# Replicape_B3A.net
KiCad netlist of a schematic drawn in EAGLE
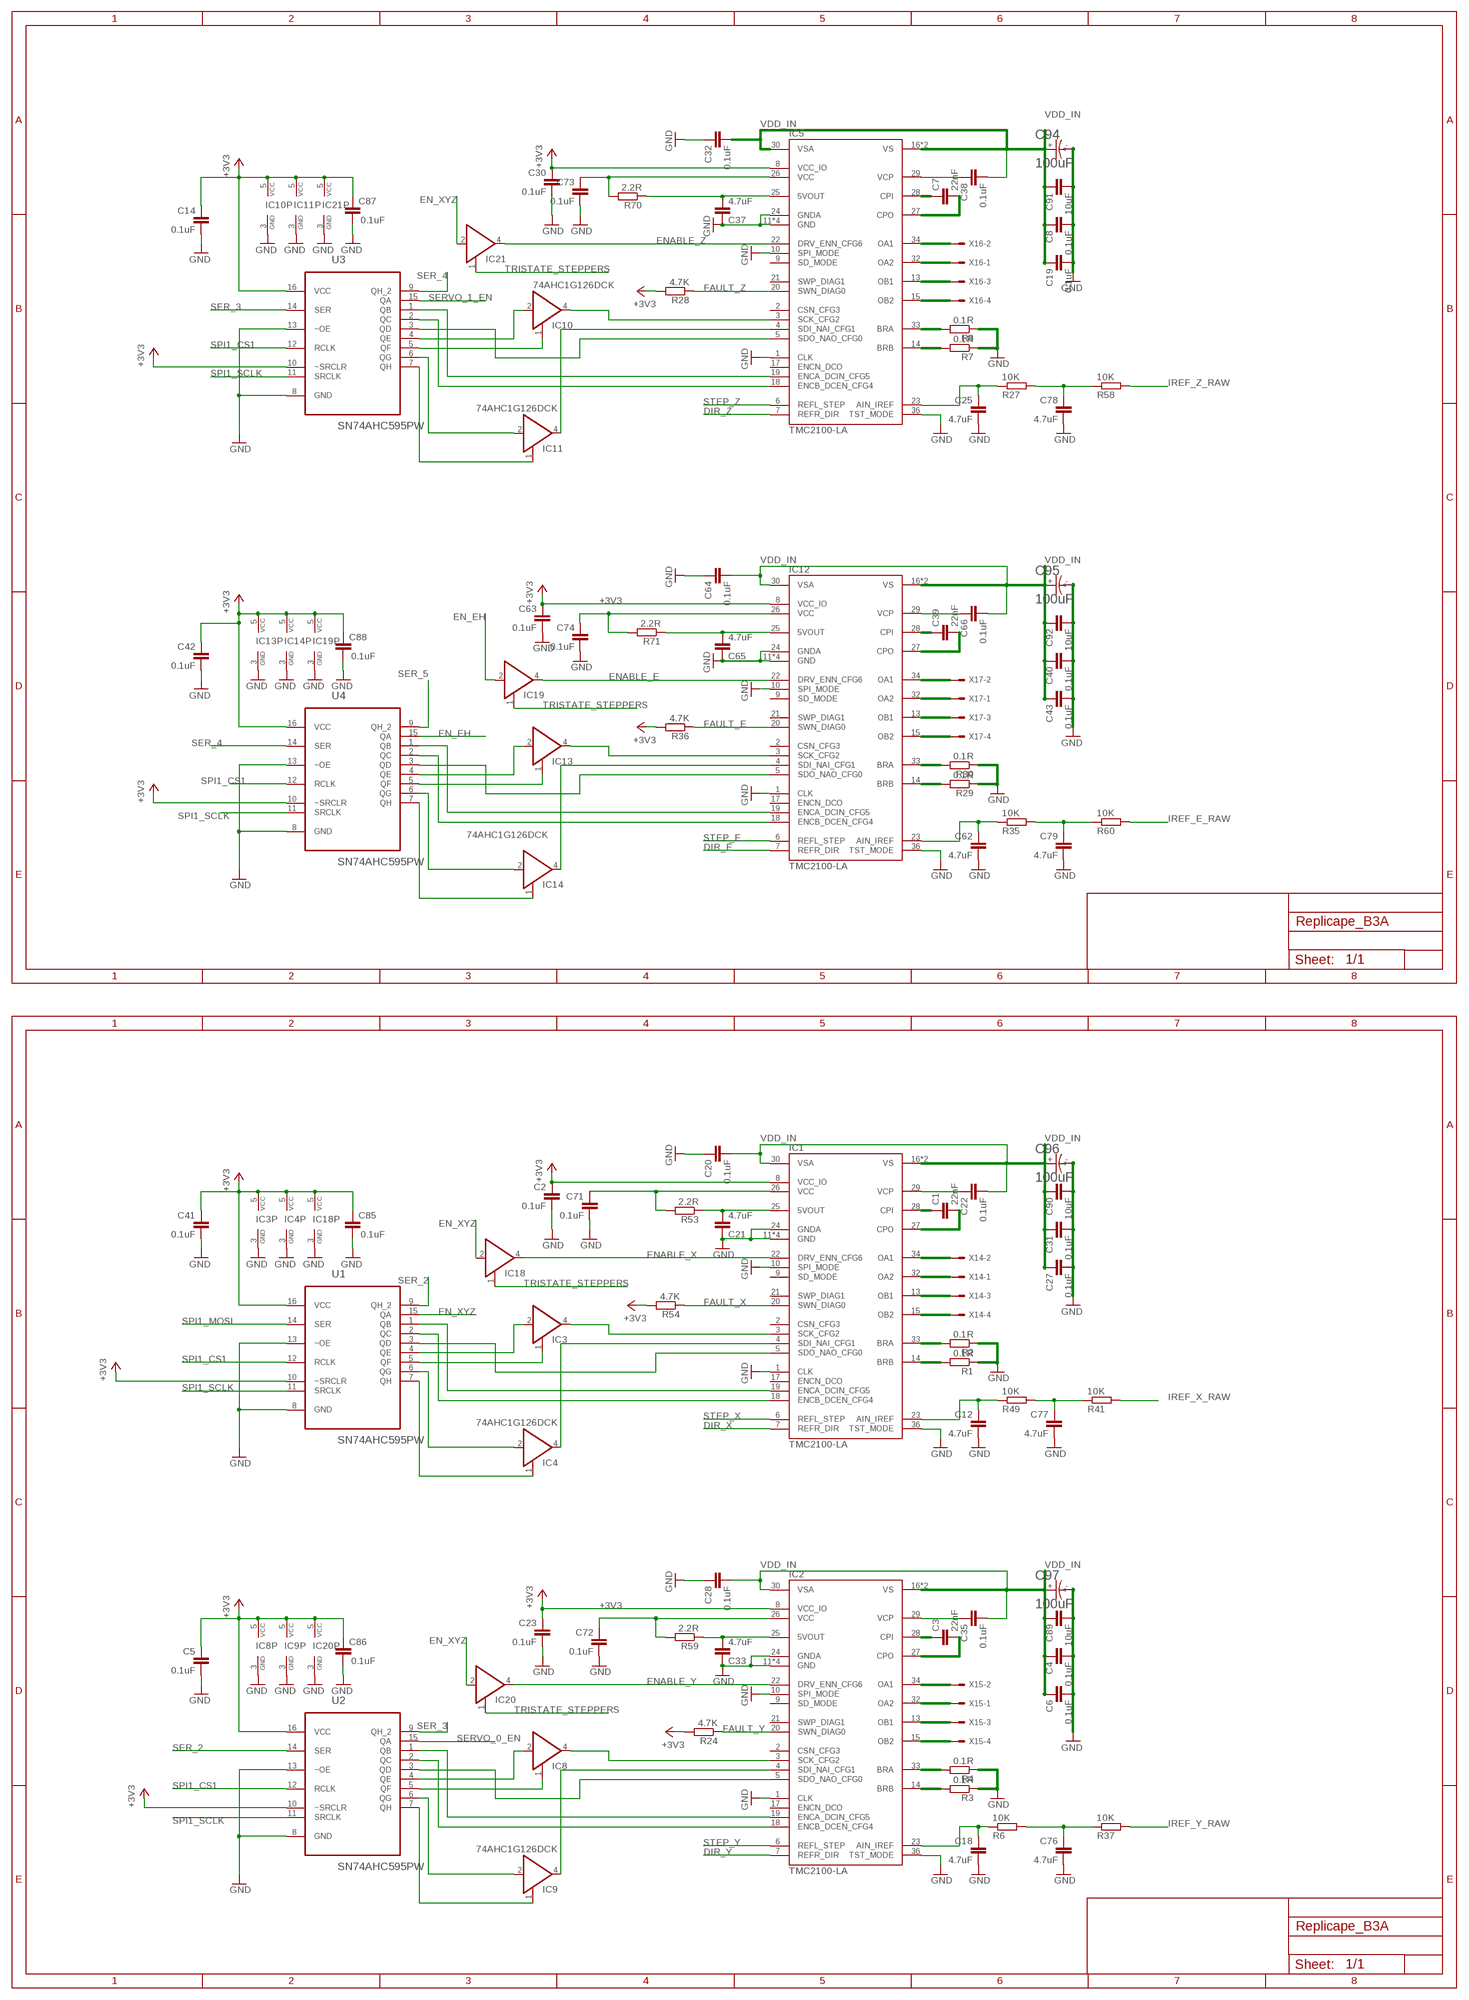
[diagram p0: schematic, sheet 1, part 1 of 3]
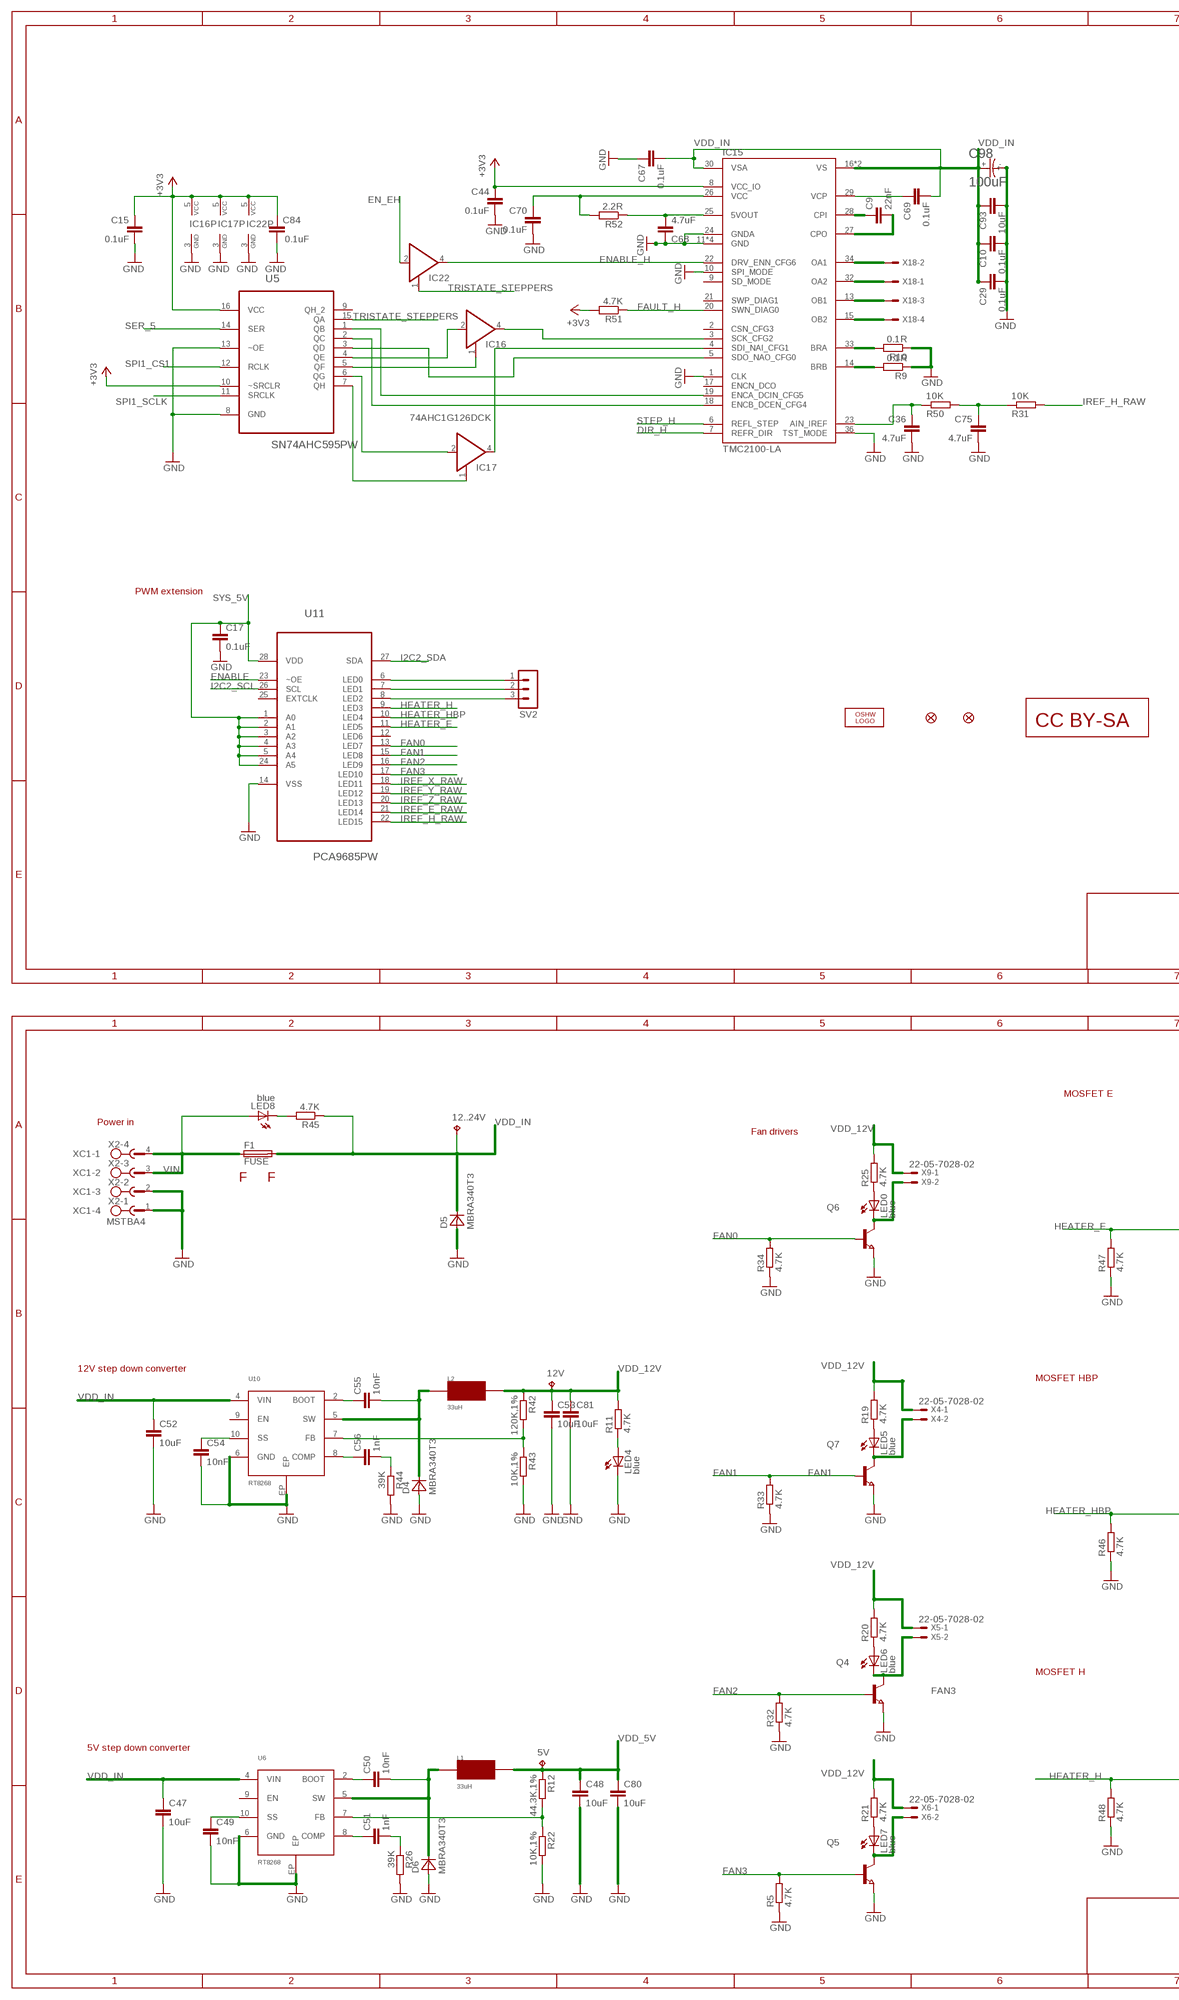
[diagram p1: schematic, sheet 1, part 2 of 3]
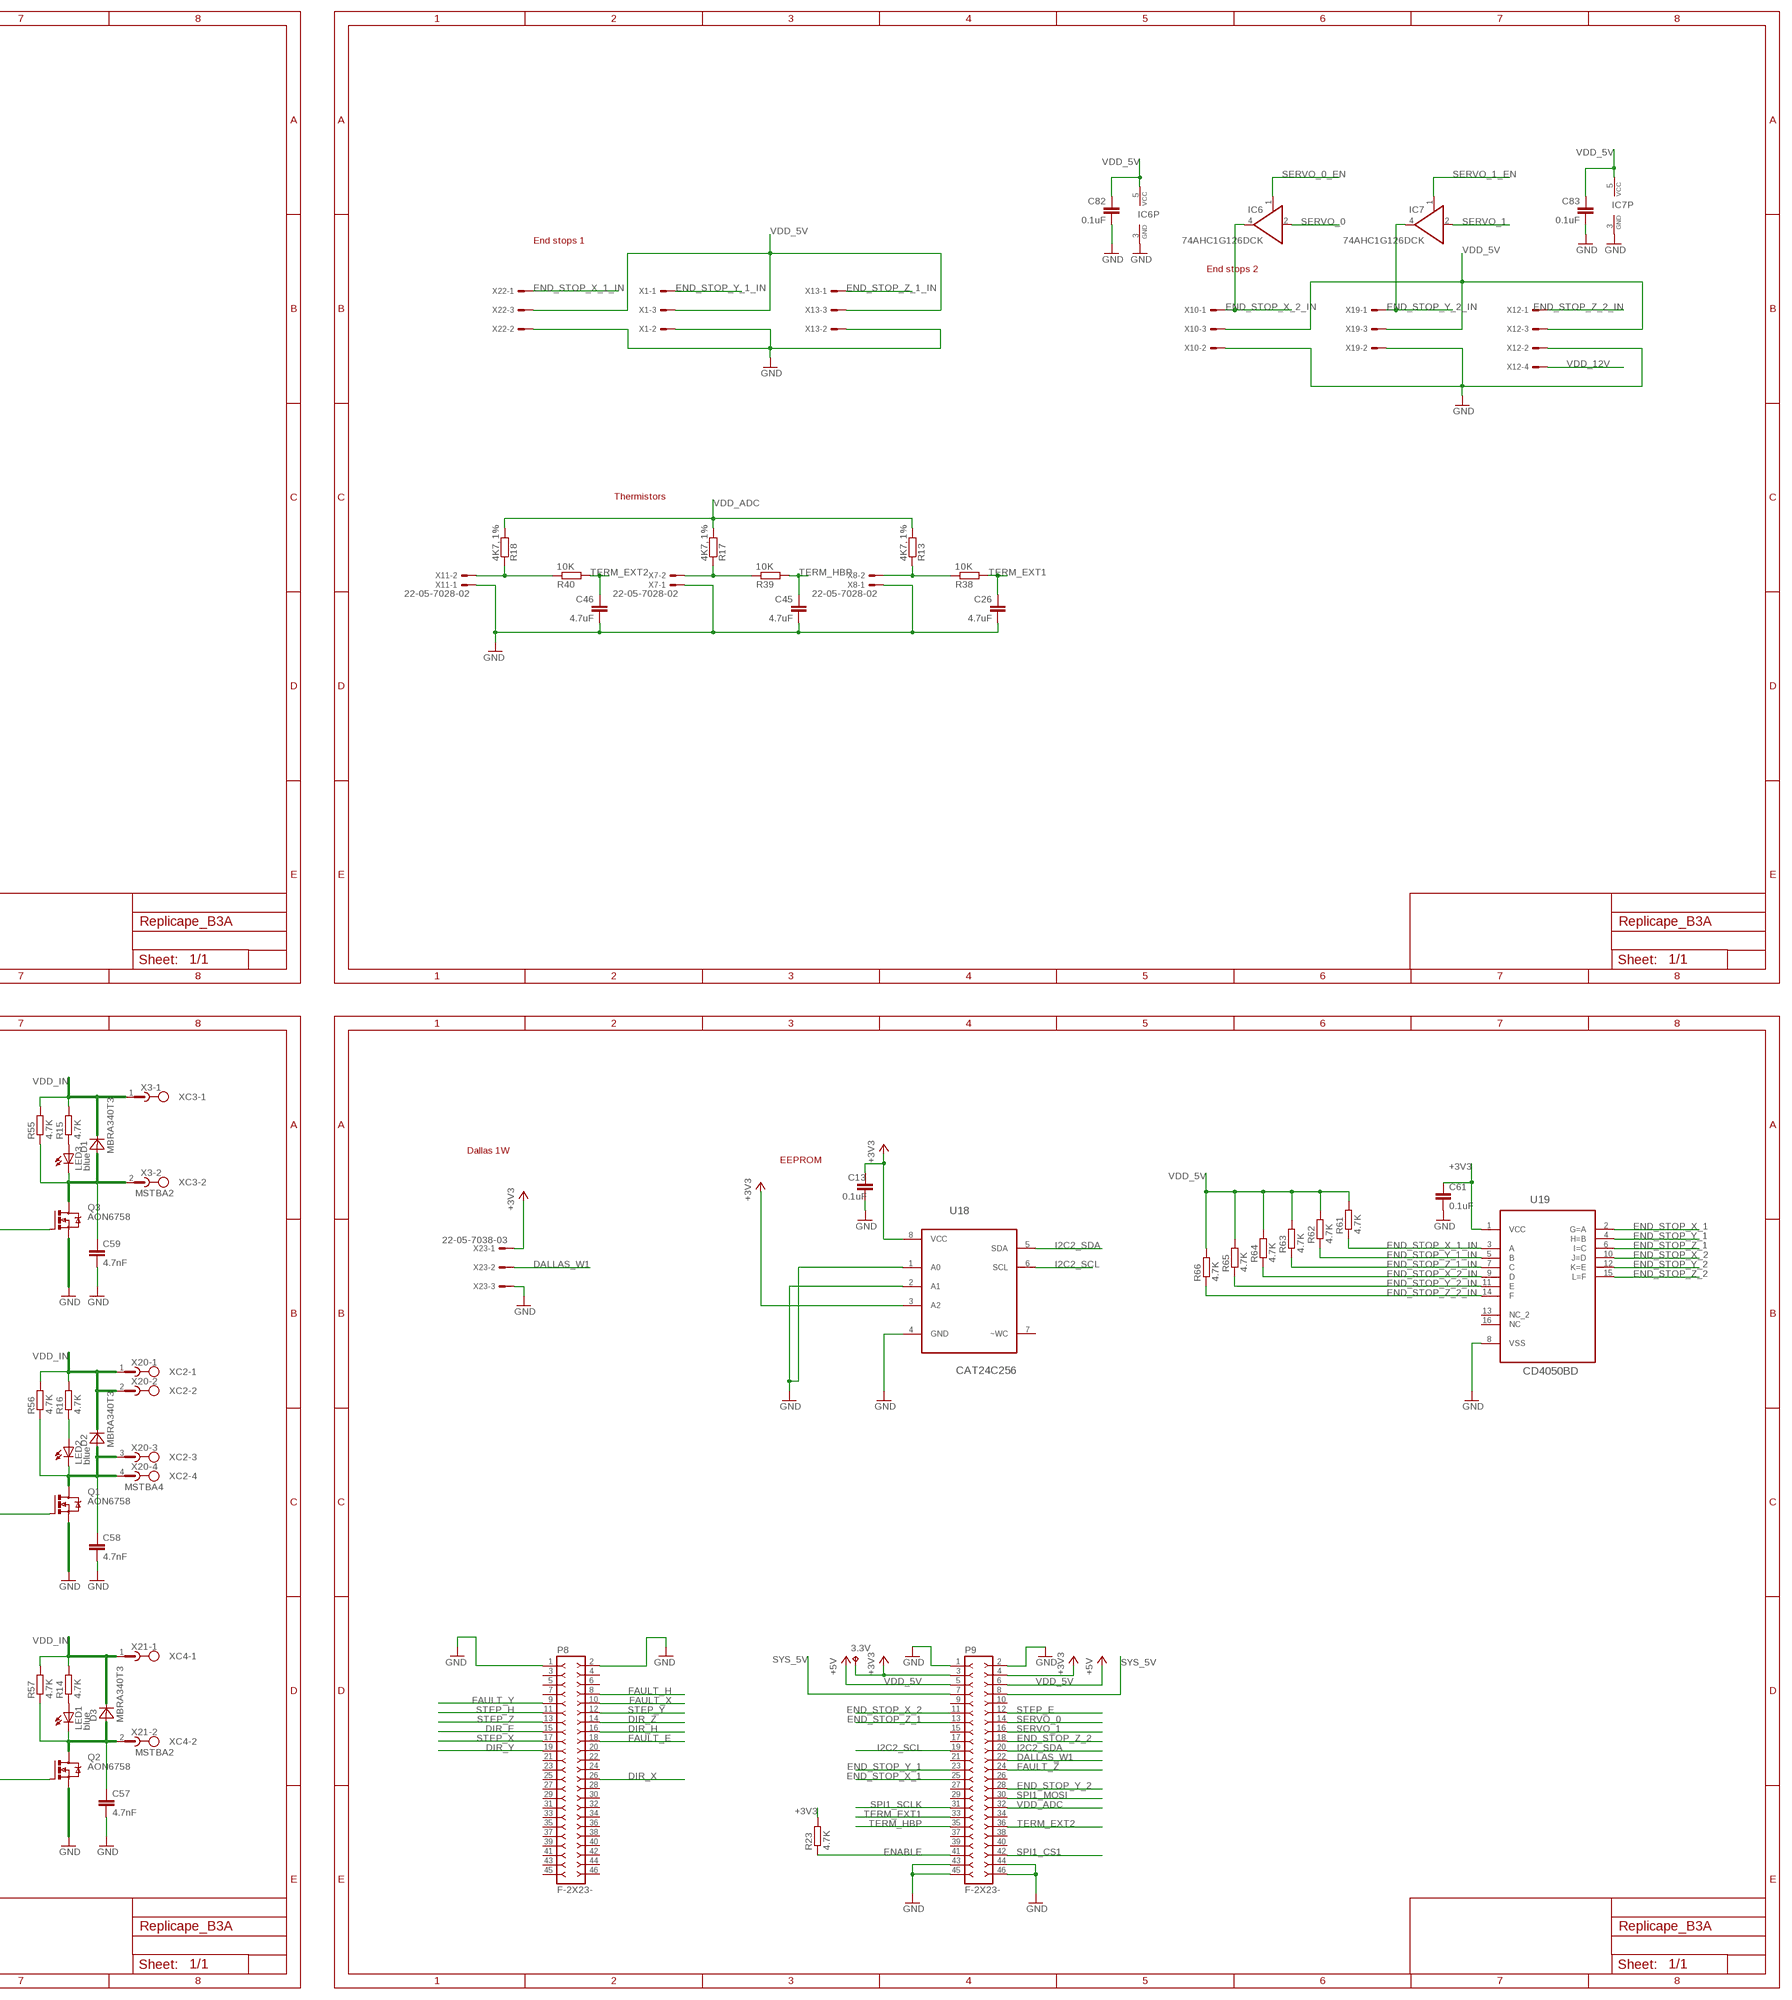
[diagram p2: schematic, sheet 1, part 3 of 3]

(export (version "E")
  (design (tool "Eeschema 10.0.6"))
  (components
    (comp (ref "3.3V")
      (value "TPB1,27")
      (footprint "eagle-import:B1,27")
      (libsource (lib "eagle-import") (part "TPB1,27"))
    )
    (comp (ref "5V")
      (value "TPB1,27")
      (footprint "eagle-import:B1,27")
      (libsource (lib "eagle-import") (part "TPB1,27"))
    )
    (comp (ref "12..24V")
      (value "TPB1,27")
      (footprint "eagle-import:B1,27")
      (libsource (lib "eagle-import") (part "TPB1,27"))
    )
    (comp (ref "12V")
      (value "TPB1,27")
      (footprint "eagle-import:B1,27")
      (libsource (lib "eagle-import") (part "TPB1,27"))
    )
    (comp (ref "C1")
      (value "22nF")
      (footprint "eagle-import:C0402")
      (fields (field (name "MPN") "C1005X7R1E223K050BB"))
      (libsource (lib "eagle-import") (part "C-EUC0402"))
    )
    (comp (ref "C2")
      (value "0.1uF")
      (footprint "eagle-import:C0402")
      (fields (field (name "MPN") "CL10B104KB8NNND"))
      (libsource (lib "eagle-import") (part "C-EUC0402"))
    )
    (comp (ref "C3")
      (value "22nF")
      (footprint "eagle-import:C0402")
      (fields (field (name "MPN") "C1005X7R1E223K050BB"))
      (libsource (lib "eagle-import") (part "C-EUC0402"))
    )
    (comp (ref "C4")
      (value "0.1uF")
      (footprint "eagle-import:C0402")
      (fields (field (name "MPN") "CL10B104KB8NNND"))
      (libsource (lib "eagle-import") (part "C-EUC0402"))
    )
    (comp (ref "C5")
      (value "0.1uF")
      (footprint "eagle-import:C0402")
      (fields (field (name "MPN") "CL10B104KB8NNND"))
      (libsource (lib "eagle-import") (part "C-EUC0402"))
    )
    (comp (ref "C6")
      (value "0.1uF")
      (footprint "eagle-import:C0402")
      (fields (field (name "MPN") "CL10B104KB8NNND"))
      (libsource (lib "eagle-import") (part "C-EUC0402"))
    )
    (comp (ref "C7")
      (value "22nF")
      (footprint "eagle-import:C0402")
      (fields (field (name "MPN") "C1005X7R1E223K050BB"))
      (libsource (lib "eagle-import") (part "C-EUC0402"))
    )
    (comp (ref "C8")
      (value "0.1uF")
      (footprint "eagle-import:C0402")
      (fields (field (name "MPN") "CL10B104KB8NNND"))
      (libsource (lib "eagle-import") (part "C-EUC0402"))
    )
    (comp (ref "C9")
      (value "22nF")
      (footprint "eagle-import:C0402")
      (fields (field (name "MPN") "C1005X7R1E223K050BB"))
      (libsource (lib "eagle-import") (part "C-EUC0402"))
    )
    (comp (ref "C10")
      (value "0.1uF")
      (footprint "eagle-import:C0402")
      (fields (field (name "MPN") "CL10B104KB8NNND"))
      (libsource (lib "eagle-import") (part "C-EUC0402"))
    )
    (comp (ref "C12")
      (value "4.7uF")
      (footprint "eagle-import:C0402")
      (fields (field (name "MPN") "GRM155R60J475ME47D"))
      (libsource (lib "eagle-import") (part "C-EUC0402"))
    )
    (comp (ref "C13")
      (value "0.1uF")
      (footprint "eagle-import:C0402")
      (fields (field (name "MPN") "CL10B104KB8NNND"))
      (libsource (lib "eagle-import") (part "C-EUC0402"))
    )
    (comp (ref "C14")
      (value "0.1uF")
      (footprint "eagle-import:C0402")
      (fields (field (name "MPN") "CL10B104KB8NNND"))
      (libsource (lib "eagle-import") (part "C-EUC0402"))
    )
    (comp (ref "C15")
      (value "0.1uF")
      (footprint "eagle-import:C0402")
      (fields (field (name "MPN") "CL10B104KB8NNND"))
      (libsource (lib "eagle-import") (part "C-EUC0402"))
    )
    (comp (ref "C17")
      (value "0.1uF")
      (footprint "eagle-import:C0402")
      (fields (field (name "MPN") "CL10B104KB8NNND"))
      (libsource (lib "eagle-import") (part "C-EUC0402"))
    )
    (comp (ref "C18")
      (value "4.7uF")
      (footprint "eagle-import:C0402")
      (fields (field (name "MPN") "GRM155R60J475ME47D"))
      (libsource (lib "eagle-import") (part "C-EUC0402"))
    )
    (comp (ref "C19")
      (value "0.1uF")
      (footprint "eagle-import:C0402")
      (fields (field (name "MPN") "CL10B104KB8NNND"))
      (libsource (lib "eagle-import") (part "C-EUC0402"))
    )
    (comp (ref "C20")
      (value "0.1uF")
      (footprint "eagle-import:C0402")
      (fields (field (name "MPN") "CL10B104KB8NNND"))
      (libsource (lib "eagle-import") (part "C-EUC0402"))
    )
    (comp (ref "C21")
      (value "4.7uF")
      (footprint "eagle-import:C0402")
      (fields (field (name "MPN") "GRM155R60J475ME47D"))
      (libsource (lib "eagle-import") (part "C-EUC0402"))
    )
    (comp (ref "C22")
      (value "0.1uF")
      (footprint "eagle-import:C0402")
      (fields (field (name "MPN") "CL10B104KB8NNND"))
      (libsource (lib "eagle-import") (part "C-EUC0402"))
    )
    (comp (ref "C23")
      (value "0.1uF")
      (footprint "eagle-import:C0402")
      (fields (field (name "MPN") "CL10B104KB8NNND"))
      (libsource (lib "eagle-import") (part "C-EUC0402"))
    )
    (comp (ref "C25")
      (value "4.7uF")
      (footprint "eagle-import:C0402")
      (fields (field (name "MPN") "GRM155R60J475ME47D"))
      (libsource (lib "eagle-import") (part "C-EUC0402"))
    )
    (comp (ref "C26")
      (value "4.7uF")
      (footprint "eagle-import:C0402")
      (fields (field (name "MPN") "GRM155R60J475ME47D"))
      (libsource (lib "eagle-import") (part "C-EUC0402"))
    )
    (comp (ref "C27")
      (value "0.1uF")
      (footprint "eagle-import:C0402")
      (fields (field (name "MPN") "CL10B104KB8NNND"))
      (libsource (lib "eagle-import") (part "C-EUC0402"))
    )
    (comp (ref "C28")
      (value "0.1uF")
      (footprint "eagle-import:C0402")
      (fields (field (name "MPN") "CL10B104KB8NNND"))
      (libsource (lib "eagle-import") (part "C-EUC0402"))
    )
    (comp (ref "C29")
      (value "0.1uF")
      (footprint "eagle-import:C0402")
      (fields (field (name "MPN") "CL10B104KB8NNND"))
      (libsource (lib "eagle-import") (part "C-EUC0402"))
    )
    (comp (ref "C30")
      (value "0.1uF")
      (footprint "eagle-import:C0402")
      (fields (field (name "MPN") "CL10B104KB8NNND"))
      (libsource (lib "eagle-import") (part "C-EUC0402"))
    )
    (comp (ref "C31")
      (value "0.1uF")
      (footprint "eagle-import:C0402")
      (fields (field (name "MPN") "CL10B104KB8NNND"))
      (libsource (lib "eagle-import") (part "C-EUC0402"))
    )
    (comp (ref "C32")
      (value "0.1uF")
      (footprint "eagle-import:C0402")
      (fields (field (name "MPN") "CL10B104KB8NNND"))
      (libsource (lib "eagle-import") (part "C-EUC0402"))
    )
    (comp (ref "C33")
      (value "4.7uF")
      (footprint "eagle-import:C0402")
      (fields (field (name "MPN") "GRM155R60J475ME47D"))
      (libsource (lib "eagle-import") (part "C-EUC0402"))
    )
    (comp (ref "C35")
      (value "0.1uF")
      (footprint "eagle-import:C0402")
      (fields (field (name "MPN") "CL10B104KB8NNND"))
      (libsource (lib "eagle-import") (part "C-EUC0402"))
    )
    (comp (ref "C36")
      (value "4.7uF")
      (footprint "eagle-import:C0402")
      (fields (field (name "MPN") "GRM155R60J475ME47D"))
      (libsource (lib "eagle-import") (part "C-EUC0402"))
    )
    (comp (ref "C37")
      (value "4.7uF")
      (footprint "eagle-import:C0402")
      (fields (field (name "MPN") "GRM155R60J475ME47D"))
      (libsource (lib "eagle-import") (part "C-EUC0402"))
    )
    (comp (ref "C38")
      (value "0.1uF")
      (footprint "eagle-import:C0402")
      (fields (field (name "MPN") "CL10B104KB8NNND"))
      (libsource (lib "eagle-import") (part "C-EUC0402"))
    )
    (comp (ref "C39")
      (value "22nF")
      (footprint "eagle-import:C0402")
      (fields (field (name "MPN") "C1005X7R1E223K050BB"))
      (libsource (lib "eagle-import") (part "C-EUC0402"))
    )
    (comp (ref "C40")
      (value "0.1uF")
      (footprint "eagle-import:C0402")
      (fields (field (name "MPN") "CL10B104KB8NNND"))
      (libsource (lib "eagle-import") (part "C-EUC0402"))
    )
    (comp (ref "C41")
      (value "0.1uF")
      (footprint "eagle-import:C0402")
      (fields (field (name "MPN") "CL10B104KB8NNND"))
      (libsource (lib "eagle-import") (part "C-EUC0402"))
    )
    (comp (ref "C42")
      (value "0.1uF")
      (footprint "eagle-import:C0402")
      (fields (field (name "MPN") "CL10B104KB8NNND"))
      (libsource (lib "eagle-import") (part "C-EUC0402"))
    )
    (comp (ref "C43")
      (value "0.1uF")
      (footprint "eagle-import:C0402")
      (fields (field (name "MPN") "CL10B104KB8NNND"))
      (libsource (lib "eagle-import") (part "C-EUC0402"))
    )
    (comp (ref "C44")
      (value "0.1uF")
      (footprint "eagle-import:C0402")
      (fields (field (name "MPN") "CL10B104KB8NNND"))
      (libsource (lib "eagle-import") (part "C-EUC0402"))
    )
    (comp (ref "C45")
      (value "4.7uF")
      (footprint "eagle-import:C0402")
      (fields (field (name "MPN") "GRM155R60J475ME47D"))
      (libsource (lib "eagle-import") (part "C-EUC0402"))
    )
    (comp (ref "C46")
      (value "4.7uF")
      (footprint "eagle-import:C0402")
      (fields (field (name "MPN") "GRM155R60J475ME47D"))
      (libsource (lib "eagle-import") (part "C-EUC0402"))
    )
    (comp (ref "C47")
      (value "10uF")
      (footprint "eagle-import:C1206")
      (fields (field (name "MPN") "CL31B106KAHNNNE"))
      (libsource (lib "eagle-import") (part "C-EUC1206"))
    )
    (comp (ref "C48")
      (value "10uF")
      (footprint "eagle-import:C1206")
      (fields (field (name "MPN") "CL31B106KAHNNNE"))
      (libsource (lib "eagle-import") (part "C-EUC1206"))
    )
    (comp (ref "C49")
      (value "10nF")
      (footprint "eagle-import:C0402")
      (fields (field (name "MPN") "CL05B103KB5NNNC"))
      (libsource (lib "eagle-import") (part "C-EUC0402"))
    )
    (comp (ref "C50")
      (value "10nF")
      (footprint "eagle-import:C0402")
      (fields (field (name "MPN") "CL05B103KB5NNNC"))
      (libsource (lib "eagle-import") (part "C-EUC0402"))
    )
    (comp (ref "C51")
      (value "1nF")
      (footprint "eagle-import:C0402")
      (fields (field (name "MPN") "C1005X7R1H102K050BA"))
      (libsource (lib "eagle-import") (part "C-EUC0402"))
    )
    (comp (ref "C52")
      (value "10uF")
      (footprint "eagle-import:C1206")
      (fields (field (name "MPN") "CL31B106KAHNNNE"))
      (libsource (lib "eagle-import") (part "C-EUC1206"))
    )
    (comp (ref "C53")
      (value "10uF")
      (footprint "eagle-import:C1206")
      (fields (field (name "MPN") "CL31B106KAHNNNE"))
      (libsource (lib "eagle-import") (part "C-EUC1206"))
    )
    (comp (ref "C54")
      (value "10nF")
      (footprint "eagle-import:C0402")
      (fields (field (name "MPN") "CL05B103KB5NNNC"))
      (libsource (lib "eagle-import") (part "C-EUC0402"))
    )
    (comp (ref "C55")
      (value "10nF")
      (footprint "eagle-import:C0402")
      (fields (field (name "MPN") "CL05B103KB5NNNC"))
      (libsource (lib "eagle-import") (part "C-EUC0402"))
    )
    (comp (ref "C56")
      (value "1nF")
      (footprint "eagle-import:C0402")
      (fields (field (name "MPN") "C1005X7R1H102K050BA"))
      (libsource (lib "eagle-import") (part "C-EUC0402"))
    )
    (comp (ref "C57")
      (value "4.7nF")
      (footprint "eagle-import:C0402")
      (fields (field (name "MPN") "CL05B472KA5NNNC"))
      (libsource (lib "eagle-import") (part "C-EUC0402"))
    )
    (comp (ref "C58")
      (value "4.7nF")
      (footprint "eagle-import:C0402")
      (fields (field (name "MPN") "CL05B472KA5NNNC"))
      (libsource (lib "eagle-import") (part "C-EUC0402"))
    )
    (comp (ref "C59")
      (value "4.7nF")
      (footprint "eagle-import:C0402")
      (fields (field (name "MPN") "CL05B472KA5NNNC"))
      (libsource (lib "eagle-import") (part "C-EUC0402"))
    )
    (comp (ref "C61")
      (value "0.1uF")
      (footprint "eagle-import:C0402")
      (fields (field (name "MPN") "CL10B104KB8NNND"))
      (libsource (lib "eagle-import") (part "C-EUC0402"))
    )
    (comp (ref "C62")
      (value "4.7uF")
      (footprint "eagle-import:C0402")
      (fields (field (name "MPN") "GRM155R60J475ME47D"))
      (libsource (lib "eagle-import") (part "C-EUC0402"))
    )
    (comp (ref "C63")
      (value "0.1uF")
      (footprint "eagle-import:C0402")
      (fields (field (name "MPN") "CL10B104KB8NNND"))
      (libsource (lib "eagle-import") (part "C-EUC0402"))
    )
    (comp (ref "C64")
      (value "0.1uF")
      (footprint "eagle-import:C0402")
      (fields (field (name "MPN") "CL10B104KB8NNND"))
      (libsource (lib "eagle-import") (part "C-EUC0402"))
    )
    (comp (ref "C65")
      (value "4.7uF")
      (footprint "eagle-import:C0402")
      (fields (field (name "MPN") "GRM155R60J475ME47D"))
      (libsource (lib "eagle-import") (part "C-EUC0402"))
    )
    (comp (ref "C66")
      (value "0.1uF")
      (footprint "eagle-import:C0402")
      (fields (field (name "MPN") "CL10B104KB8NNND"))
      (libsource (lib "eagle-import") (part "C-EUC0402"))
    )
    (comp (ref "C67")
      (value "0.1uF")
      (footprint "eagle-import:C0402")
      (fields (field (name "MPN") "CL10B104KB8NNND"))
      (libsource (lib "eagle-import") (part "C-EUC0402"))
    )
    (comp (ref "C68")
      (value "4.7uF")
      (footprint "eagle-import:C0402")
      (fields (field (name "MPN") "GRM155R60J475ME47D"))
      (libsource (lib "eagle-import") (part "C-EUC0402"))
    )
    (comp (ref "C69")
      (value "0.1uF")
      (footprint "eagle-import:C0402")
      (fields (field (name "MPN") "CL10B104KB8NNND"))
      (libsource (lib "eagle-import") (part "C-EUC0402"))
    )
    (comp (ref "C70")
      (value "0.1uF")
      (footprint "eagle-import:C0402")
      (fields (field (name "MPN") "CL10B104KB8NNND"))
      (libsource (lib "eagle-import") (part "C-EUC0402"))
    )
    (comp (ref "C71")
      (value "0.1uF")
      (footprint "eagle-import:C0402")
      (fields (field (name "MPN") "CL10B104KB8NNND"))
      (libsource (lib "eagle-import") (part "C-EUC0402"))
    )
    (comp (ref "C72")
      (value "0.1uF")
      (footprint "eagle-import:C0402")
      (fields (field (name "MPN") "CL10B104KB8NNND"))
      (libsource (lib "eagle-import") (part "C-EUC0402"))
    )
    (comp (ref "C73")
      (value "0.1uF")
      (footprint "eagle-import:C0402")
      (fields (field (name "MPN") "CL10B104KB8NNND"))
      (libsource (lib "eagle-import") (part "C-EUC0402"))
    )
    (comp (ref "C74")
      (value "0.1uF")
      (footprint "eagle-import:C0402")
      (fields (field (name "MPN") "CL10B104KB8NNND"))
      (libsource (lib "eagle-import") (part "C-EUC0402"))
    )
    (comp (ref "C75")
      (value "4.7uF")
      (footprint "eagle-import:C0402")
      (fields (field (name "MPN") "GRM155R60J475ME47D"))
      (libsource (lib "eagle-import") (part "C-EUC0402"))
    )
    (comp (ref "C76")
      (value "4.7uF")
      (footprint "eagle-import:C0402")
      (fields (field (name "MPN") "GRM155R60J475ME47D"))
      (libsource (lib "eagle-import") (part "C-EUC0402"))
    )
    (comp (ref "C77")
      (value "4.7uF")
      (footprint "eagle-import:C0402")
      (fields (field (name "MPN") "GRM155R60J475ME47D"))
      (libsource (lib "eagle-import") (part "C-EUC0402"))
    )
    (comp (ref "C78")
      (value "4.7uF")
      (footprint "eagle-import:C0402")
      (fields (field (name "MPN") "GRM155R60J475ME47D"))
      (libsource (lib "eagle-import") (part "C-EUC0402"))
    )
    (comp (ref "C79")
      (value "4.7uF")
      (footprint "eagle-import:C0402")
      (fields (field (name "MPN") "GRM155R60J475ME47D"))
      (libsource (lib "eagle-import") (part "C-EUC0402"))
    )
    (comp (ref "C80")
      (value "10uF")
      (footprint "eagle-import:C1206")
      (fields (field (name "MPN") "CL31B106KAHNNNE"))
      (libsource (lib "eagle-import") (part "C-EUC1206"))
    )
    (comp (ref "C81")
      (value "10uF")
      (footprint "eagle-import:C1206")
      (fields (field (name "MPN") "CL31B106KAHNNNE"))
      (libsource (lib "eagle-import") (part "C-EUC1206"))
    )
    (comp (ref "C82")
      (value "0.1uF")
      (footprint "eagle-import:C0402")
      (fields (field (name "MPN") "CL10B104KB8NNND"))
      (libsource (lib "eagle-import") (part "C-EUC0402"))
    )
    (comp (ref "C83")
      (value "0.1uF")
      (footprint "eagle-import:C0402")
      (fields (field (name "MPN") "CL10B104KB8NNND"))
      (libsource (lib "eagle-import") (part "C-EUC0402"))
    )
    (comp (ref "C84")
      (value "0.1uF")
      (footprint "eagle-import:C0402")
      (fields (field (name "MPN") "CL10B104KB8NNND"))
      (libsource (lib "eagle-import") (part "C-EUC0402"))
    )
    (comp (ref "C85")
      (value "0.1uF")
      (footprint "eagle-import:C0402")
      (fields (field (name "MPN") "CL10B104KB8NNND"))
      (libsource (lib "eagle-import") (part "C-EUC0402"))
    )
    (comp (ref "C86")
      (value "0.1uF")
      (footprint "eagle-import:C0402")
      (fields (field (name "MPN") "CL10B104KB8NNND"))
      (libsource (lib "eagle-import") (part "C-EUC0402"))
    )
    (comp (ref "C87")
      (value "0.1uF")
      (footprint "eagle-import:C0402")
      (fields (field (name "MPN") "CL10B104KB8NNND"))
      (libsource (lib "eagle-import") (part "C-EUC0402"))
    )
    (comp (ref "C88")
      (value "0.1uF")
      (footprint "eagle-import:C0402")
      (fields (field (name "MPN") "CL10B104KB8NNND"))
      (libsource (lib "eagle-import") (part "C-EUC0402"))
    )
    (comp (ref "C89")
      (value "10uF")
      (footprint "eagle-import:C0805")
      (fields (field (name "MPN") "C2012X5R1V106M085AC"))
      (libsource (lib "eagle-import") (part "C-EUC0805"))
    )
    (comp (ref "C90")
      (value "10uF")
      (footprint "eagle-import:C0805")
      (fields (field (name "MPN") "C2012X5R1V106M085AC"))
      (libsource (lib "eagle-import") (part "C-EUC0805"))
    )
    (comp (ref "C91")
      (value "10uF")
      (footprint "eagle-import:C0805")
      (fields (field (name "MPN") "C2012X5R1V106M085AC"))
      (libsource (lib "eagle-import") (part "C-EUC0805"))
    )
    (comp (ref "C92")
      (value "10uF")
      (footprint "eagle-import:C0805")
      (fields (field (name "MPN") "C2012X5R1V106M085AC"))
      (libsource (lib "eagle-import") (part "C-EUC0805"))
    )
    (comp (ref "C93")
      (value "10uF")
      (footprint "eagle-import:C0805")
      (fields (field (name "MPN") "C2012X5R1V106M085AC"))
      (libsource (lib "eagle-import") (part "C-EUC0805"))
    )
    (comp (ref "C94")
      (value "100uF")
      (footprint "eagle-import:RHS1V10MCN1GS")
      (fields (field (name "MPN") "RHS1V101MCN1GS"))
      (libsource (lib "eagle-import") (part "C"))
    )
    (comp (ref "C95")
      (value "100uF")
      (footprint "eagle-import:RHS1V10MCN1GS")
      (fields (field (name "MPN") "RHS1V101MCN1GS"))
      (libsource (lib "eagle-import") (part "C"))
    )
    (comp (ref "C96")
      (value "100uF")
      (footprint "eagle-import:RHS1V10MCN1GS")
      (fields (field (name "MPN") "RHS1V101MCN1GS"))
      (libsource (lib "eagle-import") (part "C"))
    )
    (comp (ref "C97")
      (value "100uF")
      (footprint "eagle-import:RHS1V10MCN1GS")
      (fields (field (name "MPN") "RHS1V101MCN1GS"))
      (libsource (lib "eagle-import") (part "C"))
    )
    (comp (ref "C98")
      (value "100uF")
      (footprint "eagle-import:RHS1V10MCN1GS")
      (fields (field (name "MPN") "RHS1V101MCN1GS"))
      (libsource (lib "eagle-import") (part "C"))
    )
    (comp (ref "D1")
      (value "MBRA340T3")
      (footprint "eagle-import:SMA")
      (fields (field (name "MPN") "MBRA340T3G"))
      (libsource (lib "eagle-import") (part "MBRA340T3"))
    )
    (comp (ref "D2")
      (value "MBRA340T3")
      (footprint "eagle-import:SMA")
      (fields (field (name "MPN") "MBRA340T3G"))
      (libsource (lib "eagle-import") (part "MBRA340T3"))
    )
    (comp (ref "D3")
      (value "MBRA340T3")
      (footprint "eagle-import:SMA")
      (fields (field (name "MPN") "MBRA340T3G"))
      (libsource (lib "eagle-import") (part "MBRA340T3"))
    )
    (comp (ref "D4")
      (value "MBRA340T3")
      (footprint "eagle-import:SMA")
      (fields (field (name "MPN") "MBRA340T3G"))
      (libsource (lib "eagle-import") (part "MBRA340T3"))
    )
    (comp (ref "D5")
      (value "MBRA340T3")
      (footprint "eagle-import:SMA")
      (fields (field (name "MPN") "MBRA340T3G"))
      (libsource (lib "eagle-import") (part "MBRA340T3"))
    )
    (comp (ref "D6")
      (value "MBRA340T3")
      (footprint "eagle-import:SMA")
      (fields (field (name "MPN") "MBRA340T3G"))
      (libsource (lib "eagle-import") (part "MBRA340T3"))
    )
    (comp (ref "F1")
      (value "FUSE")
      (footprint "eagle-import:3557")
      (fields (field (name "MPN") "0891020.NXS"))
      (libsource (lib "eagle-import") (part "FUSE"))
    )
    (comp (ref "FH1")
      (value "FUSE-HOLDER")
      (footprint "eagle-import:FUSE-HOLDER")
      (fields (field (name "MPN") "3557"))
      (libsource (lib "eagle-import") (part "FUSE-HOLDER"))
    )
    (comp (ref "FH2")
      (value "FUSE-HOLDER")
      (footprint "eagle-import:FUSE-HOLDER")
      (fields (field (name "MPN") "3557"))
      (libsource (lib "eagle-import") (part "FUSE-HOLDER"))
    )
    (comp (ref "IC1")
      (value "TMC2100-LA")
      (footprint "eagle-import:QFN36-PAD")
      (fields (field (name "MPN") "TMC2100-LA-T"))
      (libsource (lib "eagle-import") (part "TMC2100-LA"))
    )
    (comp (ref "IC2")
      (value "TMC2100-LA")
      (footprint "eagle-import:QFN36-PAD")
      (fields (field (name "MPN") "TMC2100-LA-T"))
      (libsource (lib "eagle-import") (part "TMC2100-LA"))
    )
    (comp (ref "IC3")
      (value "74AHC1G126DCK")
      (footprint "eagle-import:SC70-5")
      (fields (field (name "MPN") "M74VHC1GT126DF1G"))
      (libsource (lib "eagle-import") (part "741G126DCKAHC"))
    )
    (comp (ref "IC4")
      (value "74AHC1G126DCK")
      (footprint "eagle-import:SC70-5")
      (fields (field (name "MPN") "M74VHC1GT126DF1G"))
      (libsource (lib "eagle-import") (part "741G126DCKAHC"))
    )
    (comp (ref "IC5")
      (value "TMC2100-LA")
      (footprint "eagle-import:QFN36-PAD")
      (fields (field (name "MPN") "TMC2100-LA-T"))
      (libsource (lib "eagle-import") (part "TMC2100-LA"))
    )
    (comp (ref "IC6")
      (value "74AHC1G126DCK")
      (footprint "eagle-import:SC70-5")
      (fields (field (name "MPN") "M74VHC1GT126DF1G"))
      (libsource (lib "eagle-import") (part "741G126DCKAHC"))
    )
    (comp (ref "IC7")
      (value "74AHC1G126DCK")
      (footprint "eagle-import:SC70-5")
      (fields (field (name "MPN") "M74VHC1GT126DF1G"))
      (libsource (lib "eagle-import") (part "741G126DCKAHC"))
    )
    (comp (ref "IC8")
      (value "74AHC1G126DCK")
      (footprint "eagle-import:SC70-5")
      (fields (field (name "MPN") "M74VHC1GT126DF1G"))
      (libsource (lib "eagle-import") (part "741G126DCKAHC"))
    )
    (comp (ref "IC9")
      (value "74AHC1G126DCK")
      (footprint "eagle-import:SC70-5")
      (fields (field (name "MPN") "M74VHC1GT126DF1G"))
      (libsource (lib "eagle-import") (part "741G126DCKAHC"))
    )
    (comp (ref "IC10")
      (value "74AHC1G126DCK")
      (footprint "eagle-import:SC70-5")
      (fields (field (name "MPN") "M74VHC1GT126DF1G"))
      (libsource (lib "eagle-import") (part "741G126DCKAHC"))
    )
    (comp (ref "IC11")
      (value "74AHC1G126DCK")
      (footprint "eagle-import:SC70-5")
      (fields (field (name "MPN") "M74VHC1GT126DF1G"))
      (libsource (lib "eagle-import") (part "741G126DCKAHC"))
    )
    (comp (ref "IC12")
      (value "TMC2100-LA")
      (footprint "eagle-import:QFN36-PAD")
      (fields (field (name "MPN") "TMC2100-LA-T"))
      (libsource (lib "eagle-import") (part "TMC2100-LA"))
    )
    (comp (ref "IC13")
      (value "74AHC1G126DCK")
      (footprint "eagle-import:SC70-5")
      (fields (field (name "MPN") "M74VHC1GT126DF1G"))
      (libsource (lib "eagle-import") (part "741G126DCKAHC"))
    )
    (comp (ref "IC14")
      (value "74AHC1G126DCK")
      (footprint "eagle-import:SC70-5")
      (fields (field (name "MPN") "M74VHC1GT126DF1G"))
      (libsource (lib "eagle-import") (part "741G126DCKAHC"))
    )
    (comp (ref "IC15")
      (value "TMC2100-LA")
      (footprint "eagle-import:QFN36-PAD")
      (fields (field (name "MPN") "TMC2100-LA-T"))
      (libsource (lib "eagle-import") (part "TMC2100-LA"))
    )
    (comp (ref "IC16")
      (value "74AHC1G126DCK")
      (footprint "eagle-import:SC70-5")
      (fields (field (name "MPN") "M74VHC1GT126DF1G"))
      (libsource (lib "eagle-import") (part "741G126DCKAHC"))
    )
    (comp (ref "IC17")
      (value "74AHC1G126DCK")
      (footprint "eagle-import:SC70-5")
      (fields (field (name "MPN") "M74VHC1GT126DF1G"))
      (libsource (lib "eagle-import") (part "741G126DCKAHC"))
    )
    (comp (ref "IC18")
      (value "74AHC1G126DCK")
      (footprint "eagle-import:SC70-5")
      (fields (field (name "MPN") "M74VHC1GT126DF1G"))
      (libsource (lib "eagle-import") (part "741G126DCKAHC"))
    )
    (comp (ref "IC19")
      (value "74AHC1G126DCK")
      (footprint "eagle-import:SC70-5")
      (fields (field (name "MPN") "M74VHC1GT126DF1G"))
      (libsource (lib "eagle-import") (part "741G126DCKAHC"))
    )
    (comp (ref "IC20")
      (value "74AHC1G126DCK")
      (footprint "eagle-import:SC70-5")
      (fields (field (name "MPN") "M74VHC1GT126DF1G"))
      (libsource (lib "eagle-import") (part "741G126DCKAHC"))
    )
    (comp (ref "IC21")
      (value "74AHC1G126DCK")
      (footprint "eagle-import:SC70-5")
      (fields (field (name "MPN") "M74VHC1GT126DF1G"))
      (libsource (lib "eagle-import") (part "741G126DCKAHC"))
    )
    (comp (ref "IC22")
      (value "74AHC1G126DCK")
      (footprint "eagle-import:SC70-5")
      (fields (field (name "MPN") "M74VHC1GT126DF1G"))
      (libsource (lib "eagle-import") (part "741G126DCKAHC"))
    )
    (comp (ref "JP1")
      (value "FIDUCIAL1X2.5")
      (footprint "eagle-import:FIDUCIAL-1X2.5")
      (libsource (lib "eagle-import") (part "FIDUCIAL1X2.5"))
    )
    (comp (ref "JP2")
      (value "FIDUCIAL1X2.5")
      (footprint "eagle-import:FIDUCIAL-1X2.5")
      (libsource (lib "eagle-import") (part "FIDUCIAL1X2.5"))
    )
    (comp (ref "L1")
      (value "33uH")
      (footprint "eagle-import:NR8040T330")
      (fields (field (name "MPN") "NR8040T330M"))
      (libsource (lib "eagle-import") (part "RT8040T330"))
    )
    (comp (ref "L2")
      (value "33uH")
      (footprint "eagle-import:NR8040T330")
      (fields (field (name "MPN") "NR8040T330M"))
      (libsource (lib "eagle-import") (part "RT8040T330"))
    )
    (comp (ref "LED0")
      (value "blue")
      (footprint "eagle-import:CHIP-LED0603")
      (fields (field (name "MPN") "Q65110A7211"))
      (libsource (lib "eagle-import") (part "LEDCHIP-LED0603"))
    )
    (comp (ref "LED1")
      (value "blue")
      (footprint "eagle-import:CHIP-LED0603")
      (fields (field (name "MPN") "Q65110A7211"))
      (libsource (lib "eagle-import") (part "LEDCHIP-LED0603"))
    )
    (comp (ref "LED2")
      (value "blue")
      (footprint "eagle-import:CHIP-LED0603")
      (fields (field (name "MPN") "Q65110A7211"))
      (libsource (lib "eagle-import") (part "LEDCHIP-LED0603"))
    )
    (comp (ref "LED3")
      (value "blue")
      (footprint "eagle-import:CHIP-LED0603")
      (fields (field (name "MPN") "Q65110A7211"))
      (libsource (lib "eagle-import") (part "LEDCHIP-LED0603"))
    )
    (comp (ref "LED4")
      (value "blue")
      (footprint "eagle-import:CHIP-LED0603")
      (fields (field (name "MPN") "Q65110A7211"))
      (libsource (lib "eagle-import") (part "LEDCHIP-LED0603"))
    )
    (comp (ref "LED5")
      (value "blue")
      (footprint "eagle-import:CHIP-LED0603")
      (fields (field (name "MPN") "Q65110A7211"))
      (libsource (lib "eagle-import") (part "LEDCHIP-LED0603"))
    )
    (comp (ref "LED6")
      (value "blue")
      (footprint "eagle-import:CHIP-LED0603")
      (fields (field (name "MPN") "Q65110A7211"))
      (libsource (lib "eagle-import") (part "LEDCHIP-LED0603"))
    )
    (comp (ref "LED7")
      (value "blue")
      (footprint "eagle-import:CHIP-LED0603")
      (fields (field (name "MPN") "Q65110A7211"))
      (libsource (lib "eagle-import") (part "LEDCHIP-LED0603"))
    )
    (comp (ref "LED8")
      (value "blue")
      (footprint "eagle-import:CHIP-LED0603")
      (fields (field (name "MPN") "Q65110A7211"))
      (libsource (lib "eagle-import") (part "LEDCHIP-LED0603"))
    )
    (comp (ref "LOGO1")
      (value "OSHW_LOGO_FILLX0200-NT")
      (footprint "eagle-import:OSHW_FILLX200_NOTEXT")
      (libsource (lib "eagle-import") (part "OSHW_LOGO_FILLX0200-NT"))
    )
    (comp (ref "P8")
      (value "F-2X23-")
      (footprint "eagle-import:DIL-100-2X23")
      (fields (field (name "MPN") "SSHQ-123-D-08-F-LF"))
      (libsource (lib "eagle-import") (part "F-2X23-"))
    )
    (comp (ref "P9")
      (value "F-2X23-")
      (footprint "eagle-import:DIL-100-2X23")
      (fields (field (name "MPN") "SSHQ-123-D-08-F-LF"))
      (libsource (lib "eagle-import") (part "F-2X23-"))
    )
    (comp (ref "Q1")
      (value "AON6758")
      (footprint "eagle-import:8-DFN-EP-(5X6)")
      (fields (field (name "MPN") "SIRA34DP-T1-GE3"))
      (libsource (lib "eagle-import") (part "AON6758"))
    )
    (comp (ref "Q2")
      (value "AON6758")
      (footprint "eagle-import:8-DFN-EP-(5X6)")
      (fields (field (name "MPN") "SIRA34DP-T1-GE3"))
      (libsource (lib "eagle-import") (part "AON6758"))
    )
    (comp (ref "Q3")
      (value "AON6758")
      (footprint "eagle-import:8-DFN-EP-(5X6)")
      (fields (field (name "MPN") "SIRA34DP-T1-GE3"))
      (libsource (lib "eagle-import") (part "AON6758"))
    )
    (comp (ref "Q4")
      (value "NPN-TRANSISTOR_SOT23")
      (footprint "eagle-import:SOT23")
      (fields (field (name "MPN") "AO7400"))
      (libsource (lib "eagle-import") (part "NPN-TRANSISTOR_SOT23"))
    )
    (comp (ref "Q5")
      (value "NPN-TRANSISTOR_SOT23")
      (footprint "eagle-import:SOT23")
      (fields (field (name "MPN") "AO7400"))
      (libsource (lib "eagle-import") (part "NPN-TRANSISTOR_SOT23"))
    )
    (comp (ref "Q6")
      (value "NPN-TRANSISTOR_SOT23")
      (footprint "eagle-import:SOT23")
      (fields (field (name "MPN") "AO7400"))
      (libsource (lib "eagle-import") (part "NPN-TRANSISTOR_SOT23"))
    )
    (comp (ref "Q7")
      (value "NPN-TRANSISTOR_SOT23")
      (footprint "eagle-import:SOT23")
      (fields (field (name "MPN") "AO7400"))
      (libsource (lib "eagle-import") (part "NPN-TRANSISTOR_SOT23"))
    )
    (comp (ref "R1")
      (value "0.1R")
      (footprint "eagle-import:R0805")
      (fields (field (name "MPN") "RL1220S-R10-F"))
      (libsource (lib "eagle-import") (part "R-EU_R0805"))
    )
    (comp (ref "R2")
      (value "0.1R")
      (footprint "eagle-import:R0805")
      (fields (field (name "MPN") "RL1220S-R10-F"))
      (libsource (lib "eagle-import") (part "R-EU_R0805"))
    )
    (comp (ref "R3")
      (value "0.1R")
      (footprint "eagle-import:R0805")
      (fields (field (name "MPN") "RL1220S-R10-F"))
      (libsource (lib "eagle-import") (part "R-EU_R0805"))
    )
    (comp (ref "R4")
      (value "0.1R")
      (footprint "eagle-import:R0805")
      (fields (field (name "MPN") "RL1220S-R10-F"))
      (libsource (lib "eagle-import") (part "R-EU_R0805"))
    )
    (comp (ref "R5")
      (value "4.7K")
      (footprint "eagle-import:R0402")
      (fields (field (name "MPN") "RC0402JR-074K7L"))
      (libsource (lib "eagle-import") (part "R-EU_R0402"))
    )
    (comp (ref "R6")
      (value "10K")
      (footprint "eagle-import:R0402")
      (fields (field (name "MPN") "RC0402FR-0710KL"))
      (libsource (lib "eagle-import") (part "R-EU_R0402"))
    )
    (comp (ref "R7")
      (value "0.1R")
      (footprint "eagle-import:R0805")
      (fields (field (name "MPN") "RL1220S-R10-F"))
      (libsource (lib "eagle-import") (part "R-EU_R0805"))
    )
    (comp (ref "R8")
      (value "0.1R")
      (footprint "eagle-import:R0805")
      (fields (field (name "MPN") "RL1220S-R10-F"))
      (libsource (lib "eagle-import") (part "R-EU_R0805"))
    )
    (comp (ref "R9")
      (value "0.1R")
      (footprint "eagle-import:R0805")
      (fields (field (name "MPN") "RL1220S-R10-F"))
      (libsource (lib "eagle-import") (part "R-EU_R0805"))
    )
    (comp (ref "R10")
      (value "0.1R")
      (footprint "eagle-import:R0805")
      (fields (field (name "MPN") "RL1220S-R10-F"))
      (libsource (lib "eagle-import") (part "R-EU_R0805"))
    )
    (comp (ref "R11")
      (value "4.7K")
      (footprint "eagle-import:R0402")
      (fields (field (name "MPN") "RC0402JR-074K7L"))
      (libsource (lib "eagle-import") (part "R-EU_R0402"))
    )
    (comp (ref "R12")
      (value "44.3K,1%")
      (footprint "eagle-import:R0402")
      (fields (field (name "MPN") "RC1005F4422CS"))
      (libsource (lib "eagle-import") (part "R-EU_R0402"))
    )
    (comp (ref "R13")
      (value "4K7, 1%")
      (footprint "eagle-import:R0402")
      (fields (field (name "MPN") "RC0402FR-074K7L"))
      (libsource (lib "eagle-import") (part "R-EU_R0402"))
    )
    (comp (ref "R14")
      (value "4.7K")
      (footprint "eagle-import:R0402")
      (fields (field (name "MPN") "RC0402JR-074K7L"))
      (libsource (lib "eagle-import") (part "R-EU_R0402"))
    )
    (comp (ref "R15")
      (value "4.7K")
      (footprint "eagle-import:R0402")
      (fields (field (name "MPN") "RC0402JR-074K7L"))
      (libsource (lib "eagle-import") (part "R-EU_R0402"))
    )
    (comp (ref "R16")
      (value "4.7K")
      (footprint "eagle-import:R0402")
      (fields (field (name "MPN") "RC0402JR-074K7L"))
      (libsource (lib "eagle-import") (part "R-EU_R0402"))
    )
    (comp (ref "R17")
      (value "4K7, 1%")
      (footprint "eagle-import:R0402")
      (fields (field (name "MPN") "RC0402FR-074K7L"))
      (libsource (lib "eagle-import") (part "R-EU_R0402"))
    )
    (comp (ref "R18")
      (value "4K7, 1%")
      (footprint "eagle-import:R0402")
      (fields (field (name "MPN") "RC0402FR-074K7L"))
      (libsource (lib "eagle-import") (part "R-EU_R0402"))
    )
    (comp (ref "R19")
      (value "4.7K")
      (footprint "eagle-import:R0402")
      (fields (field (name "MPN") "RC0402JR-074K7L"))
      (libsource (lib "eagle-import") (part "R-EU_R0402"))
    )
    (comp (ref "R20")
      (value "4.7K")
      (footprint "eagle-import:R0402")
      (fields (field (name "MPN") "RC0402JR-074K7L"))
      (libsource (lib "eagle-import") (part "R-EU_R0402"))
    )
    (comp (ref "R21")
      (value "4.7K")
      (footprint "eagle-import:R0402")
      (fields (field (name "MPN") "RC0402JR-074K7L"))
      (libsource (lib "eagle-import") (part "R-EU_R0402"))
    )
    (comp (ref "R22")
      (value "10K,1%")
      (footprint "eagle-import:R0402")
      (fields (field (name "MPN") "RC0402FR-0710KL"))
      (libsource (lib "eagle-import") (part "R-EU_R0402"))
    )
    (comp (ref "R23")
      (value "4.7K")
      (footprint "eagle-import:R0402")
      (fields (field (name "MPN") "RC0402JR-074K7L"))
      (libsource (lib "eagle-import") (part "R-EU_R0402"))
    )
    (comp (ref "R24")
      (value "4.7K")
      (footprint "eagle-import:R0402")
      (fields (field (name "MPN") "RC0402JR-074K7L"))
      (libsource (lib "eagle-import") (part "R-EU_R0402"))
    )
    (comp (ref "R25")
      (value "4.7K")
      (footprint "eagle-import:R0402")
      (fields (field (name "MPN") "RC0402JR-074K7L"))
      (libsource (lib "eagle-import") (part "R-EU_R0402"))
    )
    (comp (ref "R26")
      (value "39K")
      (footprint "eagle-import:R0402")
      (fields (field (name "MPN") "RC1005J393CS"))
      (libsource (lib "eagle-import") (part "R-EU_R0402"))
    )
    (comp (ref "R27")
      (value "10K")
      (footprint "eagle-import:R0402")
      (fields (field (name "MPN") "RC0402FR-0710KL"))
      (libsource (lib "eagle-import") (part "R-EU_R0402"))
    )
    (comp (ref "R28")
      (value "4.7K")
      (footprint "eagle-import:R0402")
      (fields (field (name "MPN") "RC0402JR-074K7L"))
      (libsource (lib "eagle-import") (part "R-EU_R0402"))
    )
    (comp (ref "R29")
      (value "0.1R")
      (footprint "eagle-import:R0805")
      (fields (field (name "MPN") "RL1220S-R10-F"))
      (libsource (lib "eagle-import") (part "R-EU_R0805"))
    )
    (comp (ref "R30")
      (value "0.1R")
      (footprint "eagle-import:R0805")
      (fields (field (name "MPN") "RL1220S-R10-F"))
      (libsource (lib "eagle-import") (part "R-EU_R0805"))
    )
    (comp (ref "R31")
      (value "10K")
      (footprint "eagle-import:R0402")
      (fields (field (name "MPN") "RC0402FR-0710KL"))
      (libsource (lib "eagle-import") (part "R-EU_R0402"))
    )
    (comp (ref "R32")
      (value "4.7K")
      (footprint "eagle-import:R0402")
      (fields (field (name "MPN") "RC0402JR-074K7L"))
      (libsource (lib "eagle-import") (part "R-EU_R0402"))
    )
    (comp (ref "R33")
      (value "4.7K")
      (footprint "eagle-import:R0402")
      (fields (field (name "MPN") "RC0402JR-074K7L"))
      (libsource (lib "eagle-import") (part "R-EU_R0402"))
    )
    (comp (ref "R34")
      (value "4.7K")
      (footprint "eagle-import:R0402")
      (fields (field (name "MPN") "RC0402JR-074K7L"))
      (libsource (lib "eagle-import") (part "R-EU_R0402"))
    )
    (comp (ref "R35")
      (value "10K")
      (footprint "eagle-import:R0402")
      (fields (field (name "MPN") "RC0402FR-0710KL"))
      (libsource (lib "eagle-import") (part "R-EU_R0402"))
    )
    (comp (ref "R36")
      (value "4.7K")
      (footprint "eagle-import:R0402")
      (fields (field (name "MPN") "RC0402JR-074K7L"))
      (libsource (lib "eagle-import") (part "R-EU_R0402"))
    )
    (comp (ref "R37")
      (value "10K")
      (footprint "eagle-import:R0402")
      (fields (field (name "MPN") "RC0402FR-0710KL"))
      (libsource (lib "eagle-import") (part "R-EU_R0402"))
    )
    (comp (ref "R38")
      (value "10K")
      (footprint "eagle-import:R0402")
      (fields (field (name "MPN") "RC0402FR-0710KL"))
      (libsource (lib "eagle-import") (part "R-EU_R0402"))
    )
    (comp (ref "R39")
      (value "10K")
      (footprint "eagle-import:R0402")
      (fields (field (name "MPN") "RC0402FR-0710KL"))
      (libsource (lib "eagle-import") (part "R-EU_R0402"))
    )
    (comp (ref "R40")
      (value "10K")
      (footprint "eagle-import:R0402")
      (fields (field (name "MPN") "RC0402FR-0710KL"))
      (libsource (lib "eagle-import") (part "R-EU_R0402"))
    )
    (comp (ref "R41")
      (value "10K")
      (footprint "eagle-import:R0402")
      (fields (field (name "MPN") "RC0402FR-0710KL"))
      (libsource (lib "eagle-import") (part "R-EU_R0402"))
    )
    (comp (ref "R42")
      (value "120K,1%")
      (footprint "eagle-import:R0402")
      (fields (field (name "MPN") "RMCF0402FT120K"))
      (libsource (lib "eagle-import") (part "R-EU_R0402"))
    )
    (comp (ref "R43")
      (value "10K,1%")
      (footprint "eagle-import:R0402")
      (fields (field (name "MPN") "RC0402FR-0710KL"))
      (libsource (lib "eagle-import") (part "R-EU_R0402"))
    )
    (comp (ref "R44")
      (value "39K")
      (footprint "eagle-import:R0402")
      (fields (field (name "MPN") "RC1005J393CS"))
      (libsource (lib "eagle-import") (part "R-EU_R0402"))
    )
    (comp (ref "R45")
      (value "4.7K")
      (footprint "eagle-import:R0402")
      (fields (field (name "MPN") "RC0402JR-074K7L"))
      (libsource (lib "eagle-import") (part "R-EU_R0402"))
    )
    (comp (ref "R46")
      (value "4.7K")
      (footprint "eagle-import:R0402")
      (fields (field (name "MPN") "RC0402JR-074K7L"))
      (libsource (lib "eagle-import") (part "R-EU_R0402"))
    )
    (comp (ref "R47")
      (value "4.7K")
      (footprint "eagle-import:R0402")
      (fields (field (name "MPN") "RC0402JR-074K7L"))
      (libsource (lib "eagle-import") (part "R-EU_R0402"))
    )
    (comp (ref "R48")
      (value "4.7K")
      (footprint "eagle-import:R0402")
      (fields (field (name "MPN") "RC0402JR-074K7L"))
      (libsource (lib "eagle-import") (part "R-EU_R0402"))
    )
    (comp (ref "R49")
      (value "10K")
      (footprint "eagle-import:R0402")
      (fields (field (name "MPN") "RC0402FR-0710KL"))
      (libsource (lib "eagle-import") (part "R-EU_R0402"))
    )
    (comp (ref "R50")
      (value "10K")
      (footprint "eagle-import:R0402")
      (fields (field (name "MPN") "RC0402FR-0710KL"))
      (libsource (lib "eagle-import") (part "R-EU_R0402"))
    )
    (comp (ref "R51")
      (value "4.7K")
      (footprint "eagle-import:R0402")
      (fields (field (name "MPN") "RC0402JR-074K7L"))
      (libsource (lib "eagle-import") (part "R-EU_R0402"))
    )
    (comp (ref "R52")
      (value "2.2R")
      (footprint "eagle-import:R0402")
      (fields (field (name "MPN") "RC1005J2R2CS"))
      (libsource (lib "eagle-import") (part "R-EU_R0402"))
    )
    (comp (ref "R53")
      (value "2.2R")
      (footprint "eagle-import:R0402")
      (fields (field (name "MPN") "RC1005J2R2CS"))
      (libsource (lib "eagle-import") (part "R-EU_R0402"))
    )
    (comp (ref "R54")
      (value "4.7K")
      (footprint "eagle-import:R0402")
      (fields (field (name "MPN") "RC0402JR-074K7L"))
      (libsource (lib "eagle-import") (part "R-EU_R0402"))
    )
    (comp (ref "R55")
      (value "4.7K")
      (footprint "eagle-import:R0402")
      (fields (field (name "MPN") "RC0402JR-074K7L"))
      (libsource (lib "eagle-import") (part "R-EU_R0402"))
    )
    (comp (ref "R56")
      (value "4.7K")
      (footprint "eagle-import:R0402")
      (fields (field (name "MPN") "RC0402JR-074K7L"))
      (libsource (lib "eagle-import") (part "R-EU_R0402"))
    )
    (comp (ref "R57")
      (value "4.7K")
      (footprint "eagle-import:R0402")
      (fields (field (name "MPN") "RC0402JR-074K7L"))
      (libsource (lib "eagle-import") (part "R-EU_R0402"))
    )
    (comp (ref "R58")
      (value "10K")
      (footprint "eagle-import:R0402")
      (fields (field (name "MPN") "RC0402FR-0710KL"))
      (libsource (lib "eagle-import") (part "R-EU_R0402"))
    )
    (comp (ref "R59")
      (value "2.2R")
      (footprint "eagle-import:R0402")
      (fields (field (name "MPN") "RC1005J2R2CS"))
      (libsource (lib "eagle-import") (part "R-EU_R0402"))
    )
    (comp (ref "R60")
      (value "10K")
      (footprint "eagle-import:R0402")
      (fields (field (name "MPN") "RC0402FR-0710KL"))
      (libsource (lib "eagle-import") (part "R-EU_R0402"))
    )
    (comp (ref "R61")
      (value "4.7K")
      (footprint "eagle-import:R0402")
      (fields (field (name "MPN") "RC0402JR-074K7L"))
      (libsource (lib "eagle-import") (part "R-EU_R0402"))
    )
    (comp (ref "R62")
      (value "4.7K")
      (footprint "eagle-import:R0402")
      (fields (field (name "MPN") "RC0402JR-074K7L"))
      (libsource (lib "eagle-import") (part "R-EU_R0402"))
    )
    (comp (ref "R63")
      (value "4.7K")
      (footprint "eagle-import:R0402")
      (fields (field (name "MPN") "RC0402JR-074K7L"))
      (libsource (lib "eagle-import") (part "R-EU_R0402"))
    )
    (comp (ref "R64")
      (value "4.7K")
      (footprint "eagle-import:R0402")
      (fields (field (name "MPN") "RC0402JR-074K7L"))
      (libsource (lib "eagle-import") (part "R-EU_R0402"))
    )
    (comp (ref "R65")
      (value "4.7K")
      (footprint "eagle-import:R0402")
      (fields (field (name "MPN") "RC0402JR-074K7L"))
      (libsource (lib "eagle-import") (part "R-EU_R0402"))
    )
    (comp (ref "R66")
      (value "4.7K")
      (footprint "eagle-import:R0402")
      (fields (field (name "MPN") "RC0402JR-074K7L"))
      (libsource (lib "eagle-import") (part "R-EU_R0402"))
    )
    (comp (ref "R70")
      (value "2.2R")
      (footprint "eagle-import:R0402")
      (fields (field (name "MPN") "RC1005J2R2CS"))
      (libsource (lib "eagle-import") (part "R-EU_R0402"))
    )
    (comp (ref "R71")
      (value "2.2R")
      (footprint "eagle-import:R0402")
      (fields (field (name "MPN") "RC1005J2R2CS"))
      (libsource (lib "eagle-import") (part "R-EU_R0402"))
    )
    (comp (ref "SV2")
      (value "MA03-1")
      (footprint "eagle-import:MA03-1")
      (libsource (lib "eagle-import") (part "MA03-1"))
    )
    (comp (ref "U$4")
      (value "CC-BY-SA")
      (footprint "eagle-import:CC-BY-SA")
      (libsource (lib "eagle-import") (part "CC-BY-SA"))
    )
    (comp (ref "U1")
      (value "SN74AHC595PW")
      (footprint "eagle-import:SOP65P640X120-16N")
      (fields (field (name "MPN") "MC74HC595ADTR2G"))
      (libsource (lib "eagle-import") (part "SN74AHC595PW"))
    )
    (comp (ref "U2")
      (value "SN74AHC595PW")
      (footprint "eagle-import:SOP65P640X120-16N")
      (fields (field (name "MPN") "MC74HC595ADTR2G"))
      (libsource (lib "eagle-import") (part "SN74AHC595PW"))
    )
    (comp (ref "U3")
      (value "SN74AHC595PW")
      (footprint "eagle-import:SOP65P640X120-16N")
      (fields (field (name "MPN") "MC74HC595ADTR2G"))
      (libsource (lib "eagle-import") (part "SN74AHC595PW"))
    )
    (comp (ref "U4")
      (value "SN74AHC595PW")
      (footprint "eagle-import:SOP65P640X120-16N")
      (fields (field (name "MPN") "MC74HC595ADTR2G"))
      (libsource (lib "eagle-import") (part "SN74AHC595PW"))
    )
    (comp (ref "U5")
      (value "SN74AHC595PW")
      (footprint "eagle-import:SOP65P640X120-16N")
      (fields (field (name "MPN") "MC74HC595ADTR2G"))
      (libsource (lib "eagle-import") (part "SN74AHC595PW"))
    )
    (comp (ref "U6")
      (value "RT8268")
      (footprint "eagle-import:MSOP10")
      (fields (field (name "MPN") "RT8268GFP"))
      (libsource (lib "eagle-import") (part "RT8268"))
    )
    (comp (ref "U10")
      (value "RT8268")
      (footprint "eagle-import:MSOP10")
      (fields (field (name "MPN") "RT8268GFP"))
      (libsource (lib "eagle-import") (part "RT8268"))
    )
    (comp (ref "U11")
      (value "PCA9685PW")
      (footprint "eagle-import:SOP65P640X110-28N")
      (fields (field (name "MPN") "PCA9685PW,112"))
      (libsource (lib "eagle-import") (part "PCA9685PW"))
    )
    (comp (ref "U18")
      (value "CAT24C256")
      (footprint "eagle-import:SOIC127P600X175-8N")
      (fields (field (name "MPN") "CAT24C256WI-GT3"))
      (libsource (lib "eagle-import") (part "CAT24C256"))
    )
    (comp (ref "U19")
      (value "CD4050BD")
      (footprint "eagle-import:SOIC127P600X175-16N")
      (fields (field (name "MPN") "CD4050BDR"))
      (libsource (lib "eagle-import") (part "CD4050BD"))
    )
    (comp (ref "X1")
      (value "22-05-7038-03")
      (footprint "eagle-import:7395-03")
      (fields (field (name "MPN") "640455-3"))
      (libsource (lib "eagle-import") (part "22-?-0305-7038"))
    )
    (comp (ref "X2")
      (value "MSTBA4")
      (footprint "eagle-import:MSTBA4")
      (fields
        (field (name "MF") "FARNELL")
        (field (name "MPN") "1757268")
        (field (name "MPN_1") "39532-1004")
      )
      (libsource (lib "eagle-import") (part "MSTBA4"))
    )
    (comp (ref "X3")
      (value "MSTBA2")
      (footprint "eagle-import:MSTBA2")
      (fields
        (field (name "MF") "FARNELL")
        (field (name "MPN") "1757242")
        (field (name "MPN_1") "39532-1002")
      )
      (libsource (lib "eagle-import") (part "MSTBA2"))
    )
    (comp (ref "X4")
      (value "22-05-7028-02")
      (footprint "eagle-import:7395-02")
      (fields (field (name "MPN") "640455-2"))
      (libsource (lib "eagle-import") (part "22-?-0205-7028"))
    )
    (comp (ref "X5")
      (value "22-05-7028-02")
      (footprint "eagle-import:7395-02")
      (fields (field (name "MPN") "640455-2"))
      (libsource (lib "eagle-import") (part "22-?-0205-7028"))
    )
    (comp (ref "X6")
      (value "22-05-7028-02")
      (footprint "eagle-import:7395-02")
      (fields (field (name "MPN") "640455-2"))
      (libsource (lib "eagle-import") (part "22-?-0205-7028"))
    )
    (comp (ref "X7")
      (value "22-05-7028-02")
      (footprint "eagle-import:7395-02")
      (fields (field (name "MPN") "640455-2"))
      (libsource (lib "eagle-import") (part "22-?-0205-7028"))
    )
    (comp (ref "X8")
      (value "22-05-7028-02")
      (footprint "eagle-import:7395-02")
      (fields (field (name "MPN") "640455-2"))
      (libsource (lib "eagle-import") (part "22-?-0205-7028"))
    )
    (comp (ref "X9")
      (value "22-05-7028-02")
      (footprint "eagle-import:7395-02")
      (fields (field (name "MPN") "640455-2"))
      (libsource (lib "eagle-import") (part "22-?-0205-7028"))
    )
    (comp (ref "X10")
      (value "22-05-7038-03")
      (footprint "eagle-import:7395-03")
      (fields (field (name "MPN") "640455-3"))
      (libsource (lib "eagle-import") (part "22-?-0305-7038"))
    )
    (comp (ref "X11")
      (value "22-05-7028-02")
      (footprint "eagle-import:7395-02")
      (fields (field (name "MPN") "640455-2"))
      (libsource (lib "eagle-import") (part "22-?-0205-7028"))
    )
    (comp (ref "X12")
      (value "22-05-7048-04")
      (footprint "eagle-import:7395-04")
      (fields (field (name "MPN") "640455-4"))
      (libsource (lib "eagle-import") (part "22-?-0405-7048"))
    )
    (comp (ref "X13")
      (value "22-05-7038-03")
      (footprint "eagle-import:7395-03")
      (fields (field (name "MPN") "640455-3"))
      (libsource (lib "eagle-import") (part "22-?-0305-7038"))
    )
    (comp (ref "X14")
      (value "22-05-7048-04")
      (footprint "eagle-import:7395-04")
      (fields (field (name "MPN") "640455-4"))
      (libsource (lib "eagle-import") (part "22-?-0405-7048"))
    )
    (comp (ref "X15")
      (value "22-05-7048-04")
      (footprint "eagle-import:7395-04")
      (fields (field (name "MPN") "640455-4"))
      (libsource (lib "eagle-import") (part "22-?-0405-7048"))
    )
    (comp (ref "X16")
      (value "22-05-7048-04")
      (footprint "eagle-import:7395-04")
      (fields (field (name "MPN") "640455-4"))
      (libsource (lib "eagle-import") (part "22-?-0405-7048"))
    )
    (comp (ref "X17")
      (value "22-05-7048-04")
      (footprint "eagle-import:7395-04")
      (fields (field (name "MPN") "640455-4"))
      (libsource (lib "eagle-import") (part "22-?-0405-7048"))
    )
    (comp (ref "X18")
      (value "22-05-7048-04")
      (footprint "eagle-import:7395-04")
      (fields (field (name "MPN") "640455-4"))
      (libsource (lib "eagle-import") (part "22-?-0405-7048"))
    )
    (comp (ref "X19")
      (value "22-05-7038-03")
      (footprint "eagle-import:7395-03")
      (fields (field (name "MPN") "640455-3"))
      (libsource (lib "eagle-import") (part "22-?-0305-7038"))
    )
    (comp (ref "X20")
      (value "MSTBA4")
      (footprint "eagle-import:MSTBA4")
      (fields
        (field (name "MF") "FARNELL")
        (field (name "MPN") "1757268")
        (field (name "MPN_1") "39532-1004")
      )
      (libsource (lib "eagle-import") (part "MSTBA4"))
    )
    (comp (ref "X21")
      (value "MSTBA2")
      (footprint "eagle-import:MSTBA2")
      (fields
        (field (name "MF") "FARNELL")
        (field (name "MPN") "1757242")
        (field (name "MPN_1") "39532-1002")
      )
      (libsource (lib "eagle-import") (part "MSTBA2"))
    )
    (comp (ref "X22")
      (value "22-05-7038-03")
      (footprint "eagle-import:7395-03")
      (fields (field (name "MPN") "640455-3"))
      (libsource (lib "eagle-import") (part "22-?-0305-7038"))
    )
    (comp (ref "X23")
      (value "22-05-7038-03")
      (footprint "eagle-import:7395-03")
      (fields (field (name "MPN") "640455-3"))
      (libsource (lib "eagle-import") (part "22-?-0305-7038"))
    )
    (comp (ref "XC1")
      (value "MSTBA4-CONNECTOR")
      (footprint "eagle-import:MSTBA4-CONNECTOR")
      (fields (field (name "MPN") "39530-0004"))
      (libsource (lib "eagle-import") (part "MSTBA4-CONNECTOR"))
    )
    (comp (ref "XC2")
      (value "MSTBA4-CONNECTOR")
      (footprint "eagle-import:MSTBA4-CONNECTOR")
      (fields (field (name "MPN") "39530-0004"))
      (libsource (lib "eagle-import") (part "MSTBA4-CONNECTOR"))
    )
    (comp (ref "XC3")
      (value "MSTBV2-CONNECTOR")
      (footprint "eagle-import:MSTBA2-CONNECTOR")
      (fields (field (name "MPN") "39530-0002"))
      (libsource (lib "eagle-import") (part "MSTBV2-CONNECTOR"))
    )
    (comp (ref "XC4")
      (value "MSTBV2-CONNECTOR")
      (footprint "eagle-import:MSTBA2-CONNECTOR")
      (fields (field (name "MPN") "39530-0002"))
      (libsource (lib "eagle-import") (part "MSTBV2-CONNECTOR"))
    )
  )
  (nets
    (net (code "1") (name "+3V3") (class "Default")
      (node (ref "3.3V") (pin "TP") (pinfunction "TP_TP") (pintype "input"))
      (node (ref "C13") (pin "1") (pinfunction "1_1") (pintype "passive"))
      (node (ref "C14") (pin "1") (pinfunction "1_1") (pintype "passive"))
      (node (ref "C15") (pin "1") (pinfunction "1_1") (pintype "passive"))
      (node (ref "C2") (pin "1") (pinfunction "1_1") (pintype "passive"))
      (node (ref "C23") (pin "1") (pinfunction "1_1") (pintype "passive"))
      (node (ref "C30") (pin "1") (pinfunction "1_1") (pintype "passive"))
      (node (ref "C41") (pin "1") (pinfunction "1_1") (pintype "passive"))
      (node (ref "C42") (pin "1") (pinfunction "1_1") (pintype "passive"))
      (node (ref "C44") (pin "1") (pinfunction "1_1") (pintype "passive"))
      (node (ref "C5") (pin "1") (pinfunction "1_1") (pintype "passive"))
      (node (ref "C61") (pin "1") (pinfunction "1_1") (pintype "passive"))
      (node (ref "C63") (pin "1") (pinfunction "1_1") (pintype "passive"))
      (node (ref "C84") (pin "1") (pinfunction "1_1") (pintype "passive"))
      (node (ref "C85") (pin "1") (pinfunction "1_1") (pintype "passive"))
      (node (ref "C86") (pin "1") (pinfunction "1_1") (pintype "passive"))
      (node (ref "C87") (pin "1") (pinfunction "1_1") (pintype "passive"))
      (node (ref "C88") (pin "1") (pinfunction "1_1") (pintype "passive"))
      (node (ref "IC1") (pin "8") (pinfunction "VCC_IO_8") (pintype "bidirectional"))
      (node (ref "IC10") (pin "5") (pinfunction "VCC_5") (pintype "power_in"))
      (node (ref "IC11") (pin "5") (pinfunction "VCC_5") (pintype "power_in"))
      (node (ref "IC12") (pin "8") (pinfunction "VCC_IO_8") (pintype "bidirectional"))
      (node (ref "IC13") (pin "5") (pinfunction "VCC_5") (pintype "power_in"))
      (node (ref "IC14") (pin "5") (pinfunction "VCC_5") (pintype "power_in"))
      (node (ref "IC15") (pin "8") (pinfunction "VCC_IO_8") (pintype "bidirectional"))
      (node (ref "IC16") (pin "5") (pinfunction "VCC_5") (pintype "power_in"))
      (node (ref "IC17") (pin "5") (pinfunction "VCC_5") (pintype "power_in"))
      (node (ref "IC18") (pin "5") (pinfunction "VCC_5") (pintype "power_in"))
      (node (ref "IC19") (pin "5") (pinfunction "VCC_5") (pintype "power_in"))
      (node (ref "IC2") (pin "8") (pinfunction "VCC_IO_8") (pintype "bidirectional"))
      (node (ref "IC20") (pin "5") (pinfunction "VCC_5") (pintype "power_in"))
      (node (ref "IC21") (pin "5") (pinfunction "VCC_5") (pintype "power_in"))
      (node (ref "IC22") (pin "5") (pinfunction "VCC_5") (pintype "power_in"))
      (node (ref "IC3") (pin "5") (pinfunction "VCC_5") (pintype "power_in"))
      (node (ref "IC4") (pin "5") (pinfunction "VCC_5") (pintype "power_in"))
      (node (ref "IC5") (pin "8") (pinfunction "VCC_IO_8") (pintype "bidirectional"))
      (node (ref "IC8") (pin "5") (pinfunction "VCC_5") (pintype "power_in"))
      (node (ref "IC9") (pin "5") (pinfunction "VCC_5") (pintype "power_in"))
      (node (ref "P9") (pin "3") (pinfunction "3_3") (pintype "passive"))
      (node (ref "P9") (pin "4") (pinfunction "4_4") (pintype "passive"))
      (node (ref "R23") (pin "2") (pinfunction "2_2") (pintype "passive"))
      (node (ref "R24") (pin "2") (pinfunction "2_2") (pintype "passive"))
      (node (ref "R28") (pin "2") (pinfunction "2_2") (pintype "passive"))
      (node (ref "R36") (pin "2") (pinfunction "2_2") (pintype "passive"))
      (node (ref "R51") (pin "2") (pinfunction "2_2") (pintype "passive"))
      (node (ref "R54") (pin "2") (pinfunction "2_2") (pintype "passive"))
      (node (ref "U1") (pin "10") (pinfunction "~{SRCLR}_10") (pintype "input"))
      (node (ref "U1") (pin "16") (pinfunction "VCC_16") (pintype "power_in"))
      (node (ref "U18") (pin "3") (pinfunction "A2_3") (pintype "input"))
      (node (ref "U18") (pin "8") (pinfunction "VCC_8") (pintype "power_in"))
      (node (ref "U19") (pin "1") (pinfunction "VCC_1") (pintype "power_in"))
      (node (ref "U2") (pin "10") (pinfunction "~{SRCLR}_10") (pintype "input"))
      (node (ref "U2") (pin "16") (pinfunction "VCC_16") (pintype "power_in"))
      (node (ref "U3") (pin "10") (pinfunction "~{SRCLR}_10") (pintype "input"))
      (node (ref "U3") (pin "16") (pinfunction "VCC_16") (pintype "power_in"))
      (node (ref "U4") (pin "10") (pinfunction "~{SRCLR}_10") (pintype "input"))
      (node (ref "U4") (pin "16") (pinfunction "VCC_16") (pintype "power_in"))
      (node (ref "U5") (pin "10") (pinfunction "~{SRCLR}_10") (pintype "input"))
      (node (ref "U5") (pin "16") (pinfunction "VCC_16") (pintype "power_in"))
      (node (ref "X23") (pin "1") (pinfunction "S_1") (pintype "passive"))
    )
    (net (code "2") (name "+5V") (class "Default")
      (node (ref "5V") (pin "TP") (pinfunction "TP_TP") (pintype "input"))
      (node (ref "C48") (pin "1") (pinfunction "1_1") (pintype "passive"))
      (node (ref "C80") (pin "1") (pinfunction "1_1") (pintype "passive"))
      (node (ref "C82") (pin "1") (pinfunction "1_1") (pintype "passive"))
      (node (ref "C83") (pin "1") (pinfunction "1_1") (pintype "passive"))
      (node (ref "IC6") (pin "5") (pinfunction "VCC_5") (pintype "power_in"))
      (node (ref "IC7") (pin "5") (pinfunction "VCC_5") (pintype "power_in"))
      (node (ref "L1") (pin "P$1") (pinfunction "P$1_P$1") (pintype "passive"))
      (node (ref "P9") (pin "5") (pinfunction "5_5") (pintype "passive"))
      (node (ref "P9") (pin "6") (pinfunction "6_6") (pintype "passive"))
      (node (ref "R12") (pin "1") (pinfunction "1_1") (pintype "passive"))
      (node (ref "R61") (pin "2") (pinfunction "2_2") (pintype "passive"))
      (node (ref "R62") (pin "2") (pinfunction "2_2") (pintype "passive"))
      (node (ref "R63") (pin "2") (pinfunction "2_2") (pintype "passive"))
      (node (ref "R64") (pin "2") (pinfunction "2_2") (pintype "passive"))
      (node (ref "R65") (pin "2") (pinfunction "2_2") (pintype "passive"))
      (node (ref "R66") (pin "2") (pinfunction "2_2") (pintype "passive"))
      (node (ref "X1") (pin "3") (pinfunction "S_3") (pintype "passive"))
      (node (ref "X10") (pin "3") (pinfunction "S_3") (pintype "passive"))
      (node (ref "X12") (pin "3") (pinfunction "S_3") (pintype "passive"))
      (node (ref "X13") (pin "3") (pinfunction "S_3") (pintype "passive"))
      (node (ref "X19") (pin "3") (pinfunction "S_3") (pintype "passive"))
      (node (ref "X22") (pin "3") (pinfunction "S_3") (pintype "passive"))
    )
    (net (code "3") (name "/DALLAS_W1") (class "Default")
      (node (ref "P9") (pin "22") (pinfunction "22_22") (pintype "passive"))
      (node (ref "X23") (pin "2") (pinfunction "S_2") (pintype "passive"))
    )
    (net (code "4") (name "/DIR_E") (class "Default")
      (node (ref "IC12") (pin "7") (pinfunction "REFR_DIR_7") (pintype "bidirectional"))
      (node (ref "P8") (pin "15") (pinfunction "15_15") (pintype "passive"))
    )
    (net (code "5") (name "/DIR_H") (class "Default")
      (node (ref "IC15") (pin "7") (pinfunction "REFR_DIR_7") (pintype "bidirectional"))
      (node (ref "P8") (pin "16") (pinfunction "16_16") (pintype "passive"))
    )
    (net (code "6") (name "/DIR_X") (class "Default")
      (node (ref "IC1") (pin "7") (pinfunction "REFR_DIR_7") (pintype "bidirectional"))
      (node (ref "P8") (pin "26") (pinfunction "26_26") (pintype "passive"))
    )
    (net (code "7") (name "/DIR_Y") (class "Default")
      (node (ref "IC2") (pin "7") (pinfunction "REFR_DIR_7") (pintype "bidirectional"))
      (node (ref "P8") (pin "19") (pinfunction "19_19") (pintype "passive"))
    )
    (net (code "8") (name "/DIR_Z") (class "Default")
      (node (ref "IC5") (pin "7") (pinfunction "REFR_DIR_7") (pintype "bidirectional"))
      (node (ref "P8") (pin "14") (pinfunction "14_14") (pintype "passive"))
    )
    (net (code "9") (name "/ENABLE") (class "Default")
      (node (ref "P9") (pin "41") (pinfunction "41_41") (pintype "passive"))
      (node (ref "R23") (pin "1") (pinfunction "1_1") (pintype "passive"))
      (node (ref "U11") (pin "23") (pinfunction "~{OE}_23") (pintype "input"))
    )
    (net (code "10") (name "/ENABLE_E") (class "Default")
      (node (ref "IC12") (pin "22") (pinfunction "DRV_ENN_CFG6_22") (pintype "bidirectional"))
      (node (ref "IC19") (pin "4") (pinfunction "O_4") (pintype "output"))
    )
    (net (code "11") (name "/ENABLE_H") (class "Default")
      (node (ref "IC15") (pin "22") (pinfunction "DRV_ENN_CFG6_22") (pintype "bidirectional"))
      (node (ref "IC22") (pin "4") (pinfunction "O_4") (pintype "output"))
    )
    (net (code "12") (name "/ENABLE_X") (class "Default")
      (node (ref "IC1") (pin "22") (pinfunction "DRV_ENN_CFG6_22") (pintype "bidirectional"))
      (node (ref "IC18") (pin "4") (pinfunction "O_4") (pintype "output"))
    )
    (net (code "13") (name "/ENABLE_Y") (class "Default")
      (node (ref "IC2") (pin "22") (pinfunction "DRV_ENN_CFG6_22") (pintype "bidirectional"))
      (node (ref "IC20") (pin "4") (pinfunction "O_4") (pintype "output"))
    )
    (net (code "14") (name "/ENABLE_Z") (class "Default")
      (node (ref "IC21") (pin "4") (pinfunction "O_4") (pintype "output"))
      (node (ref "IC5") (pin "22") (pinfunction "DRV_ENN_CFG6_22") (pintype "bidirectional"))
    )
    (net (code "15") (name "/END_STOP_X_1") (class "Default")
      (node (ref "P9") (pin "25") (pinfunction "25_25") (pintype "passive"))
      (node (ref "U19") (pin "2") (pinfunction "G=A_2") (pintype "output"))
    )
    (net (code "16") (name "/END_STOP_X_1_IN") (class "Default")
      (node (ref "R61") (pin "1") (pinfunction "1_1") (pintype "passive"))
      (node (ref "U19") (pin "3") (pinfunction "A_3") (pintype "input"))
      (node (ref "X22") (pin "1") (pinfunction "S_1") (pintype "passive"))
    )
    (net (code "17") (name "/END_STOP_X_2") (class "Default")
      (node (ref "P9") (pin "11") (pinfunction "11_11") (pintype "passive"))
      (node (ref "U19") (pin "10") (pinfunction "J=D_10") (pintype "output"))
    )
    (net (code "18") (name "/END_STOP_X_2_IN") (class "Default")
      (node (ref "IC6") (pin "4") (pinfunction "O_4") (pintype "output"))
      (node (ref "R64") (pin "1") (pinfunction "1_1") (pintype "passive"))
      (node (ref "U19") (pin "9") (pinfunction "D_9") (pintype "input"))
      (node (ref "X10") (pin "1") (pinfunction "S_1") (pintype "passive"))
    )
    (net (code "19") (name "/END_STOP_Y_1") (class "Default")
      (node (ref "P9") (pin "23") (pinfunction "23_23") (pintype "passive"))
      (node (ref "U19") (pin "4") (pinfunction "H=B_4") (pintype "output"))
    )
    (net (code "20") (name "/END_STOP_Y_1_IN") (class "Default")
      (node (ref "R62") (pin "1") (pinfunction "1_1") (pintype "passive"))
      (node (ref "U19") (pin "5") (pinfunction "B_5") (pintype "input"))
      (node (ref "X1") (pin "1") (pinfunction "S_1") (pintype "passive"))
    )
    (net (code "21") (name "/END_STOP_Y_2") (class "Default")
      (node (ref "P9") (pin "28") (pinfunction "28_28") (pintype "passive"))
      (node (ref "U19") (pin "12") (pinfunction "K=E_12") (pintype "output"))
    )
    (net (code "22") (name "/END_STOP_Y_2_IN") (class "Default")
      (node (ref "IC7") (pin "4") (pinfunction "O_4") (pintype "output"))
      (node (ref "R65") (pin "1") (pinfunction "1_1") (pintype "passive"))
      (node (ref "U19") (pin "11") (pinfunction "E_11") (pintype "input"))
      (node (ref "X19") (pin "1") (pinfunction "S_1") (pintype "passive"))
    )
    (net (code "23") (name "/END_STOP_Z_1") (class "Default")
      (node (ref "P9") (pin "13") (pinfunction "13_13") (pintype "passive"))
      (node (ref "U19") (pin "6") (pinfunction "I=C_6") (pintype "output"))
    )
    (net (code "24") (name "/END_STOP_Z_1_IN") (class "Default")
      (node (ref "R63") (pin "1") (pinfunction "1_1") (pintype "passive"))
      (node (ref "U19") (pin "7") (pinfunction "C_7") (pintype "input"))
      (node (ref "X13") (pin "1") (pinfunction "S_1") (pintype "passive"))
    )
    (net (code "25") (name "/END_STOP_Z_2") (class "Default")
      (node (ref "P9") (pin "18") (pinfunction "18_18") (pintype "passive"))
      (node (ref "U19") (pin "15") (pinfunction "L=F_15") (pintype "output"))
    )
    (net (code "26") (name "/END_STOP_Z_2_IN") (class "Default")
      (node (ref "R66") (pin "1") (pinfunction "1_1") (pintype "passive"))
      (node (ref "U19") (pin "14") (pinfunction "F_14") (pintype "input"))
      (node (ref "X12") (pin "1") (pinfunction "S_1") (pintype "passive"))
    )
    (net (code "27") (name "/EN_EH") (class "Default")
      (node (ref "IC19") (pin "2") (pinfunction "I_2") (pintype "input"))
      (node (ref "IC22") (pin "2") (pinfunction "I_2") (pintype "input"))
      (node (ref "U4") (pin "15") (pinfunction "QA_15") (pintype "output"))
    )
    (net (code "28") (name "/EN_XYZ") (class "Default")
      (node (ref "IC18") (pin "2") (pinfunction "I_2") (pintype "input"))
      (node (ref "IC20") (pin "2") (pinfunction "I_2") (pintype "input"))
      (node (ref "IC21") (pin "2") (pinfunction "I_2") (pintype "input"))
      (node (ref "U1") (pin "15") (pinfunction "QA_15") (pintype "output"))
    )
    (net (code "29") (name "/FAN0") (class "Default")
      (node (ref "Q6") (pin "1") (pinfunction "B_1") (pintype "passive"))
      (node (ref "R34") (pin "2") (pinfunction "2_2") (pintype "passive"))
      (node (ref "U11") (pin "13") (pinfunction "LED7_13") (pintype "output"))
    )
    (net (code "30") (name "/FAN1") (class "Default")
      (node (ref "Q7") (pin "1") (pinfunction "B_1") (pintype "passive"))
      (node (ref "R33") (pin "2") (pinfunction "2_2") (pintype "passive"))
      (node (ref "U11") (pin "15") (pinfunction "LED8_15") (pintype "output"))
    )
    (net (code "31") (name "/FAN2") (class "Default")
      (node (ref "Q4") (pin "1") (pinfunction "B_1") (pintype "passive"))
      (node (ref "R32") (pin "2") (pinfunction "2_2") (pintype "passive"))
      (node (ref "U11") (pin "16") (pinfunction "LED9_16") (pintype "output"))
    )
    (net (code "32") (name "/FAN3") (class "Default")
      (node (ref "Q5") (pin "1") (pinfunction "B_1") (pintype "passive"))
      (node (ref "R5") (pin "2") (pinfunction "2_2") (pintype "passive"))
      (node (ref "U11") (pin "17") (pinfunction "LED10_17") (pintype "output"))
    )
    (net (code "33") (name "/FAULT_E") (class "Default")
      (node (ref "IC12") (pin "20") (pinfunction "SWN_DIAG0_20") (pintype "bidirectional"))
      (node (ref "P8") (pin "18") (pinfunction "18_18") (pintype "passive"))
      (node (ref "R36") (pin "1") (pinfunction "1_1") (pintype "passive"))
    )
    (net (code "34") (name "/FAULT_H") (class "Default")
      (node (ref "IC15") (pin "20") (pinfunction "SWN_DIAG0_20") (pintype "bidirectional"))
      (node (ref "P8") (pin "8") (pinfunction "8_8") (pintype "passive"))
      (node (ref "R51") (pin "1") (pinfunction "1_1") (pintype "passive"))
    )
    (net (code "35") (name "/FAULT_X") (class "Default")
      (node (ref "IC1") (pin "20") (pinfunction "SWN_DIAG0_20") (pintype "bidirectional"))
      (node (ref "P8") (pin "10") (pinfunction "10_10") (pintype "passive"))
      (node (ref "R54") (pin "1") (pinfunction "1_1") (pintype "passive"))
    )
    (net (code "36") (name "/FAULT_Y") (class "Default")
      (node (ref "IC2") (pin "20") (pinfunction "SWN_DIAG0_20") (pintype "bidirectional"))
      (node (ref "P8") (pin "9") (pinfunction "9_9") (pintype "passive"))
      (node (ref "R24") (pin "1") (pinfunction "1_1") (pintype "passive"))
    )
    (net (code "37") (name "/FAULT_Z") (class "Default")
      (node (ref "IC5") (pin "20") (pinfunction "SWN_DIAG0_20") (pintype "bidirectional"))
      (node (ref "P9") (pin "24") (pinfunction "24_24") (pintype "passive"))
      (node (ref "R28") (pin "1") (pinfunction "1_1") (pintype "passive"))
    )
    (net (code "38") (name "/HEATER_E") (class "Default")
      (node (ref "Q3") (pin "4") (pinfunction "G_4") (pintype "passive"))
      (node (ref "R47") (pin "2") (pinfunction "2_2") (pintype "passive"))
      (node (ref "U11") (pin "11") (pinfunction "LED5_11") (pintype "output"))
    )
    (net (code "39") (name "/HEATER_H") (class "Default")
      (node (ref "Q2") (pin "4") (pinfunction "G_4") (pintype "passive"))
      (node (ref "R48") (pin "2") (pinfunction "2_2") (pintype "passive"))
      (node (ref "U11") (pin "9") (pinfunction "LED3_9") (pintype "output"))
    )
    (net (code "40") (name "/HEATER_HBP") (class "Default")
      (node (ref "Q1") (pin "4") (pinfunction "G_4") (pintype "passive"))
      (node (ref "R46") (pin "2") (pinfunction "2_2") (pintype "passive"))
      (node (ref "U11") (pin "10") (pinfunction "LED4_10") (pintype "output"))
    )
    (net (code "41") (name "/I2C2_SCL") (class "Default")
      (node (ref "P9") (pin "19") (pinfunction "19_19") (pintype "passive"))
      (node (ref "U11") (pin "26") (pinfunction "SCL_26") (pintype "input"))
      (node (ref "U18") (pin "6") (pinfunction "SCL_6") (pintype "input"))
    )
    (net (code "42") (name "/I2C2_SDA") (class "Default")
      (node (ref "P9") (pin "20") (pinfunction "20_20") (pintype "passive"))
      (node (ref "U11") (pin "27") (pinfunction "SDA_27") (pintype "bidirectional"))
      (node (ref "U18") (pin "5") (pinfunction "SDA_5") (pintype "bidirectional"))
    )
    (net (code "43") (name "/IREF_E_RAW") (class "Default")
      (node (ref "R60") (pin "2") (pinfunction "2_2") (pintype "passive"))
      (node (ref "U11") (pin "21") (pinfunction "LED14_21") (pintype "output"))
    )
    (net (code "44") (name "/IREF_H_RAW") (class "Default")
      (node (ref "R31") (pin "2") (pinfunction "2_2") (pintype "passive"))
      (node (ref "U11") (pin "22") (pinfunction "LED15_22") (pintype "output"))
    )
    (net (code "45") (name "/IREF_X_RAW") (class "Default")
      (node (ref "R41") (pin "2") (pinfunction "2_2") (pintype "passive"))
      (node (ref "U11") (pin "18") (pinfunction "LED11_18") (pintype "output"))
    )
    (net (code "46") (name "/IREF_Y_RAW") (class "Default")
      (node (ref "R37") (pin "2") (pinfunction "2_2") (pintype "passive"))
      (node (ref "U11") (pin "19") (pinfunction "LED12_19") (pintype "output"))
    )
    (net (code "47") (name "/IREF_Z_RAW") (class "Default")
      (node (ref "R58") (pin "2") (pinfunction "2_2") (pintype "passive"))
      (node (ref "U11") (pin "20") (pinfunction "LED13_20") (pintype "output"))
    )
    (net (code "48") (name "/SERVO_0") (class "Default")
      (node (ref "IC6") (pin "2") (pinfunction "I_2") (pintype "input"))
      (node (ref "P9") (pin "14") (pinfunction "14_14") (pintype "passive"))
    )
    (net (code "49") (name "/SERVO_0_EN") (class "Default")
      (node (ref "IC6") (pin "1") (pinfunction "OE_1") (pintype "input"))
      (node (ref "U2") (pin "15") (pinfunction "QA_15") (pintype "output"))
    )
    (net (code "50") (name "/SERVO_1") (class "Default")
      (node (ref "IC7") (pin "2") (pinfunction "I_2") (pintype "input"))
      (node (ref "P9") (pin "16") (pinfunction "16_16") (pintype "passive"))
    )
    (net (code "51") (name "/SERVO_1_EN") (class "Default")
      (node (ref "IC7") (pin "1") (pinfunction "OE_1") (pintype "input"))
      (node (ref "U3") (pin "15") (pinfunction "QA_15") (pintype "output"))
    )
    (net (code "52") (name "/SER_2") (class "Default")
      (node (ref "U1") (pin "9") (pinfunction "QH_2_9") (pintype "output"))
      (node (ref "U2") (pin "14") (pinfunction "SER_14") (pintype "input"))
    )
    (net (code "53") (name "/SER_3") (class "Default")
      (node (ref "U2") (pin "9") (pinfunction "QH_2_9") (pintype "output"))
      (node (ref "U3") (pin "14") (pinfunction "SER_14") (pintype "input"))
    )
    (net (code "54") (name "/SER_4") (class "Default")
      (node (ref "U3") (pin "9") (pinfunction "QH_2_9") (pintype "output"))
      (node (ref "U4") (pin "14") (pinfunction "SER_14") (pintype "input"))
    )
    (net (code "55") (name "/SER_5") (class "Default")
      (node (ref "U4") (pin "9") (pinfunction "QH_2_9") (pintype "output"))
      (node (ref "U5") (pin "14") (pinfunction "SER_14") (pintype "input"))
    )
    (net (code "56") (name "/SPI1_CS1") (class "Default")
      (node (ref "P9") (pin "42") (pinfunction "42_42") (pintype "passive"))
      (node (ref "U1") (pin "12") (pinfunction "RCLK_12") (pintype "input"))
      (node (ref "U2") (pin "12") (pinfunction "RCLK_12") (pintype "input"))
      (node (ref "U3") (pin "12") (pinfunction "RCLK_12") (pintype "input"))
      (node (ref "U4") (pin "12") (pinfunction "RCLK_12") (pintype "input"))
      (node (ref "U5") (pin "12") (pinfunction "RCLK_12") (pintype "input"))
    )
    (net (code "57") (name "/SPI1_MOSI") (class "Default")
      (node (ref "P9") (pin "30") (pinfunction "30_30") (pintype "passive"))
      (node (ref "U1") (pin "14") (pinfunction "SER_14") (pintype "input"))
    )
    (net (code "58") (name "/SPI1_SCLK") (class "Default")
      (node (ref "P9") (pin "31") (pinfunction "31_31") (pintype "passive"))
      (node (ref "U1") (pin "11") (pinfunction "SRCLK_11") (pintype "input"))
      (node (ref "U2") (pin "11") (pinfunction "SRCLK_11") (pintype "input"))
      (node (ref "U3") (pin "11") (pinfunction "SRCLK_11") (pintype "input"))
      (node (ref "U4") (pin "11") (pinfunction "SRCLK_11") (pintype "input"))
      (node (ref "U5") (pin "11") (pinfunction "SRCLK_11") (pintype "input"))
    )
    (net (code "59") (name "/STEP_E") (class "Default")
      (node (ref "IC12") (pin "6") (pinfunction "REFL_STEP_6") (pintype "bidirectional"))
      (node (ref "P9") (pin "12") (pinfunction "12_12") (pintype "passive"))
    )
    (net (code "60") (name "/STEP_H") (class "Default")
      (node (ref "IC15") (pin "6") (pinfunction "REFL_STEP_6") (pintype "bidirectional"))
      (node (ref "P8") (pin "11") (pinfunction "11_11") (pintype "passive"))
    )
    (net (code "61") (name "/STEP_X") (class "Default")
      (node (ref "IC1") (pin "6") (pinfunction "REFL_STEP_6") (pintype "bidirectional"))
      (node (ref "P8") (pin "17") (pinfunction "17_17") (pintype "passive"))
    )
    (net (code "62") (name "/STEP_Y") (class "Default")
      (node (ref "IC2") (pin "6") (pinfunction "REFL_STEP_6") (pintype "bidirectional"))
      (node (ref "P8") (pin "12") (pinfunction "12_12") (pintype "passive"))
    )
    (net (code "63") (name "/STEP_Z") (class "Default")
      (node (ref "IC5") (pin "6") (pinfunction "REFL_STEP_6") (pintype "bidirectional"))
      (node (ref "P8") (pin "13") (pinfunction "13_13") (pintype "passive"))
    )
    (net (code "64") (name "/SYS_5V") (class "Default")
      (node (ref "C17") (pin "1") (pinfunction "1_1") (pintype "passive"))
      (node (ref "P9") (pin "7") (pinfunction "7_7") (pintype "passive"))
      (node (ref "P9") (pin "8") (pinfunction "8_8") (pintype "passive"))
      (node (ref "U11") (pin "1") (pinfunction "A0_1") (pintype "input"))
      (node (ref "U11") (pin "2") (pinfunction "A1_2") (pintype "input"))
      (node (ref "U11") (pin "24") (pinfunction "A5_24") (pintype "input"))
      (node (ref "U11") (pin "28") (pinfunction "VDD_28") (pintype "power_in"))
      (node (ref "U11") (pin "3") (pinfunction "A2_3") (pintype "input"))
      (node (ref "U11") (pin "4") (pinfunction "A3_4") (pintype "input"))
      (node (ref "U11") (pin "5") (pinfunction "A4_5") (pintype "input"))
    )
    (net (code "65") (name "/TERM_EXT1") (class "Default")
      (node (ref "C26") (pin "1") (pinfunction "1_1") (pintype "passive"))
      (node (ref "P9") (pin "33") (pinfunction "33_33") (pintype "passive"))
      (node (ref "R38") (pin "2") (pinfunction "2_2") (pintype "passive"))
    )
    (net (code "66") (name "/TERM_EXT2") (class "Default")
      (node (ref "C46") (pin "1") (pinfunction "1_1") (pintype "passive"))
      (node (ref "P9") (pin "36") (pinfunction "36_36") (pintype "passive"))
      (node (ref "R40") (pin "2") (pinfunction "2_2") (pintype "passive"))
    )
    (net (code "67") (name "/TERM_HBP") (class "Default")
      (node (ref "C45") (pin "1") (pinfunction "1_1") (pintype "passive"))
      (node (ref "P9") (pin "35") (pinfunction "35_35") (pintype "passive"))
      (node (ref "R39") (pin "2") (pinfunction "2_2") (pintype "passive"))
    )
    (net (code "68") (name "/TRISTATE_STEPPERS") (class "Default")
      (node (ref "IC18") (pin "1") (pinfunction "OE_1") (pintype "input"))
      (node (ref "IC19") (pin "1") (pinfunction "OE_1") (pintype "input"))
      (node (ref "IC20") (pin "1") (pinfunction "OE_1") (pintype "input"))
      (node (ref "IC21") (pin "1") (pinfunction "OE_1") (pintype "input"))
      (node (ref "IC22") (pin "1") (pinfunction "OE_1") (pintype "input"))
      (node (ref "U5") (pin "15") (pinfunction "QA_15") (pintype "output"))
    )
    (net (code "69") (name "/VDD_12V") (class "Default")
      (node (ref "12V") (pin "TP") (pinfunction "TP_TP") (pintype "input"))
      (node (ref "C53") (pin "1") (pinfunction "1_1") (pintype "passive"))
      (node (ref "C81") (pin "1") (pinfunction "1_1") (pintype "passive"))
      (node (ref "L2") (pin "P$1") (pinfunction "P$1_P$1") (pintype "passive"))
      (node (ref "R11") (pin "2") (pinfunction "2_2") (pintype "passive"))
      (node (ref "R19") (pin "2") (pinfunction "2_2") (pintype "passive"))
      (node (ref "R20") (pin "2") (pinfunction "2_2") (pintype "passive"))
      (node (ref "R21") (pin "2") (pinfunction "2_2") (pintype "passive"))
      (node (ref "R25") (pin "2") (pinfunction "2_2") (pintype "passive"))
      (node (ref "R42") (pin "1") (pinfunction "1_1") (pintype "passive"))
      (node (ref "X12") (pin "4") (pinfunction "S_4") (pintype "passive"))
      (node (ref "X4") (pin "1") (pinfunction "S_1") (pintype "passive"))
      (node (ref "X5") (pin "1") (pinfunction "S_1") (pintype "passive"))
      (node (ref "X6") (pin "1") (pinfunction "S_1") (pintype "passive"))
      (node (ref "X9") (pin "1") (pinfunction "S_1") (pintype "passive"))
    )
    (net (code "70") (name "/VDD_ADC") (class "Default")
      (node (ref "P9") (pin "32") (pinfunction "32_32") (pintype "passive"))
      (node (ref "R13") (pin "2") (pinfunction "2_2") (pintype "passive"))
      (node (ref "R17") (pin "2") (pinfunction "2_2") (pintype "passive"))
      (node (ref "R18") (pin "2") (pinfunction "2_2") (pintype "passive"))
    )
    (net (code "71") (name "/VDD_IN") (class "Default")
      (node (ref "12..24V") (pin "TP") (pinfunction "TP_TP") (pintype "input"))
      (node (ref "C10") (pin "1") (pinfunction "1_1") (pintype "passive"))
      (node (ref "C19") (pin "1") (pinfunction "1_1") (pintype "passive"))
      (node (ref "C20") (pin "2") (pinfunction "2_2") (pintype "passive"))
      (node (ref "C22") (pin "2") (pinfunction "2_2") (pintype "passive"))
      (node (ref "C27") (pin "1") (pinfunction "1_1") (pintype "passive"))
      (node (ref "C28") (pin "2") (pinfunction "2_2") (pintype "passive"))
      (node (ref "C29") (pin "1") (pinfunction "1_1") (pintype "passive"))
      (node (ref "C31") (pin "1") (pinfunction "1_1") (pintype "passive"))
      (node (ref "C32") (pin "2") (pinfunction "2_2") (pintype "passive"))
      (node (ref "C35") (pin "2") (pinfunction "2_2") (pintype "passive"))
      (node (ref "C38") (pin "2") (pinfunction "2_2") (pintype "passive"))
      (node (ref "C4") (pin "1") (pinfunction "1_1") (pintype "passive"))
      (node (ref "C40") (pin "1") (pinfunction "1_1") (pintype "passive"))
      (node (ref "C43") (pin "1") (pinfunction "1_1") (pintype "passive"))
      (node (ref "C47") (pin "1") (pinfunction "1_1") (pintype "passive"))
      (node (ref "C52") (pin "1") (pinfunction "1_1") (pintype "passive"))
      (node (ref "C6") (pin "1") (pinfunction "1_1") (pintype "passive"))
      (node (ref "C64") (pin "2") (pinfunction "2_2") (pintype "passive"))
      (node (ref "C66") (pin "2") (pinfunction "2_2") (pintype "passive"))
      (node (ref "C67") (pin "2") (pinfunction "2_2") (pintype "passive"))
      (node (ref "C69") (pin "2") (pinfunction "2_2") (pintype "passive"))
      (node (ref "C8") (pin "1") (pinfunction "1_1") (pintype "passive"))
      (node (ref "C89") (pin "1") (pinfunction "1_1") (pintype "passive"))
      (node (ref "C90") (pin "1") (pinfunction "1_1") (pintype "passive"))
      (node (ref "C91") (pin "1") (pinfunction "1_1") (pintype "passive"))
      (node (ref "C92") (pin "1") (pinfunction "1_1") (pintype "passive"))
      (node (ref "C93") (pin "1") (pinfunction "1_1") (pintype "passive"))
      (node (ref "C94") (pin "+") (pinfunction "+_+") (pintype "passive"))
      (node (ref "C95") (pin "+") (pinfunction "+_+") (pintype "passive"))
      (node (ref "C96") (pin "+") (pinfunction "+_+") (pintype "passive"))
      (node (ref "C97") (pin "+") (pinfunction "+_+") (pintype "passive"))
      (node (ref "C98") (pin "+") (pinfunction "+_+") (pintype "passive"))
      (node (ref "D1") (pin "C") (pinfunction "C_C") (pintype "passive"))
      (node (ref "D2") (pin "C") (pinfunction "C_C") (pintype "passive"))
      (node (ref "D3") (pin "C") (pinfunction "C_C") (pintype "passive"))
      (node (ref "D5") (pin "C") (pinfunction "C_C") (pintype "passive"))
      (node (ref "F1") (pin "P$3") (pinfunction "2_P$3") (pintype "passive"))
      (node (ref "F1") (pin "P$4") (pinfunction "2_P$4") (pintype "passive"))
      (node (ref "IC1") (pin "16") (pinfunction "VS_16") (pintype "bidirectional"))
      (node (ref "IC1") (pin "30") (pinfunction "VSA_30") (pintype "bidirectional"))
      (node (ref "IC1") (pin "31") (pinfunction "VS_31") (pintype "bidirectional"))
      (node (ref "IC12") (pin "16") (pinfunction "VS_16") (pintype "bidirectional"))
      (node (ref "IC12") (pin "30") (pinfunction "VSA_30") (pintype "bidirectional"))
      (node (ref "IC12") (pin "31") (pinfunction "VS_31") (pintype "bidirectional"))
      (node (ref "IC15") (pin "16") (pinfunction "VS_16") (pintype "bidirectional"))
      (node (ref "IC15") (pin "30") (pinfunction "VSA_30") (pintype "bidirectional"))
      (node (ref "IC15") (pin "31") (pinfunction "VS_31") (pintype "bidirectional"))
      (node (ref "IC2") (pin "16") (pinfunction "VS_16") (pintype "bidirectional"))
      (node (ref "IC2") (pin "30") (pinfunction "VSA_30") (pintype "bidirectional"))
      (node (ref "IC2") (pin "31") (pinfunction "VS_31") (pintype "bidirectional"))
      (node (ref "IC5") (pin "16") (pinfunction "VS_16") (pintype "bidirectional"))
      (node (ref "IC5") (pin "30") (pinfunction "VSA_30") (pintype "bidirectional"))
      (node (ref "IC5") (pin "31") (pinfunction "VS_31") (pintype "bidirectional"))
      (node (ref "R14") (pin "2") (pinfunction "2_2") (pintype "passive"))
      (node (ref "R15") (pin "2") (pinfunction "2_2") (pintype "passive"))
      (node (ref "R16") (pin "2") (pinfunction "2_2") (pintype "passive"))
      (node (ref "R45") (pin "1") (pinfunction "1_1") (pintype "passive"))
      (node (ref "R55") (pin "2") (pinfunction "2_2") (pintype "passive"))
      (node (ref "R56") (pin "2") (pinfunction "2_2") (pintype "passive"))
      (node (ref "R57") (pin "2") (pinfunction "2_2") (pintype "passive"))
      (node (ref "U10") (pin "4") (pinfunction "VIN_4") (pintype "power_in"))
      (node (ref "U6") (pin "4") (pinfunction "VIN_4") (pintype "power_in"))
      (node (ref "X20") (pin "1") (pinfunction "1_1") (pintype "passive"))
      (node (ref "X20") (pin "2") (pinfunction "1_2") (pintype "passive"))
      (node (ref "X21") (pin "1") (pinfunction "1_1") (pintype "passive"))
      (node (ref "X3") (pin "1") (pinfunction "1_1") (pintype "passive"))
    )
    (net (code "72") (name "/VIN") (class "Default")
      (node (ref "F1") (pin "P$1") (pinfunction "1_P$1") (pintype "passive"))
      (node (ref "F1") (pin "P$2") (pinfunction "1_P$2") (pintype "passive"))
      (node (ref "LED8") (pin "A") (pinfunction "A_A") (pintype "passive"))
      (node (ref "X2") (pin "3") (pinfunction "1_3") (pintype "passive"))
      (node (ref "X2") (pin "4") (pinfunction "1_4") (pintype "passive"))
    )
    (net (code "73") (name "GND") (class "Default")
      (node (ref "C10") (pin "2") (pinfunction "2_2") (pintype "passive"))
      (node (ref "C12") (pin "2") (pinfunction "2_2") (pintype "passive"))
      (node (ref "C13") (pin "2") (pinfunction "2_2") (pintype "passive"))
      (node (ref "C14") (pin "2") (pinfunction "2_2") (pintype "passive"))
      (node (ref "C15") (pin "2") (pinfunction "2_2") (pintype "passive"))
      (node (ref "C17") (pin "2") (pinfunction "2_2") (pintype "passive"))
      (node (ref "C18") (pin "2") (pinfunction "2_2") (pintype "passive"))
      (node (ref "C19") (pin "2") (pinfunction "2_2") (pintype "passive"))
      (node (ref "C2") (pin "2") (pinfunction "2_2") (pintype "passive"))
      (node (ref "C20") (pin "1") (pinfunction "1_1") (pintype "passive"))
      (node (ref "C21") (pin "1") (pinfunction "1_1") (pintype "passive"))
      (node (ref "C23") (pin "2") (pinfunction "2_2") (pintype "passive"))
      (node (ref "C25") (pin "2") (pinfunction "2_2") (pintype "passive"))
      (node (ref "C26") (pin "2") (pinfunction "2_2") (pintype "passive"))
      (node (ref "C27") (pin "2") (pinfunction "2_2") (pintype "passive"))
      (node (ref "C28") (pin "1") (pinfunction "1_1") (pintype "passive"))
      (node (ref "C29") (pin "2") (pinfunction "2_2") (pintype "passive"))
      (node (ref "C30") (pin "2") (pinfunction "2_2") (pintype "passive"))
      (node (ref "C31") (pin "2") (pinfunction "2_2") (pintype "passive"))
      (node (ref "C32") (pin "1") (pinfunction "1_1") (pintype "passive"))
      (node (ref "C33") (pin "1") (pinfunction "1_1") (pintype "passive"))
      (node (ref "C36") (pin "2") (pinfunction "2_2") (pintype "passive"))
      (node (ref "C37") (pin "1") (pinfunction "1_1") (pintype "passive"))
      (node (ref "C4") (pin "2") (pinfunction "2_2") (pintype "passive"))
      (node (ref "C40") (pin "2") (pinfunction "2_2") (pintype "passive"))
      (node (ref "C41") (pin "2") (pinfunction "2_2") (pintype "passive"))
      (node (ref "C42") (pin "2") (pinfunction "2_2") (pintype "passive"))
      (node (ref "C43") (pin "2") (pinfunction "2_2") (pintype "passive"))
      (node (ref "C44") (pin "2") (pinfunction "2_2") (pintype "passive"))
      (node (ref "C45") (pin "2") (pinfunction "2_2") (pintype "passive"))
      (node (ref "C46") (pin "2") (pinfunction "2_2") (pintype "passive"))
      (node (ref "C47") (pin "2") (pinfunction "2_2") (pintype "passive"))
      (node (ref "C48") (pin "2") (pinfunction "2_2") (pintype "passive"))
      (node (ref "C49") (pin "2") (pinfunction "2_2") (pintype "passive"))
      (node (ref "C5") (pin "2") (pinfunction "2_2") (pintype "passive"))
      (node (ref "C52") (pin "2") (pinfunction "2_2") (pintype "passive"))
      (node (ref "C53") (pin "2") (pinfunction "2_2") (pintype "passive"))
      (node (ref "C54") (pin "2") (pinfunction "2_2") (pintype "passive"))
      (node (ref "C57") (pin "2") (pinfunction "2_2") (pintype "passive"))
      (node (ref "C58") (pin "2") (pinfunction "2_2") (pintype "passive"))
      (node (ref "C59") (pin "2") (pinfunction "2_2") (pintype "passive"))
      (node (ref "C6") (pin "2") (pinfunction "2_2") (pintype "passive"))
      (node (ref "C61") (pin "2") (pinfunction "2_2") (pintype "passive"))
      (node (ref "C62") (pin "2") (pinfunction "2_2") (pintype "passive"))
      (node (ref "C63") (pin "2") (pinfunction "2_2") (pintype "passive"))
      (node (ref "C64") (pin "1") (pinfunction "1_1") (pintype "passive"))
      (node (ref "C65") (pin "1") (pinfunction "1_1") (pintype "passive"))
      (node (ref "C67") (pin "1") (pinfunction "1_1") (pintype "passive"))
      (node (ref "C68") (pin "1") (pinfunction "1_1") (pintype "passive"))
      (node (ref "C70") (pin "2") (pinfunction "2_2") (pintype "passive"))
      (node (ref "C71") (pin "2") (pinfunction "2_2") (pintype "passive"))
      (node (ref "C72") (pin "2") (pinfunction "2_2") (pintype "passive"))
      (node (ref "C73") (pin "2") (pinfunction "2_2") (pintype "passive"))
      (node (ref "C74") (pin "2") (pinfunction "2_2") (pintype "passive"))
      (node (ref "C75") (pin "2") (pinfunction "2_2") (pintype "passive"))
      (node (ref "C76") (pin "2") (pinfunction "2_2") (pintype "passive"))
      (node (ref "C77") (pin "2") (pinfunction "2_2") (pintype "passive"))
      (node (ref "C78") (pin "2") (pinfunction "2_2") (pintype "passive"))
      (node (ref "C79") (pin "2") (pinfunction "2_2") (pintype "passive"))
      (node (ref "C8") (pin "2") (pinfunction "2_2") (pintype "passive"))
      (node (ref "C80") (pin "2") (pinfunction "2_2") (pintype "passive"))
      (node (ref "C81") (pin "2") (pinfunction "2_2") (pintype "passive"))
      (node (ref "C82") (pin "2") (pinfunction "2_2") (pintype "passive"))
      (node (ref "C83") (pin "2") (pinfunction "2_2") (pintype "passive"))
      (node (ref "C84") (pin "2") (pinfunction "2_2") (pintype "passive"))
      (node (ref "C85") (pin "2") (pinfunction "2_2") (pintype "passive"))
      (node (ref "C86") (pin "2") (pinfunction "2_2") (pintype "passive"))
      (node (ref "C87") (pin "2") (pinfunction "2_2") (pintype "passive"))
      (node (ref "C88") (pin "2") (pinfunction "2_2") (pintype "passive"))
      (node (ref "C89") (pin "2") (pinfunction "2_2") (pintype "passive"))
      (node (ref "C90") (pin "2") (pinfunction "2_2") (pintype "passive"))
      (node (ref "C91") (pin "2") (pinfunction "2_2") (pintype "passive"))
      (node (ref "C92") (pin "2") (pinfunction "2_2") (pintype "passive"))
      (node (ref "C93") (pin "2") (pinfunction "2_2") (pintype "passive"))
      (node (ref "C94") (pin "-") (pinfunction "-_-") (pintype "passive"))
      (node (ref "C95") (pin "-") (pinfunction "-_-") (pintype "passive"))
      (node (ref "C96") (pin "-") (pinfunction "-_-") (pintype "passive"))
      (node (ref "C97") (pin "-") (pinfunction "-_-") (pintype "passive"))
      (node (ref "C98") (pin "-") (pinfunction "-_-") (pintype "passive"))
      (node (ref "D4") (pin "A") (pinfunction "A_A") (pintype "passive"))
      (node (ref "D5") (pin "A") (pinfunction "A_A") (pintype "passive"))
      (node (ref "D6") (pin "A") (pinfunction "A_A") (pintype "passive"))
      (node (ref "IC1") (pin "1") (pinfunction "CLK_1") (pintype "bidirectional"))
      (node (ref "IC1") (pin "10") (pinfunction "SPI_MODE_10") (pintype "bidirectional"))
      (node (ref "IC1") (pin "11") (pinfunction "GND_11") (pintype "bidirectional"))
      (node (ref "IC1") (pin "12") (pinfunction "GND_12") (pintype "bidirectional"))
      (node (ref "IC1") (pin "24") (pinfunction "GNDA_24") (pintype "bidirectional"))
      (node (ref "IC1") (pin "35") (pinfunction "GND_35") (pintype "bidirectional"))
      (node (ref "IC1") (pin "36") (pinfunction "TST_MODE_36") (pintype "bidirectional"))
      (node (ref "IC1") (pin "TP") (pinfunction "GND_TP") (pintype "bidirectional"))
      (node (ref "IC10") (pin "3") (pinfunction "GND_3") (pintype "power_in"))
      (node (ref "IC11") (pin "3") (pinfunction "GND_3") (pintype "power_in"))
      (node (ref "IC12") (pin "1") (pinfunction "CLK_1") (pintype "bidirectional"))
      (node (ref "IC12") (pin "10") (pinfunction "SPI_MODE_10") (pintype "bidirectional"))
      (node (ref "IC12") (pin "11") (pinfunction "GND_11") (pintype "bidirectional"))
      (node (ref "IC12") (pin "12") (pinfunction "GND_12") (pintype "bidirectional"))
      (node (ref "IC12") (pin "24") (pinfunction "GNDA_24") (pintype "bidirectional"))
      (node (ref "IC12") (pin "35") (pinfunction "GND_35") (pintype "bidirectional"))
      (node (ref "IC12") (pin "36") (pinfunction "TST_MODE_36") (pintype "bidirectional"))
      (node (ref "IC12") (pin "TP") (pinfunction "GND_TP") (pintype "bidirectional"))
      (node (ref "IC13") (pin "3") (pinfunction "GND_3") (pintype "power_in"))
      (node (ref "IC14") (pin "3") (pinfunction "GND_3") (pintype "power_in"))
      (node (ref "IC15") (pin "1") (pinfunction "CLK_1") (pintype "bidirectional"))
      (node (ref "IC15") (pin "10") (pinfunction "SPI_MODE_10") (pintype "bidirectional"))
      (node (ref "IC15") (pin "11") (pinfunction "GND_11") (pintype "bidirectional"))
      (node (ref "IC15") (pin "12") (pinfunction "GND_12") (pintype "bidirectional"))
      (node (ref "IC15") (pin "24") (pinfunction "GNDA_24") (pintype "bidirectional"))
      (node (ref "IC15") (pin "35") (pinfunction "GND_35") (pintype "bidirectional"))
      (node (ref "IC15") (pin "36") (pinfunction "TST_MODE_36") (pintype "bidirectional"))
      (node (ref "IC15") (pin "TP") (pinfunction "GND_TP") (pintype "bidirectional"))
      (node (ref "IC16") (pin "3") (pinfunction "GND_3") (pintype "power_in"))
      (node (ref "IC17") (pin "3") (pinfunction "GND_3") (pintype "power_in"))
      (node (ref "IC18") (pin "3") (pinfunction "GND_3") (pintype "power_in"))
      (node (ref "IC19") (pin "3") (pinfunction "GND_3") (pintype "power_in"))
      (node (ref "IC2") (pin "1") (pinfunction "CLK_1") (pintype "bidirectional"))
      (node (ref "IC2") (pin "10") (pinfunction "SPI_MODE_10") (pintype "bidirectional"))
      (node (ref "IC2") (pin "11") (pinfunction "GND_11") (pintype "bidirectional"))
      (node (ref "IC2") (pin "12") (pinfunction "GND_12") (pintype "bidirectional"))
      (node (ref "IC2") (pin "24") (pinfunction "GNDA_24") (pintype "bidirectional"))
      (node (ref "IC2") (pin "35") (pinfunction "GND_35") (pintype "bidirectional"))
      (node (ref "IC2") (pin "36") (pinfunction "TST_MODE_36") (pintype "bidirectional"))
      (node (ref "IC2") (pin "TP") (pinfunction "GND_TP") (pintype "bidirectional"))
      (node (ref "IC20") (pin "3") (pinfunction "GND_3") (pintype "power_in"))
      (node (ref "IC21") (pin "3") (pinfunction "GND_3") (pintype "power_in"))
      (node (ref "IC22") (pin "3") (pinfunction "GND_3") (pintype "power_in"))
      (node (ref "IC3") (pin "3") (pinfunction "GND_3") (pintype "power_in"))
      (node (ref "IC4") (pin "3") (pinfunction "GND_3") (pintype "power_in"))
      (node (ref "IC5") (pin "1") (pinfunction "CLK_1") (pintype "bidirectional"))
      (node (ref "IC5") (pin "10") (pinfunction "SPI_MODE_10") (pintype "bidirectional"))
      (node (ref "IC5") (pin "11") (pinfunction "GND_11") (pintype "bidirectional"))
      (node (ref "IC5") (pin "12") (pinfunction "GND_12") (pintype "bidirectional"))
      (node (ref "IC5") (pin "24") (pinfunction "GNDA_24") (pintype "bidirectional"))
      (node (ref "IC5") (pin "35") (pinfunction "GND_35") (pintype "bidirectional"))
      (node (ref "IC5") (pin "36") (pinfunction "TST_MODE_36") (pintype "bidirectional"))
      (node (ref "IC5") (pin "TP") (pinfunction "GND_TP") (pintype "bidirectional"))
      (node (ref "IC6") (pin "3") (pinfunction "GND_3") (pintype "power_in"))
      (node (ref "IC7") (pin "3") (pinfunction "GND_3") (pintype "power_in"))
      (node (ref "IC8") (pin "3") (pinfunction "GND_3") (pintype "power_in"))
      (node (ref "IC9") (pin "3") (pinfunction "GND_3") (pintype "power_in"))
      (node (ref "LED4") (pin "C") (pinfunction "C_C") (pintype "passive"))
      (node (ref "P8") (pin "1") (pinfunction "1_1") (pintype "passive"))
      (node (ref "P8") (pin "2") (pinfunction "2_2") (pintype "passive"))
      (node (ref "P9") (pin "1") (pinfunction "1_1") (pintype "passive"))
      (node (ref "P9") (pin "2") (pinfunction "2_2") (pintype "passive"))
      (node (ref "P9") (pin "43") (pinfunction "43_43") (pintype "passive"))
      (node (ref "P9") (pin "44") (pinfunction "44_44") (pintype "passive"))
      (node (ref "P9") (pin "45") (pinfunction "45_45") (pintype "passive"))
      (node (ref "P9") (pin "46") (pinfunction "46_46") (pintype "passive"))
      (node (ref "Q1") (pin "1") (pinfunction "S_1") (pintype "passive"))
      (node (ref "Q1") (pin "2") (pinfunction "S_2") (pintype "passive"))
      (node (ref "Q1") (pin "3") (pinfunction "S_3") (pintype "passive"))
      (node (ref "Q2") (pin "1") (pinfunction "S_1") (pintype "passive"))
      (node (ref "Q2") (pin "2") (pinfunction "S_2") (pintype "passive"))
      (node (ref "Q2") (pin "3") (pinfunction "S_3") (pintype "passive"))
      (node (ref "Q3") (pin "1") (pinfunction "S_1") (pintype "passive"))
      (node (ref "Q3") (pin "2") (pinfunction "S_2") (pintype "passive"))
      (node (ref "Q3") (pin "3") (pinfunction "S_3") (pintype "passive"))
      (node (ref "Q4") (pin "2") (pinfunction "E_2") (pintype "passive"))
      (node (ref "Q5") (pin "2") (pinfunction "E_2") (pintype "passive"))
      (node (ref "Q6") (pin "2") (pinfunction "E_2") (pintype "passive"))
      (node (ref "Q7") (pin "2") (pinfunction "E_2") (pintype "passive"))
      (node (ref "R1") (pin "1") (pinfunction "1_1") (pintype "passive"))
      (node (ref "R10") (pin "1") (pinfunction "1_1") (pintype "passive"))
      (node (ref "R2") (pin "1") (pinfunction "1_1") (pintype "passive"))
      (node (ref "R22") (pin "2") (pinfunction "2_2") (pintype "passive"))
      (node (ref "R26") (pin "2") (pinfunction "2_2") (pintype "passive"))
      (node (ref "R29") (pin "1") (pinfunction "1_1") (pintype "passive"))
      (node (ref "R3") (pin "1") (pinfunction "1_1") (pintype "passive"))
      (node (ref "R30") (pin "1") (pinfunction "1_1") (pintype "passive"))
      (node (ref "R32") (pin "1") (pinfunction "1_1") (pintype "passive"))
      (node (ref "R33") (pin "1") (pinfunction "1_1") (pintype "passive"))
      (node (ref "R34") (pin "1") (pinfunction "1_1") (pintype "passive"))
      (node (ref "R4") (pin "1") (pinfunction "1_1") (pintype "passive"))
      (node (ref "R43") (pin "2") (pinfunction "2_2") (pintype "passive"))
      (node (ref "R44") (pin "2") (pinfunction "2_2") (pintype "passive"))
      (node (ref "R46") (pin "1") (pinfunction "1_1") (pintype "passive"))
      (node (ref "R47") (pin "1") (pinfunction "1_1") (pintype "passive"))
      (node (ref "R48") (pin "1") (pinfunction "1_1") (pintype "passive"))
      (node (ref "R5") (pin "1") (pinfunction "1_1") (pintype "passive"))
      (node (ref "R7") (pin "1") (pinfunction "1_1") (pintype "passive"))
      (node (ref "R8") (pin "1") (pinfunction "1_1") (pintype "passive"))
      (node (ref "R9") (pin "1") (pinfunction "1_1") (pintype "passive"))
      (node (ref "U1") (pin "13") (pinfunction "~{OE}_13") (pintype "input"))
      (node (ref "U1") (pin "8") (pinfunction "GND_8") (pintype "passive"))
      (node (ref "U10") (pin "6") (pinfunction "GND_6") (pintype "power_in"))
      (node (ref "U10") (pin "EP") (pinfunction "EP_EP") (pintype "power_in"))
      (node (ref "U11") (pin "14") (pinfunction "VSS_14") (pintype "passive"))
      (node (ref "U18") (pin "1") (pinfunction "A0_1") (pintype "input"))
      (node (ref "U18") (pin "2") (pinfunction "A1_2") (pintype "input"))
      (node (ref "U18") (pin "4") (pinfunction "GND_4") (pintype "power_in"))
      (node (ref "U19") (pin "8") (pinfunction "VSS_8") (pintype "power_in"))
      (node (ref "U2") (pin "13") (pinfunction "~{OE}_13") (pintype "input"))
      (node (ref "U2") (pin "8") (pinfunction "GND_8") (pintype "passive"))
      (node (ref "U3") (pin "13") (pinfunction "~{OE}_13") (pintype "input"))
      (node (ref "U3") (pin "8") (pinfunction "GND_8") (pintype "passive"))
      (node (ref "U4") (pin "13") (pinfunction "~{OE}_13") (pintype "input"))
      (node (ref "U4") (pin "8") (pinfunction "GND_8") (pintype "passive"))
      (node (ref "U5") (pin "13") (pinfunction "~{OE}_13") (pintype "input"))
      (node (ref "U5") (pin "8") (pinfunction "GND_8") (pintype "passive"))
      (node (ref "U6") (pin "6") (pinfunction "GND_6") (pintype "power_in"))
      (node (ref "U6") (pin "EP") (pinfunction "EP_EP") (pintype "power_in"))
      (node (ref "X1") (pin "2") (pinfunction "S_2") (pintype "passive"))
      (node (ref "X10") (pin "2") (pinfunction "S_2") (pintype "passive"))
      (node (ref "X11") (pin "1") (pinfunction "S_1") (pintype "passive"))
      (node (ref "X12") (pin "2") (pinfunction "S_2") (pintype "passive"))
      (node (ref "X13") (pin "2") (pinfunction "S_2") (pintype "passive"))
      (node (ref "X19") (pin "2") (pinfunction "S_2") (pintype "passive"))
      (node (ref "X2") (pin "1") (pinfunction "1_1") (pintype "passive"))
      (node (ref "X2") (pin "2") (pinfunction "1_2") (pintype "passive"))
      (node (ref "X22") (pin "2") (pinfunction "S_2") (pintype "passive"))
      (node (ref "X23") (pin "3") (pinfunction "S_3") (pintype "passive"))
      (node (ref "X7") (pin "1") (pinfunction "S_1") (pintype "passive"))
      (node (ref "X8") (pin "1") (pinfunction "S_1") (pintype "passive"))
    )
    (net (code "74") (name "Net-(C51-Pad2)") (class "Default")
      (node (ref "C51") (pin "2") (pinfunction "2_2") (pintype "passive"))
      (node (ref "R26") (pin "1") (pinfunction "1_1") (pintype "passive"))
    )
    (net (code "75") (name "Net-(C56-Pad2)") (class "Default")
      (node (ref "C56") (pin "2") (pinfunction "2_2") (pintype "passive"))
      (node (ref "R44") (pin "1") (pinfunction "1_1") (pintype "passive"))
    )
    (net (code "76") (name "Net-(C75-Pad1)") (class "Default")
      (node (ref "C75") (pin "1") (pinfunction "1_1") (pintype "passive"))
      (node (ref "R31") (pin "1") (pinfunction "1_1") (pintype "passive"))
      (node (ref "R50") (pin "2") (pinfunction "2_2") (pintype "passive"))
    )
    (net (code "77") (name "Net-(C76-Pad1)") (class "Default")
      (node (ref "C76") (pin "1") (pinfunction "1_1") (pintype "passive"))
      (node (ref "R37") (pin "1") (pinfunction "1_1") (pintype "passive"))
      (node (ref "R6") (pin "2") (pinfunction "2_2") (pintype "passive"))
    )
    (net (code "78") (name "Net-(C77-Pad1)") (class "Default")
      (node (ref "C77") (pin "1") (pinfunction "1_1") (pintype "passive"))
      (node (ref "R41") (pin "1") (pinfunction "1_1") (pintype "passive"))
      (node (ref "R49") (pin "2") (pinfunction "2_2") (pintype "passive"))
    )
    (net (code "79") (name "Net-(C78-Pad1)") (class "Default")
      (node (ref "C78") (pin "1") (pinfunction "1_1") (pintype "passive"))
      (node (ref "R27") (pin "2") (pinfunction "2_2") (pintype "passive"))
      (node (ref "R58") (pin "1") (pinfunction "1_1") (pintype "passive"))
    )
    (net (code "80") (name "Net-(C79-Pad1)") (class "Default")
      (node (ref "C79") (pin "1") (pinfunction "1_1") (pintype "passive"))
      (node (ref "R35") (pin "2") (pinfunction "2_2") (pintype "passive"))
      (node (ref "R60") (pin "1") (pinfunction "1_1") (pintype "passive"))
    )
    (net (code "81") (name "Net-(IC1-5VOUT)") (class "Default")
      (node (ref "C21") (pin "2") (pinfunction "2_2") (pintype "passive"))
      (node (ref "IC1") (pin "25") (pinfunction "5VOUT_25") (pintype "bidirectional"))
      (node (ref "R53") (pin "1") (pinfunction "1_1") (pintype "passive"))
    )
    (net (code "82") (name "Net-(IC1-AIN_IREF)") (class "Default")
      (node (ref "C12") (pin "1") (pinfunction "1_1") (pintype "passive"))
      (node (ref "IC1") (pin "23") (pinfunction "AIN_IREF_23") (pintype "bidirectional"))
      (node (ref "R49") (pin "1") (pinfunction "1_1") (pintype "passive"))
    )
    (net (code "83") (name "Net-(IC1-BRA)") (class "Default")
      (node (ref "IC1") (pin "33") (pinfunction "BRA_33") (pintype "bidirectional"))
      (node (ref "R2") (pin "2") (pinfunction "2_2") (pintype "passive"))
    )
    (net (code "84") (name "Net-(IC1-BRB)") (class "Default")
      (node (ref "IC1") (pin "14") (pinfunction "BRB_14") (pintype "bidirectional"))
      (node (ref "R1") (pin "2") (pinfunction "2_2") (pintype "passive"))
    )
    (net (code "85") (name "Net-(IC1-CPI)") (class "Default")
      (node (ref "C1") (pin "1") (pinfunction "1_1") (pintype "passive"))
      (node (ref "IC1") (pin "28") (pinfunction "CPI_28") (pintype "bidirectional"))
    )
    (net (code "86") (name "Net-(IC1-CPO)") (class "Default")
      (node (ref "C1") (pin "2") (pinfunction "2_2") (pintype "passive"))
      (node (ref "IC1") (pin "27") (pinfunction "CPO_27") (pintype "bidirectional"))
    )
    (net (code "87") (name "Net-(IC1-ENCA_DCIN_CFG5)") (class "Default")
      (node (ref "IC1") (pin "19") (pinfunction "ENCA_DCIN_CFG5_19") (pintype "bidirectional"))
      (node (ref "U1") (pin "1") (pinfunction "QB_1") (pintype "output"))
    )
    (net (code "88") (name "Net-(IC1-ENCB_DCEN_CFG4)") (class "Default")
      (node (ref "IC1") (pin "18") (pinfunction "ENCB_DCEN_CFG4_18") (pintype "bidirectional"))
      (node (ref "U1") (pin "2") (pinfunction "QC_2") (pintype "output"))
    )
    (net (code "89") (name "Net-(IC1-OA1)") (class "Default")
      (node (ref "IC1") (pin "34") (pinfunction "OA1_34") (pintype "bidirectional"))
      (node (ref "X14") (pin "2") (pinfunction "S_2") (pintype "passive"))
    )
    (net (code "90") (name "Net-(IC1-OA2)") (class "Default")
      (node (ref "IC1") (pin "32") (pinfunction "OA2_32") (pintype "bidirectional"))
      (node (ref "X14") (pin "1") (pinfunction "S_1") (pintype "passive"))
    )
    (net (code "91") (name "Net-(IC1-OB1)") (class "Default")
      (node (ref "IC1") (pin "13") (pinfunction "OB1_13") (pintype "bidirectional"))
      (node (ref "X14") (pin "3") (pinfunction "S_3") (pintype "passive"))
    )
    (net (code "92") (name "Net-(IC1-OB2)") (class "Default")
      (node (ref "IC1") (pin "15") (pinfunction "OB2_15") (pintype "bidirectional"))
      (node (ref "X14") (pin "4") (pinfunction "S_4") (pintype "passive"))
    )
    (net (code "93") (name "Net-(IC1-SCK_CFG2)") (class "Default")
      (node (ref "IC1") (pin "3") (pinfunction "SCK_CFG2_3") (pintype "bidirectional"))
      (node (ref "IC3") (pin "4") (pinfunction "O_4") (pintype "output"))
    )
    (net (code "94") (name "Net-(IC1-SDI_NAI_CFG1)") (class "Default")
      (node (ref "IC1") (pin "4") (pinfunction "SDI_NAI_CFG1_4") (pintype "bidirectional"))
      (node (ref "IC4") (pin "4") (pinfunction "O_4") (pintype "output"))
    )
    (net (code "95") (name "Net-(IC1-SDO_NAO_CFG0)") (class "Default")
      (node (ref "IC1") (pin "5") (pinfunction "SDO_NAO_CFG0_5") (pintype "bidirectional"))
      (node (ref "U1") (pin "3") (pinfunction "QD_3") (pintype "output"))
    )
    (net (code "96") (name "Net-(IC1-VCC)") (class "Default")
      (node (ref "C71") (pin "1") (pinfunction "1_1") (pintype "passive"))
      (node (ref "IC1") (pin "26") (pinfunction "VCC_26") (pintype "bidirectional"))
      (node (ref "R53") (pin "2") (pinfunction "2_2") (pintype "passive"))
    )
    (net (code "97") (name "Net-(IC1-VCP)") (class "Default")
      (node (ref "C22") (pin "1") (pinfunction "1_1") (pintype "passive"))
      (node (ref "IC1") (pin "29") (pinfunction "VCP_29") (pintype "bidirectional"))
    )
    (net (code "98") (name "Net-(IC2-5VOUT)") (class "Default")
      (node (ref "C33") (pin "2") (pinfunction "2_2") (pintype "passive"))
      (node (ref "IC2") (pin "25") (pinfunction "5VOUT_25") (pintype "bidirectional"))
      (node (ref "R59") (pin "1") (pinfunction "1_1") (pintype "passive"))
    )
    (net (code "99") (name "Net-(IC2-AIN_IREF)") (class "Default")
      (node (ref "C18") (pin "1") (pinfunction "1_1") (pintype "passive"))
      (node (ref "IC2") (pin "23") (pinfunction "AIN_IREF_23") (pintype "bidirectional"))
      (node (ref "R6") (pin "1") (pinfunction "1_1") (pintype "passive"))
    )
    (net (code "100") (name "Net-(IC2-BRA)") (class "Default")
      (node (ref "IC2") (pin "33") (pinfunction "BRA_33") (pintype "bidirectional"))
      (node (ref "R4") (pin "2") (pinfunction "2_2") (pintype "passive"))
    )
    (net (code "101") (name "Net-(IC2-BRB)") (class "Default")
      (node (ref "IC2") (pin "14") (pinfunction "BRB_14") (pintype "bidirectional"))
      (node (ref "R3") (pin "2") (pinfunction "2_2") (pintype "passive"))
    )
    (net (code "102") (name "Net-(IC2-CPI)") (class "Default")
      (node (ref "C3") (pin "1") (pinfunction "1_1") (pintype "passive"))
      (node (ref "IC2") (pin "28") (pinfunction "CPI_28") (pintype "bidirectional"))
    )
    (net (code "103") (name "Net-(IC2-CPO)") (class "Default")
      (node (ref "C3") (pin "2") (pinfunction "2_2") (pintype "passive"))
      (node (ref "IC2") (pin "27") (pinfunction "CPO_27") (pintype "bidirectional"))
    )
    (net (code "104") (name "Net-(IC2-ENCA_DCIN_CFG5)") (class "Default")
      (node (ref "IC2") (pin "19") (pinfunction "ENCA_DCIN_CFG5_19") (pintype "bidirectional"))
      (node (ref "U2") (pin "1") (pinfunction "QB_1") (pintype "output"))
    )
    (net (code "105") (name "Net-(IC2-ENCB_DCEN_CFG4)") (class "Default")
      (node (ref "IC2") (pin "18") (pinfunction "ENCB_DCEN_CFG4_18") (pintype "bidirectional"))
      (node (ref "U2") (pin "2") (pinfunction "QC_2") (pintype "output"))
    )
    (net (code "106") (name "Net-(IC2-OA1)") (class "Default")
      (node (ref "IC2") (pin "34") (pinfunction "OA1_34") (pintype "bidirectional"))
      (node (ref "X15") (pin "2") (pinfunction "S_2") (pintype "passive"))
    )
    (net (code "107") (name "Net-(IC2-OA2)") (class "Default")
      (node (ref "IC2") (pin "32") (pinfunction "OA2_32") (pintype "bidirectional"))
      (node (ref "X15") (pin "1") (pinfunction "S_1") (pintype "passive"))
    )
    (net (code "108") (name "Net-(IC2-OB1)") (class "Default")
      (node (ref "IC2") (pin "13") (pinfunction "OB1_13") (pintype "bidirectional"))
      (node (ref "X15") (pin "3") (pinfunction "S_3") (pintype "passive"))
    )
    (net (code "109") (name "Net-(IC2-OB2)") (class "Default")
      (node (ref "IC2") (pin "15") (pinfunction "OB2_15") (pintype "bidirectional"))
      (node (ref "X15") (pin "4") (pinfunction "S_4") (pintype "passive"))
    )
    (net (code "110") (name "Net-(IC2-SCK_CFG2)") (class "Default")
      (node (ref "IC2") (pin "3") (pinfunction "SCK_CFG2_3") (pintype "bidirectional"))
      (node (ref "IC8") (pin "4") (pinfunction "O_4") (pintype "output"))
    )
    (net (code "111") (name "Net-(IC2-SDI_NAI_CFG1)") (class "Default")
      (node (ref "IC2") (pin "4") (pinfunction "SDI_NAI_CFG1_4") (pintype "bidirectional"))
      (node (ref "IC9") (pin "4") (pinfunction "O_4") (pintype "output"))
    )
    (net (code "112") (name "Net-(IC2-SDO_NAO_CFG0)") (class "Default")
      (node (ref "IC2") (pin "5") (pinfunction "SDO_NAO_CFG0_5") (pintype "bidirectional"))
      (node (ref "U2") (pin "3") (pinfunction "QD_3") (pintype "output"))
    )
    (net (code "113") (name "Net-(IC2-VCC)") (class "Default")
      (node (ref "C72") (pin "1") (pinfunction "1_1") (pintype "passive"))
      (node (ref "IC2") (pin "26") (pinfunction "VCC_26") (pintype "bidirectional"))
      (node (ref "R59") (pin "2") (pinfunction "2_2") (pintype "passive"))
    )
    (net (code "114") (name "Net-(IC2-VCP)") (class "Default")
      (node (ref "C35") (pin "1") (pinfunction "1_1") (pintype "passive"))
      (node (ref "IC2") (pin "29") (pinfunction "VCP_29") (pintype "bidirectional"))
    )
    (net (code "115") (name "Net-(IC3A-I)") (class "Default")
      (node (ref "IC3") (pin "2") (pinfunction "I_2") (pintype "input"))
      (node (ref "U1") (pin "4") (pinfunction "QE_4") (pintype "output"))
    )
    (net (code "116") (name "Net-(IC3A-OE)") (class "Default")
      (node (ref "IC3") (pin "1") (pinfunction "OE_1") (pintype "input"))
      (node (ref "U1") (pin "5") (pinfunction "QF_5") (pintype "output"))
    )
    (net (code "117") (name "Net-(IC4A-I)") (class "Default")
      (node (ref "IC4") (pin "2") (pinfunction "I_2") (pintype "input"))
      (node (ref "U1") (pin "6") (pinfunction "QG_6") (pintype "output"))
    )
    (net (code "118") (name "Net-(IC4A-OE)") (class "Default")
      (node (ref "IC4") (pin "1") (pinfunction "OE_1") (pintype "input"))
      (node (ref "U1") (pin "7") (pinfunction "QH_7") (pintype "output"))
    )
    (net (code "119") (name "Net-(IC5-5VOUT)") (class "Default")
      (node (ref "C37") (pin "2") (pinfunction "2_2") (pintype "passive"))
      (node (ref "IC5") (pin "25") (pinfunction "5VOUT_25") (pintype "bidirectional"))
      (node (ref "R70") (pin "1") (pinfunction "1_1") (pintype "passive"))
    )
    (net (code "120") (name "Net-(IC5-AIN_IREF)") (class "Default")
      (node (ref "C25") (pin "1") (pinfunction "1_1") (pintype "passive"))
      (node (ref "IC5") (pin "23") (pinfunction "AIN_IREF_23") (pintype "bidirectional"))
      (node (ref "R27") (pin "1") (pinfunction "1_1") (pintype "passive"))
    )
    (net (code "121") (name "Net-(IC5-BRA)") (class "Default")
      (node (ref "IC5") (pin "33") (pinfunction "BRA_33") (pintype "bidirectional"))
      (node (ref "R8") (pin "2") (pinfunction "2_2") (pintype "passive"))
    )
    (net (code "122") (name "Net-(IC5-BRB)") (class "Default")
      (node (ref "IC5") (pin "14") (pinfunction "BRB_14") (pintype "bidirectional"))
      (node (ref "R7") (pin "2") (pinfunction "2_2") (pintype "passive"))
    )
    (net (code "123") (name "Net-(IC5-CPI)") (class "Default")
      (node (ref "C7") (pin "1") (pinfunction "1_1") (pintype "passive"))
      (node (ref "IC5") (pin "28") (pinfunction "CPI_28") (pintype "bidirectional"))
    )
    (net (code "124") (name "Net-(IC5-CPO)") (class "Default")
      (node (ref "C7") (pin "2") (pinfunction "2_2") (pintype "passive"))
      (node (ref "IC5") (pin "27") (pinfunction "CPO_27") (pintype "bidirectional"))
    )
    (net (code "125") (name "Net-(IC5-ENCA_DCIN_CFG5)") (class "Default")
      (node (ref "IC5") (pin "19") (pinfunction "ENCA_DCIN_CFG5_19") (pintype "bidirectional"))
      (node (ref "U3") (pin "1") (pinfunction "QB_1") (pintype "output"))
    )
    (net (code "126") (name "Net-(IC5-ENCB_DCEN_CFG4)") (class "Default")
      (node (ref "IC5") (pin "18") (pinfunction "ENCB_DCEN_CFG4_18") (pintype "bidirectional"))
      (node (ref "U3") (pin "2") (pinfunction "QC_2") (pintype "output"))
    )
    (net (code "127") (name "Net-(IC5-OA1)") (class "Default")
      (node (ref "IC5") (pin "34") (pinfunction "OA1_34") (pintype "bidirectional"))
      (node (ref "X16") (pin "2") (pinfunction "S_2") (pintype "passive"))
    )
    (net (code "128") (name "Net-(IC5-OA2)") (class "Default")
      (node (ref "IC5") (pin "32") (pinfunction "OA2_32") (pintype "bidirectional"))
      (node (ref "X16") (pin "1") (pinfunction "S_1") (pintype "passive"))
    )
    (net (code "129") (name "Net-(IC5-OB1)") (class "Default")
      (node (ref "IC5") (pin "13") (pinfunction "OB1_13") (pintype "bidirectional"))
      (node (ref "X16") (pin "3") (pinfunction "S_3") (pintype "passive"))
    )
    (net (code "130") (name "Net-(IC5-OB2)") (class "Default")
      (node (ref "IC5") (pin "15") (pinfunction "OB2_15") (pintype "bidirectional"))
      (node (ref "X16") (pin "4") (pinfunction "S_4") (pintype "passive"))
    )
    (net (code "131") (name "Net-(IC5-SDO_NAO_CFG0)") (class "Default")
      (node (ref "IC5") (pin "5") (pinfunction "SDO_NAO_CFG0_5") (pintype "bidirectional"))
      (node (ref "U3") (pin "3") (pinfunction "QD_3") (pintype "output"))
    )
    (net (code "132") (name "Net-(IC5-VCC)") (class "Default")
      (node (ref "C73") (pin "1") (pinfunction "1_1") (pintype "passive"))
      (node (ref "IC5") (pin "26") (pinfunction "VCC_26") (pintype "bidirectional"))
      (node (ref "R70") (pin "2") (pinfunction "2_2") (pintype "passive"))
    )
    (net (code "133") (name "Net-(IC5-VCP)") (class "Default")
      (node (ref "C38") (pin "1") (pinfunction "1_1") (pintype "passive"))
      (node (ref "IC5") (pin "29") (pinfunction "VCP_29") (pintype "bidirectional"))
    )
    (net (code "134") (name "Net-(IC8A-I)") (class "Default")
      (node (ref "IC8") (pin "2") (pinfunction "I_2") (pintype "input"))
      (node (ref "U2") (pin "4") (pinfunction "QE_4") (pintype "output"))
    )
    (net (code "135") (name "Net-(IC8A-OE)") (class "Default")
      (node (ref "IC8") (pin "1") (pinfunction "OE_1") (pintype "input"))
      (node (ref "U2") (pin "5") (pinfunction "QF_5") (pintype "output"))
    )
    (net (code "136") (name "Net-(IC9A-I)") (class "Default")
      (node (ref "IC9") (pin "2") (pinfunction "I_2") (pintype "input"))
      (node (ref "U2") (pin "6") (pinfunction "QG_6") (pintype "output"))
    )
    (net (code "137") (name "Net-(IC9A-OE)") (class "Default")
      (node (ref "IC9") (pin "1") (pinfunction "OE_1") (pintype "input"))
      (node (ref "U2") (pin "7") (pinfunction "QH_7") (pintype "output"))
    )
    (net (code "138") (name "Net-(IC10A-I)") (class "Default")
      (node (ref "IC10") (pin "2") (pinfunction "I_2") (pintype "input"))
      (node (ref "U3") (pin "4") (pinfunction "QE_4") (pintype "output"))
    )
    (net (code "139") (name "Net-(IC10A-O)") (class "Default")
      (node (ref "IC10") (pin "4") (pinfunction "O_4") (pintype "output"))
      (node (ref "IC5") (pin "3") (pinfunction "SCK_CFG2_3") (pintype "bidirectional"))
    )
    (net (code "140") (name "Net-(IC10A-OE)") (class "Default")
      (node (ref "IC10") (pin "1") (pinfunction "OE_1") (pintype "input"))
      (node (ref "U3") (pin "5") (pinfunction "QF_5") (pintype "output"))
    )
    (net (code "141") (name "Net-(IC11A-I)") (class "Default")
      (node (ref "IC11") (pin "2") (pinfunction "I_2") (pintype "input"))
      (node (ref "U3") (pin "6") (pinfunction "QG_6") (pintype "output"))
    )
    (net (code "142") (name "Net-(IC11A-O)") (class "Default")
      (node (ref "IC11") (pin "4") (pinfunction "O_4") (pintype "output"))
      (node (ref "IC5") (pin "4") (pinfunction "SDI_NAI_CFG1_4") (pintype "bidirectional"))
    )
    (net (code "143") (name "Net-(IC11A-OE)") (class "Default")
      (node (ref "IC11") (pin "1") (pinfunction "OE_1") (pintype "input"))
      (node (ref "U3") (pin "7") (pinfunction "QH_7") (pintype "output"))
    )
    (net (code "144") (name "Net-(IC12-5VOUT)") (class "Default")
      (node (ref "C65") (pin "2") (pinfunction "2_2") (pintype "passive"))
      (node (ref "IC12") (pin "25") (pinfunction "5VOUT_25") (pintype "bidirectional"))
      (node (ref "R71") (pin "1") (pinfunction "1_1") (pintype "passive"))
    )
    (net (code "145") (name "Net-(IC12-AIN_IREF)") (class "Default")
      (node (ref "C62") (pin "1") (pinfunction "1_1") (pintype "passive"))
      (node (ref "IC12") (pin "23") (pinfunction "AIN_IREF_23") (pintype "bidirectional"))
      (node (ref "R35") (pin "1") (pinfunction "1_1") (pintype "passive"))
    )
    (net (code "146") (name "Net-(IC12-BRA)") (class "Default")
      (node (ref "IC12") (pin "33") (pinfunction "BRA_33") (pintype "bidirectional"))
      (node (ref "R30") (pin "2") (pinfunction "2_2") (pintype "passive"))
    )
    (net (code "147") (name "Net-(IC12-BRB)") (class "Default")
      (node (ref "IC12") (pin "14") (pinfunction "BRB_14") (pintype "bidirectional"))
      (node (ref "R29") (pin "2") (pinfunction "2_2") (pintype "passive"))
    )
    (net (code "148") (name "Net-(IC12-CPI)") (class "Default")
      (node (ref "C39") (pin "1") (pinfunction "1_1") (pintype "passive"))
      (node (ref "IC12") (pin "28") (pinfunction "CPI_28") (pintype "bidirectional"))
    )
    (net (code "149") (name "Net-(IC12-CPO)") (class "Default")
      (node (ref "C39") (pin "2") (pinfunction "2_2") (pintype "passive"))
      (node (ref "IC12") (pin "27") (pinfunction "CPO_27") (pintype "bidirectional"))
    )
    (net (code "150") (name "Net-(IC12-ENCA_DCIN_CFG5)") (class "Default")
      (node (ref "IC12") (pin "19") (pinfunction "ENCA_DCIN_CFG5_19") (pintype "bidirectional"))
      (node (ref "U4") (pin "1") (pinfunction "QB_1") (pintype "output"))
    )
    (net (code "151") (name "Net-(IC12-ENCB_DCEN_CFG4)") (class "Default")
      (node (ref "IC12") (pin "18") (pinfunction "ENCB_DCEN_CFG4_18") (pintype "bidirectional"))
      (node (ref "U4") (pin "2") (pinfunction "QC_2") (pintype "output"))
    )
    (net (code "152") (name "Net-(IC12-OA1)") (class "Default")
      (node (ref "IC12") (pin "34") (pinfunction "OA1_34") (pintype "bidirectional"))
      (node (ref "X17") (pin "2") (pinfunction "S_2") (pintype "passive"))
    )
    (net (code "153") (name "Net-(IC12-OA2)") (class "Default")
      (node (ref "IC12") (pin "32") (pinfunction "OA2_32") (pintype "bidirectional"))
      (node (ref "X17") (pin "1") (pinfunction "S_1") (pintype "passive"))
    )
    (net (code "154") (name "Net-(IC12-OB1)") (class "Default")
      (node (ref "IC12") (pin "13") (pinfunction "OB1_13") (pintype "bidirectional"))
      (node (ref "X17") (pin "3") (pinfunction "S_3") (pintype "passive"))
    )
    (net (code "155") (name "Net-(IC12-OB2)") (class "Default")
      (node (ref "IC12") (pin "15") (pinfunction "OB2_15") (pintype "bidirectional"))
      (node (ref "X17") (pin "4") (pinfunction "S_4") (pintype "passive"))
    )
    (net (code "156") (name "Net-(IC12-SCK_CFG2)") (class "Default")
      (node (ref "IC12") (pin "3") (pinfunction "SCK_CFG2_3") (pintype "bidirectional"))
      (node (ref "IC13") (pin "4") (pinfunction "O_4") (pintype "output"))
    )
    (net (code "157") (name "Net-(IC12-SDI_NAI_CFG1)") (class "Default")
      (node (ref "IC12") (pin "4") (pinfunction "SDI_NAI_CFG1_4") (pintype "bidirectional"))
      (node (ref "IC14") (pin "4") (pinfunction "O_4") (pintype "output"))
    )
    (net (code "158") (name "Net-(IC12-SDO_NAO_CFG0)") (class "Default")
      (node (ref "IC12") (pin "5") (pinfunction "SDO_NAO_CFG0_5") (pintype "bidirectional"))
      (node (ref "U4") (pin "3") (pinfunction "QD_3") (pintype "output"))
    )
    (net (code "159") (name "Net-(IC12-VCC)") (class "Default")
      (node (ref "C74") (pin "1") (pinfunction "1_1") (pintype "passive"))
      (node (ref "IC12") (pin "26") (pinfunction "VCC_26") (pintype "bidirectional"))
      (node (ref "R71") (pin "2") (pinfunction "2_2") (pintype "passive"))
    )
    (net (code "160") (name "Net-(IC12-VCP)") (class "Default")
      (node (ref "C66") (pin "1") (pinfunction "1_1") (pintype "passive"))
      (node (ref "IC12") (pin "29") (pinfunction "VCP_29") (pintype "bidirectional"))
    )
    (net (code "161") (name "Net-(IC13A-I)") (class "Default")
      (node (ref "IC13") (pin "2") (pinfunction "I_2") (pintype "input"))
      (node (ref "U4") (pin "4") (pinfunction "QE_4") (pintype "output"))
    )
    (net (code "162") (name "Net-(IC13A-OE)") (class "Default")
      (node (ref "IC13") (pin "1") (pinfunction "OE_1") (pintype "input"))
      (node (ref "U4") (pin "5") (pinfunction "QF_5") (pintype "output"))
    )
    (net (code "163") (name "Net-(IC14A-I)") (class "Default")
      (node (ref "IC14") (pin "2") (pinfunction "I_2") (pintype "input"))
      (node (ref "U4") (pin "6") (pinfunction "QG_6") (pintype "output"))
    )
    (net (code "164") (name "Net-(IC14A-OE)") (class "Default")
      (node (ref "IC14") (pin "1") (pinfunction "OE_1") (pintype "input"))
      (node (ref "U4") (pin "7") (pinfunction "QH_7") (pintype "output"))
    )
    (net (code "165") (name "Net-(IC15-5VOUT)") (class "Default")
      (node (ref "C68") (pin "2") (pinfunction "2_2") (pintype "passive"))
      (node (ref "IC15") (pin "25") (pinfunction "5VOUT_25") (pintype "bidirectional"))
      (node (ref "R52") (pin "1") (pinfunction "1_1") (pintype "passive"))
    )
    (net (code "166") (name "Net-(IC15-AIN_IREF)") (class "Default")
      (node (ref "C36") (pin "1") (pinfunction "1_1") (pintype "passive"))
      (node (ref "IC15") (pin "23") (pinfunction "AIN_IREF_23") (pintype "bidirectional"))
      (node (ref "R50") (pin "1") (pinfunction "1_1") (pintype "passive"))
    )
    (net (code "167") (name "Net-(IC15-BRA)") (class "Default")
      (node (ref "IC15") (pin "33") (pinfunction "BRA_33") (pintype "bidirectional"))
      (node (ref "R10") (pin "2") (pinfunction "2_2") (pintype "passive"))
    )
    (net (code "168") (name "Net-(IC15-BRB)") (class "Default")
      (node (ref "IC15") (pin "14") (pinfunction "BRB_14") (pintype "bidirectional"))
      (node (ref "R9") (pin "2") (pinfunction "2_2") (pintype "passive"))
    )
    (net (code "169") (name "Net-(IC15-CPI)") (class "Default")
      (node (ref "C9") (pin "1") (pinfunction "1_1") (pintype "passive"))
      (node (ref "IC15") (pin "28") (pinfunction "CPI_28") (pintype "bidirectional"))
    )
    (net (code "170") (name "Net-(IC15-CPO)") (class "Default")
      (node (ref "C9") (pin "2") (pinfunction "2_2") (pintype "passive"))
      (node (ref "IC15") (pin "27") (pinfunction "CPO_27") (pintype "bidirectional"))
    )
    (net (code "171") (name "Net-(IC15-ENCA_DCIN_CFG5)") (class "Default")
      (node (ref "IC15") (pin "19") (pinfunction "ENCA_DCIN_CFG5_19") (pintype "bidirectional"))
      (node (ref "U5") (pin "1") (pinfunction "QB_1") (pintype "output"))
    )
    (net (code "172") (name "Net-(IC15-ENCB_DCEN_CFG4)") (class "Default")
      (node (ref "IC15") (pin "18") (pinfunction "ENCB_DCEN_CFG4_18") (pintype "bidirectional"))
      (node (ref "U5") (pin "2") (pinfunction "QC_2") (pintype "output"))
    )
    (net (code "173") (name "Net-(IC15-OA1)") (class "Default")
      (node (ref "IC15") (pin "34") (pinfunction "OA1_34") (pintype "bidirectional"))
      (node (ref "X18") (pin "2") (pinfunction "S_2") (pintype "passive"))
    )
    (net (code "174") (name "Net-(IC15-OA2)") (class "Default")
      (node (ref "IC15") (pin "32") (pinfunction "OA2_32") (pintype "bidirectional"))
      (node (ref "X18") (pin "1") (pinfunction "S_1") (pintype "passive"))
    )
    (net (code "175") (name "Net-(IC15-OB1)") (class "Default")
      (node (ref "IC15") (pin "13") (pinfunction "OB1_13") (pintype "bidirectional"))
      (node (ref "X18") (pin "3") (pinfunction "S_3") (pintype "passive"))
    )
    (net (code "176") (name "Net-(IC15-OB2)") (class "Default")
      (node (ref "IC15") (pin "15") (pinfunction "OB2_15") (pintype "bidirectional"))
      (node (ref "X18") (pin "4") (pinfunction "S_4") (pintype "passive"))
    )
    (net (code "177") (name "Net-(IC15-SCK_CFG2)") (class "Default")
      (node (ref "IC15") (pin "3") (pinfunction "SCK_CFG2_3") (pintype "bidirectional"))
      (node (ref "IC16") (pin "4") (pinfunction "O_4") (pintype "output"))
    )
    (net (code "178") (name "Net-(IC15-SDI_NAI_CFG1)") (class "Default")
      (node (ref "IC15") (pin "4") (pinfunction "SDI_NAI_CFG1_4") (pintype "bidirectional"))
      (node (ref "IC17") (pin "4") (pinfunction "O_4") (pintype "output"))
    )
    (net (code "179") (name "Net-(IC15-SDO_NAO_CFG0)") (class "Default")
      (node (ref "IC15") (pin "5") (pinfunction "SDO_NAO_CFG0_5") (pintype "bidirectional"))
      (node (ref "U5") (pin "3") (pinfunction "QD_3") (pintype "output"))
    )
    (net (code "180") (name "Net-(IC15-VCC)") (class "Default")
      (node (ref "C70") (pin "1") (pinfunction "1_1") (pintype "passive"))
      (node (ref "IC15") (pin "26") (pinfunction "VCC_26") (pintype "bidirectional"))
      (node (ref "R52") (pin "2") (pinfunction "2_2") (pintype "passive"))
    )
    (net (code "181") (name "Net-(IC15-VCP)") (class "Default")
      (node (ref "C69") (pin "1") (pinfunction "1_1") (pintype "passive"))
      (node (ref "IC15") (pin "29") (pinfunction "VCP_29") (pintype "bidirectional"))
    )
    (net (code "182") (name "Net-(IC16A-I)") (class "Default")
      (node (ref "IC16") (pin "2") (pinfunction "I_2") (pintype "input"))
      (node (ref "U5") (pin "4") (pinfunction "QE_4") (pintype "output"))
    )
    (net (code "183") (name "Net-(IC16A-OE)") (class "Default")
      (node (ref "IC16") (pin "1") (pinfunction "OE_1") (pintype "input"))
      (node (ref "U5") (pin "5") (pinfunction "QF_5") (pintype "output"))
    )
    (net (code "184") (name "Net-(IC17A-I)") (class "Default")
      (node (ref "IC17") (pin "2") (pinfunction "I_2") (pintype "input"))
      (node (ref "U5") (pin "6") (pinfunction "QG_6") (pintype "output"))
    )
    (net (code "185") (name "Net-(IC17A-OE)") (class "Default")
      (node (ref "IC17") (pin "1") (pinfunction "OE_1") (pintype "input"))
      (node (ref "U5") (pin "7") (pinfunction "QH_7") (pintype "output"))
    )
    (net (code "186") (name "Net-(LED0-PadA)") (class "Default")
      (node (ref "LED0") (pin "A") (pinfunction "A_A") (pintype "passive"))
      (node (ref "R25") (pin "1") (pinfunction "1_1") (pintype "passive"))
    )
    (net (code "187") (name "Net-(LED1-PadA)") (class "Default")
      (node (ref "LED1") (pin "A") (pinfunction "A_A") (pintype "passive"))
      (node (ref "R14") (pin "1") (pinfunction "1_1") (pintype "passive"))
    )
    (net (code "188") (name "Net-(LED2-PadA)") (class "Default")
      (node (ref "LED2") (pin "A") (pinfunction "A_A") (pintype "passive"))
      (node (ref "R16") (pin "1") (pinfunction "1_1") (pintype "passive"))
    )
    (net (code "189") (name "Net-(LED3-PadA)") (class "Default")
      (node (ref "LED3") (pin "A") (pinfunction "A_A") (pintype "passive"))
      (node (ref "R15") (pin "1") (pinfunction "1_1") (pintype "passive"))
    )
    (net (code "190") (name "Net-(LED4-PadA)") (class "Default")
      (node (ref "LED4") (pin "A") (pinfunction "A_A") (pintype "passive"))
      (node (ref "R11") (pin "1") (pinfunction "1_1") (pintype "passive"))
    )
    (net (code "191") (name "Net-(LED5-PadA)") (class "Default")
      (node (ref "LED5") (pin "A") (pinfunction "A_A") (pintype "passive"))
      (node (ref "R19") (pin "1") (pinfunction "1_1") (pintype "passive"))
    )
    (net (code "192") (name "Net-(LED6-PadA)") (class "Default")
      (node (ref "LED6") (pin "A") (pinfunction "A_A") (pintype "passive"))
      (node (ref "R20") (pin "1") (pinfunction "1_1") (pintype "passive"))
    )
    (net (code "193") (name "Net-(LED7-PadA)") (class "Default")
      (node (ref "LED7") (pin "A") (pinfunction "A_A") (pintype "passive"))
      (node (ref "R21") (pin "1") (pinfunction "1_1") (pintype "passive"))
    )
    (net (code "194") (name "Net-(LED8-PadC)") (class "Default")
      (node (ref "LED8") (pin "C") (pinfunction "C_C") (pintype "passive"))
      (node (ref "R45") (pin "2") (pinfunction "2_2") (pintype "passive"))
    )
    (net (code "195") (name "Net-(Q4-C)") (class "Default")
      (node (ref "LED6") (pin "C") (pinfunction "C_C") (pintype "passive"))
      (node (ref "Q4") (pin "3") (pinfunction "C_3") (pintype "passive"))
      (node (ref "X5") (pin "2") (pinfunction "S_2") (pintype "passive"))
    )
    (net (code "196") (name "Net-(Q5-C)") (class "Default")
      (node (ref "LED7") (pin "C") (pinfunction "C_C") (pintype "passive"))
      (node (ref "Q5") (pin "3") (pinfunction "C_3") (pintype "passive"))
      (node (ref "X6") (pin "2") (pinfunction "S_2") (pintype "passive"))
    )
    (net (code "197") (name "Net-(Q6-C)") (class "Default")
      (node (ref "LED0") (pin "C") (pinfunction "C_C") (pintype "passive"))
      (node (ref "Q6") (pin "3") (pinfunction "C_3") (pintype "passive"))
      (node (ref "X9") (pin "2") (pinfunction "S_2") (pintype "passive"))
    )
    (net (code "198") (name "Net-(Q7-C)") (class "Default")
      (node (ref "LED5") (pin "C") (pinfunction "C_C") (pintype "passive"))
      (node (ref "Q7") (pin "3") (pinfunction "C_3") (pintype "passive"))
      (node (ref "X4") (pin "2") (pinfunction "S_2") (pintype "passive"))
    )
    (net (code "199") (name "Net-(U6-BOOT)") (class "Default")
      (node (ref "C50") (pin "1") (pinfunction "1_1") (pintype "passive"))
      (node (ref "U6") (pin "2") (pinfunction "BOOT_2") (pintype "input"))
    )
    (net (code "200") (name "Net-(U6-COMP)") (class "Default")
      (node (ref "C51") (pin "1") (pinfunction "1_1") (pintype "passive"))
      (node (ref "U6") (pin "8") (pinfunction "COMP_8") (pintype "bidirectional"))
    )
    (net (code "201") (name "Net-(U6-FB)") (class "Default")
      (node (ref "R12") (pin "2") (pinfunction "2_2") (pintype "passive"))
      (node (ref "R22") (pin "1") (pinfunction "1_1") (pintype "passive"))
      (node (ref "U6") (pin "7") (pinfunction "FB_7") (pintype "input"))
    )
    (net (code "202") (name "Net-(U6-SS)") (class "Default")
      (node (ref "C49") (pin "1") (pinfunction "1_1") (pintype "passive"))
      (node (ref "U6") (pin "10") (pinfunction "SS_10") (pintype "bidirectional"))
    )
    (net (code "203") (name "Net-(U6-SW)") (class "Default")
      (node (ref "C50") (pin "2") (pinfunction "2_2") (pintype "passive"))
      (node (ref "D6") (pin "C") (pinfunction "C_C") (pintype "passive"))
      (node (ref "L1") (pin "P$2") (pinfunction "P$2_P$2") (pintype "passive"))
      (node (ref "U6") (pin "5") (pinfunction "SW_5") (pintype "power_in"))
    )
    (net (code "204") (name "Net-(U10-BOOT)") (class "Default")
      (node (ref "C55") (pin "1") (pinfunction "1_1") (pintype "passive"))
      (node (ref "U10") (pin "2") (pinfunction "BOOT_2") (pintype "input"))
    )
    (net (code "205") (name "Net-(U10-COMP)") (class "Default")
      (node (ref "C56") (pin "1") (pinfunction "1_1") (pintype "passive"))
      (node (ref "U10") (pin "8") (pinfunction "COMP_8") (pintype "bidirectional"))
    )
    (net (code "206") (name "Net-(U10-FB)") (class "Default")
      (node (ref "R42") (pin "2") (pinfunction "2_2") (pintype "passive"))
      (node (ref "R43") (pin "1") (pinfunction "1_1") (pintype "passive"))
      (node (ref "U10") (pin "7") (pinfunction "FB_7") (pintype "input"))
    )
    (net (code "207") (name "Net-(U10-SS)") (class "Default")
      (node (ref "C54") (pin "1") (pinfunction "1_1") (pintype "passive"))
      (node (ref "U10") (pin "10") (pinfunction "SS_10") (pintype "bidirectional"))
    )
    (net (code "208") (name "Net-(U10-SW)") (class "Default")
      (node (ref "C55") (pin "2") (pinfunction "2_2") (pintype "passive"))
      (node (ref "D4") (pin "C") (pinfunction "C_C") (pintype "passive"))
      (node (ref "L2") (pin "P$2") (pinfunction "P$2_P$2") (pintype "passive"))
      (node (ref "U10") (pin "5") (pinfunction "SW_5") (pintype "power_in"))
    )
    (net (code "209") (name "Net-(U11-LED0)") (class "Default")
      (node (ref "SV2") (pin "1") (pinfunction "1_1") (pintype "passive"))
      (node (ref "U11") (pin "6") (pinfunction "LED0_6") (pintype "output"))
    )
    (net (code "210") (name "Net-(U11-LED1)") (class "Default")
      (node (ref "SV2") (pin "2") (pinfunction "2_2") (pintype "passive"))
      (node (ref "U11") (pin "7") (pinfunction "LED1_7") (pintype "output"))
    )
    (net (code "211") (name "Net-(U11-LED2)") (class "Default")
      (node (ref "SV2") (pin "3") (pinfunction "3_3") (pintype "passive"))
      (node (ref "U11") (pin "8") (pinfunction "LED2_8") (pintype "output"))
    )
    (net (code "212") (name "Net-(X3B-1)") (class "Default")
      (node (ref "C59") (pin "1") (pinfunction "1_1") (pintype "passive"))
      (node (ref "D1") (pin "A") (pinfunction "A_A") (pintype "passive"))
      (node (ref "LED3") (pin "C") (pinfunction "C_C") (pintype "passive"))
      (node (ref "Q3") (pin "5") (pinfunction "D_5") (pintype "passive"))
      (node (ref "Q3") (pin "6") (pinfunction "D_6") (pintype "passive"))
      (node (ref "Q3") (pin "7") (pinfunction "D_7") (pintype "passive"))
      (node (ref "Q3") (pin "8") (pinfunction "D_8") (pintype "passive"))
      (node (ref "Q3") (pin "TH") (pinfunction "D_TH") (pintype "passive"))
      (node (ref "R55") (pin "1") (pinfunction "1_1") (pintype "passive"))
      (node (ref "X3") (pin "2") (pinfunction "1_2") (pintype "passive"))
    )
    (net (code "213") (name "Net-(X7B-S)") (class "Default")
      (node (ref "R17") (pin "1") (pinfunction "1_1") (pintype "passive"))
      (node (ref "R39") (pin "1") (pinfunction "1_1") (pintype "passive"))
      (node (ref "X7") (pin "2") (pinfunction "S_2") (pintype "passive"))
    )
    (net (code "214") (name "Net-(X8B-S)") (class "Default")
      (node (ref "R13") (pin "1") (pinfunction "1_1") (pintype "passive"))
      (node (ref "R38") (pin "1") (pinfunction "1_1") (pintype "passive"))
      (node (ref "X8") (pin "2") (pinfunction "S_2") (pintype "passive"))
    )
    (net (code "215") (name "Net-(X11B-S)") (class "Default")
      (node (ref "R18") (pin "1") (pinfunction "1_1") (pintype "passive"))
      (node (ref "R40") (pin "1") (pinfunction "1_1") (pintype "passive"))
      (node (ref "X11") (pin "2") (pinfunction "S_2") (pintype "passive"))
    )
    (net (code "216") (name "Net-(X20C-1)") (class "Default")
      (node (ref "C58") (pin "1") (pinfunction "1_1") (pintype "passive"))
      (node (ref "D2") (pin "A") (pinfunction "A_A") (pintype "passive"))
      (node (ref "LED2") (pin "C") (pinfunction "C_C") (pintype "passive"))
      (node (ref "Q1") (pin "5") (pinfunction "D_5") (pintype "passive"))
      (node (ref "Q1") (pin "6") (pinfunction "D_6") (pintype "passive"))
      (node (ref "Q1") (pin "7") (pinfunction "D_7") (pintype "passive"))
      (node (ref "Q1") (pin "8") (pinfunction "D_8") (pintype "passive"))
      (node (ref "Q1") (pin "TH") (pinfunction "D_TH") (pintype "passive"))
      (node (ref "R56") (pin "1") (pinfunction "1_1") (pintype "passive"))
      (node (ref "X20") (pin "3") (pinfunction "1_3") (pintype "passive"))
      (node (ref "X20") (pin "4") (pinfunction "1_4") (pintype "passive"))
    )
    (net (code "217") (name "Net-(X21B-1)") (class "Default")
      (node (ref "C57") (pin "1") (pinfunction "1_1") (pintype "passive"))
      (node (ref "D3") (pin "A") (pinfunction "A_A") (pintype "passive"))
      (node (ref "LED1") (pin "C") (pinfunction "C_C") (pintype "passive"))
      (node (ref "Q2") (pin "5") (pinfunction "D_5") (pintype "passive"))
      (node (ref "Q2") (pin "6") (pinfunction "D_6") (pintype "passive"))
      (node (ref "Q2") (pin "7") (pinfunction "D_7") (pintype "passive"))
      (node (ref "Q2") (pin "8") (pinfunction "D_8") (pintype "passive"))
      (node (ref "Q2") (pin "TH") (pinfunction "D_TH") (pintype "passive"))
      (node (ref "R57") (pin "1") (pinfunction "1_1") (pintype "passive"))
      (node (ref "X21") (pin "2") (pinfunction "1_2") (pintype "passive"))
    )
    (net (code "218") (name "unconnected-(IC1-CSN_CFG3-Pad2)") (class "Default")
      (node (ref "IC1") (pin "2") (pinfunction "CSN_CFG3_2") (pintype "bidirectional"))
    )
    (net (code "219") (name "unconnected-(IC1-ENCN_DCO-Pad17)") (class "Default")
      (node (ref "IC1") (pin "17") (pinfunction "ENCN_DCO_17") (pintype "bidirectional"))
    )
    (net (code "220") (name "unconnected-(IC1-SD_MODE-Pad9)") (class "Default")
      (node (ref "IC1") (pin "9") (pinfunction "SD_MODE_9") (pintype "bidirectional"))
    )
    (net (code "221") (name "unconnected-(IC1-SWP_DIAG1-Pad21)") (class "Default")
      (node (ref "IC1") (pin "21") (pinfunction "SWP_DIAG1_21") (pintype "bidirectional"))
    )
    (net (code "222") (name "unconnected-(IC2-CSN_CFG3-Pad2)") (class "Default")
      (node (ref "IC2") (pin "2") (pinfunction "CSN_CFG3_2") (pintype "bidirectional"))
    )
    (net (code "223") (name "unconnected-(IC2-ENCN_DCO-Pad17)") (class "Default")
      (node (ref "IC2") (pin "17") (pinfunction "ENCN_DCO_17") (pintype "bidirectional"))
    )
    (net (code "224") (name "unconnected-(IC2-SD_MODE-Pad9)") (class "Default")
      (node (ref "IC2") (pin "9") (pinfunction "SD_MODE_9") (pintype "bidirectional"))
    )
    (net (code "225") (name "unconnected-(IC2-SWP_DIAG1-Pad21)") (class "Default")
      (node (ref "IC2") (pin "21") (pinfunction "SWP_DIAG1_21") (pintype "bidirectional"))
    )
    (net (code "226") (name "unconnected-(IC5-CSN_CFG3-Pad2)") (class "Default")
      (node (ref "IC5") (pin "2") (pinfunction "CSN_CFG3_2") (pintype "bidirectional"))
    )
    (net (code "227") (name "unconnected-(IC5-ENCN_DCO-Pad17)") (class "Default")
      (node (ref "IC5") (pin "17") (pinfunction "ENCN_DCO_17") (pintype "bidirectional"))
    )
    (net (code "228") (name "unconnected-(IC5-SD_MODE-Pad9)") (class "Default")
      (node (ref "IC5") (pin "9") (pinfunction "SD_MODE_9") (pintype "bidirectional"))
    )
    (net (code "229") (name "unconnected-(IC5-SWP_DIAG1-Pad21)") (class "Default")
      (node (ref "IC5") (pin "21") (pinfunction "SWP_DIAG1_21") (pintype "bidirectional"))
    )
    (net (code "230") (name "unconnected-(IC12-CSN_CFG3-Pad2)") (class "Default")
      (node (ref "IC12") (pin "2") (pinfunction "CSN_CFG3_2") (pintype "bidirectional"))
    )
    (net (code "231") (name "unconnected-(IC12-ENCN_DCO-Pad17)") (class "Default")
      (node (ref "IC12") (pin "17") (pinfunction "ENCN_DCO_17") (pintype "bidirectional"))
    )
    (net (code "232") (name "unconnected-(IC12-SD_MODE-Pad9)") (class "Default")
      (node (ref "IC12") (pin "9") (pinfunction "SD_MODE_9") (pintype "bidirectional"))
    )
    (net (code "233") (name "unconnected-(IC12-SWP_DIAG1-Pad21)") (class "Default")
      (node (ref "IC12") (pin "21") (pinfunction "SWP_DIAG1_21") (pintype "bidirectional"))
    )
    (net (code "234") (name "unconnected-(IC15-CSN_CFG3-Pad2)") (class "Default")
      (node (ref "IC15") (pin "2") (pinfunction "CSN_CFG3_2") (pintype "bidirectional"))
    )
    (net (code "235") (name "unconnected-(IC15-ENCN_DCO-Pad17)") (class "Default")
      (node (ref "IC15") (pin "17") (pinfunction "ENCN_DCO_17") (pintype "bidirectional"))
    )
    (net (code "236") (name "unconnected-(IC15-SD_MODE-Pad9)") (class "Default")
      (node (ref "IC15") (pin "9") (pinfunction "SD_MODE_9") (pintype "bidirectional"))
    )
    (net (code "237") (name "unconnected-(IC15-SWP_DIAG1-Pad21)") (class "Default")
      (node (ref "IC15") (pin "21") (pinfunction "SWP_DIAG1_21") (pintype "bidirectional"))
    )
    (net (code "238") (name "unconnected-(P8-Pad3)") (class "Default")
      (node (ref "P8") (pin "3") (pinfunction "3_3") (pintype "passive"))
    )
    (net (code "239") (name "unconnected-(P8-Pad4)") (class "Default")
      (node (ref "P8") (pin "4") (pinfunction "4_4") (pintype "passive"))
    )
    (net (code "240") (name "unconnected-(P8-Pad5)") (class "Default")
      (node (ref "P8") (pin "5") (pinfunction "5_5") (pintype "passive"))
    )
    (net (code "241") (name "unconnected-(P8-Pad6)") (class "Default")
      (node (ref "P8") (pin "6") (pinfunction "6_6") (pintype "passive"))
    )
    (net (code "242") (name "unconnected-(P8-Pad7)") (class "Default")
      (node (ref "P8") (pin "7") (pinfunction "7_7") (pintype "passive"))
    )
    (net (code "243") (name "unconnected-(P8-Pad20)") (class "Default")
      (node (ref "P8") (pin "20") (pinfunction "20_20") (pintype "passive"))
    )
    (net (code "244") (name "unconnected-(P8-Pad21)") (class "Default")
      (node (ref "P8") (pin "21") (pinfunction "21_21") (pintype "passive"))
    )
    (net (code "245") (name "unconnected-(P8-Pad22)") (class "Default")
      (node (ref "P8") (pin "22") (pinfunction "22_22") (pintype "passive"))
    )
    (net (code "246") (name "unconnected-(P8-Pad23)") (class "Default")
      (node (ref "P8") (pin "23") (pinfunction "23_23") (pintype "passive"))
    )
    (net (code "247") (name "unconnected-(P8-Pad24)") (class "Default")
      (node (ref "P8") (pin "24") (pinfunction "24_24") (pintype "passive"))
    )
    (net (code "248") (name "unconnected-(P8-Pad25)") (class "Default")
      (node (ref "P8") (pin "25") (pinfunction "25_25") (pintype "passive"))
    )
    (net (code "249") (name "unconnected-(P8-Pad27)") (class "Default")
      (node (ref "P8") (pin "27") (pinfunction "27_27") (pintype "passive"))
    )
    (net (code "250") (name "unconnected-(P8-Pad28)") (class "Default")
      (node (ref "P8") (pin "28") (pinfunction "28_28") (pintype "passive"))
    )
    (net (code "251") (name "unconnected-(P8-Pad29)") (class "Default")
      (node (ref "P8") (pin "29") (pinfunction "29_29") (pintype "passive"))
    )
    (net (code "252") (name "unconnected-(P8-Pad30)") (class "Default")
      (node (ref "P8") (pin "30") (pinfunction "30_30") (pintype "passive"))
    )
    (net (code "253") (name "unconnected-(P8-Pad31)") (class "Default")
      (node (ref "P8") (pin "31") (pinfunction "31_31") (pintype "passive"))
    )
    (net (code "254") (name "unconnected-(P8-Pad32)") (class "Default")
      (node (ref "P8") (pin "32") (pinfunction "32_32") (pintype "passive"))
    )
    (net (code "255") (name "unconnected-(P8-Pad33)") (class "Default")
      (node (ref "P8") (pin "33") (pinfunction "33_33") (pintype "passive"))
    )
    (net (code "256") (name "unconnected-(P8-Pad34)") (class "Default")
      (node (ref "P8") (pin "34") (pinfunction "34_34") (pintype "passive"))
    )
    (net (code "257") (name "unconnected-(P8-Pad35)") (class "Default")
      (node (ref "P8") (pin "35") (pinfunction "35_35") (pintype "passive"))
    )
    (net (code "258") (name "unconnected-(P8-Pad36)") (class "Default")
      (node (ref "P8") (pin "36") (pinfunction "36_36") (pintype "passive"))
    )
    (net (code "259") (name "unconnected-(P8-Pad37)") (class "Default")
      (node (ref "P8") (pin "37") (pinfunction "37_37") (pintype "passive"))
    )
    (net (code "260") (name "unconnected-(P8-Pad38)") (class "Default")
      (node (ref "P8") (pin "38") (pinfunction "38_38") (pintype "passive"))
    )
    (net (code "261") (name "unconnected-(P8-Pad39)") (class "Default")
      (node (ref "P8") (pin "39") (pinfunction "39_39") (pintype "passive"))
    )
    (net (code "262") (name "unconnected-(P8-Pad40)") (class "Default")
      (node (ref "P8") (pin "40") (pinfunction "40_40") (pintype "passive"))
    )
    (net (code "263") (name "unconnected-(P8-Pad41)") (class "Default")
      (node (ref "P8") (pin "41") (pinfunction "41_41") (pintype "passive"))
    )
    (net (code "264") (name "unconnected-(P8-Pad42)") (class "Default")
      (node (ref "P8") (pin "42") (pinfunction "42_42") (pintype "passive"))
    )
    (net (code "265") (name "unconnected-(P8-Pad43)") (class "Default")
      (node (ref "P8") (pin "43") (pinfunction "43_43") (pintype "passive"))
    )
    (net (code "266") (name "unconnected-(P8-Pad44)") (class "Default")
      (node (ref "P8") (pin "44") (pinfunction "44_44") (pintype "passive"))
    )
    (net (code "267") (name "unconnected-(P8-Pad45)") (class "Default")
      (node (ref "P8") (pin "45") (pinfunction "45_45") (pintype "passive"))
    )
    (net (code "268") (name "unconnected-(P8-Pad46)") (class "Default")
      (node (ref "P8") (pin "46") (pinfunction "46_46") (pintype "passive"))
    )
    (net (code "269") (name "unconnected-(P9-Pad9)") (class "Default")
      (node (ref "P9") (pin "9") (pinfunction "9_9") (pintype "passive"))
    )
    (net (code "270") (name "unconnected-(P9-Pad10)") (class "Default")
      (node (ref "P9") (pin "10") (pinfunction "10_10") (pintype "passive"))
    )
    (net (code "271") (name "unconnected-(P9-Pad15)") (class "Default")
      (node (ref "P9") (pin "15") (pinfunction "15_15") (pintype "passive"))
    )
    (net (code "272") (name "unconnected-(P9-Pad17)") (class "Default")
      (node (ref "P9") (pin "17") (pinfunction "17_17") (pintype "passive"))
    )
    (net (code "273") (name "unconnected-(P9-Pad21)") (class "Default")
      (node (ref "P9") (pin "21") (pinfunction "21_21") (pintype "passive"))
    )
    (net (code "274") (name "unconnected-(P9-Pad26)") (class "Default")
      (node (ref "P9") (pin "26") (pinfunction "26_26") (pintype "passive"))
    )
    (net (code "275") (name "unconnected-(P9-Pad27)") (class "Default")
      (node (ref "P9") (pin "27") (pinfunction "27_27") (pintype "passive"))
    )
    (net (code "276") (name "unconnected-(P9-Pad29)") (class "Default")
      (node (ref "P9") (pin "29") (pinfunction "29_29") (pintype "passive"))
    )
    (net (code "277") (name "unconnected-(P9-Pad34)") (class "Default")
      (node (ref "P9") (pin "34") (pinfunction "34_34") (pintype "passive"))
    )
    (net (code "278") (name "unconnected-(P9-Pad37)") (class "Default")
      (node (ref "P9") (pin "37") (pinfunction "37_37") (pintype "passive"))
    )
    (net (code "279") (name "unconnected-(P9-Pad38)") (class "Default")
      (node (ref "P9") (pin "38") (pinfunction "38_38") (pintype "passive"))
    )
    (net (code "280") (name "unconnected-(P9-Pad39)") (class "Default")
      (node (ref "P9") (pin "39") (pinfunction "39_39") (pintype "passive"))
    )
    (net (code "281") (name "unconnected-(P9-Pad40)") (class "Default")
      (node (ref "P9") (pin "40") (pinfunction "40_40") (pintype "passive"))
    )
    (net (code "282") (name "unconnected-(U5-QH_2-Pad9)") (class "Default")
      (node (ref "U5") (pin "9") (pinfunction "QH_2_9") (pintype "output"))
    )
    (net (code "283") (name "unconnected-(U6-EN-Pad9)") (class "Default")
      (node (ref "U6") (pin "9") (pinfunction "EN_9") (pintype "input"))
    )
    (net (code "284") (name "unconnected-(U10-EN-Pad9)") (class "Default")
      (node (ref "U10") (pin "9") (pinfunction "EN_9") (pintype "input"))
    )
    (net (code "285") (name "unconnected-(U11-EXTCLK-Pad25)") (class "Default")
      (node (ref "U11") (pin "25") (pinfunction "EXTCLK_25") (pintype "input"))
    )
    (net (code "286") (name "unconnected-(U11-LED6-Pad12)") (class "Default")
      (node (ref "U11") (pin "12") (pinfunction "LED6_12") (pintype "output"))
    )
    (net (code "287") (name "unconnected-(U18-~{WC}-Pad7)") (class "Default")
      (node (ref "U18") (pin "7") (pinfunction "~{WC}_7") (pintype "no_connect"))
    )
    (net (code "288") (name "unconnected-(U19-NC-Pad16)") (class "Default")
      (node (ref "U19") (pin "16") (pinfunction "NC_16") (pintype "no_connect"))
    )
    (net (code "289") (name "unconnected-(U19-NC_2-Pad13)") (class "Default")
      (node (ref "U19") (pin "13") (pinfunction "NC_2_13") (pintype "no_connect"))
    )
  )
)
